# EEZ_DIB_DCP405_r4B2.net
KiCad netlist of a schematic drawn in EAGLE
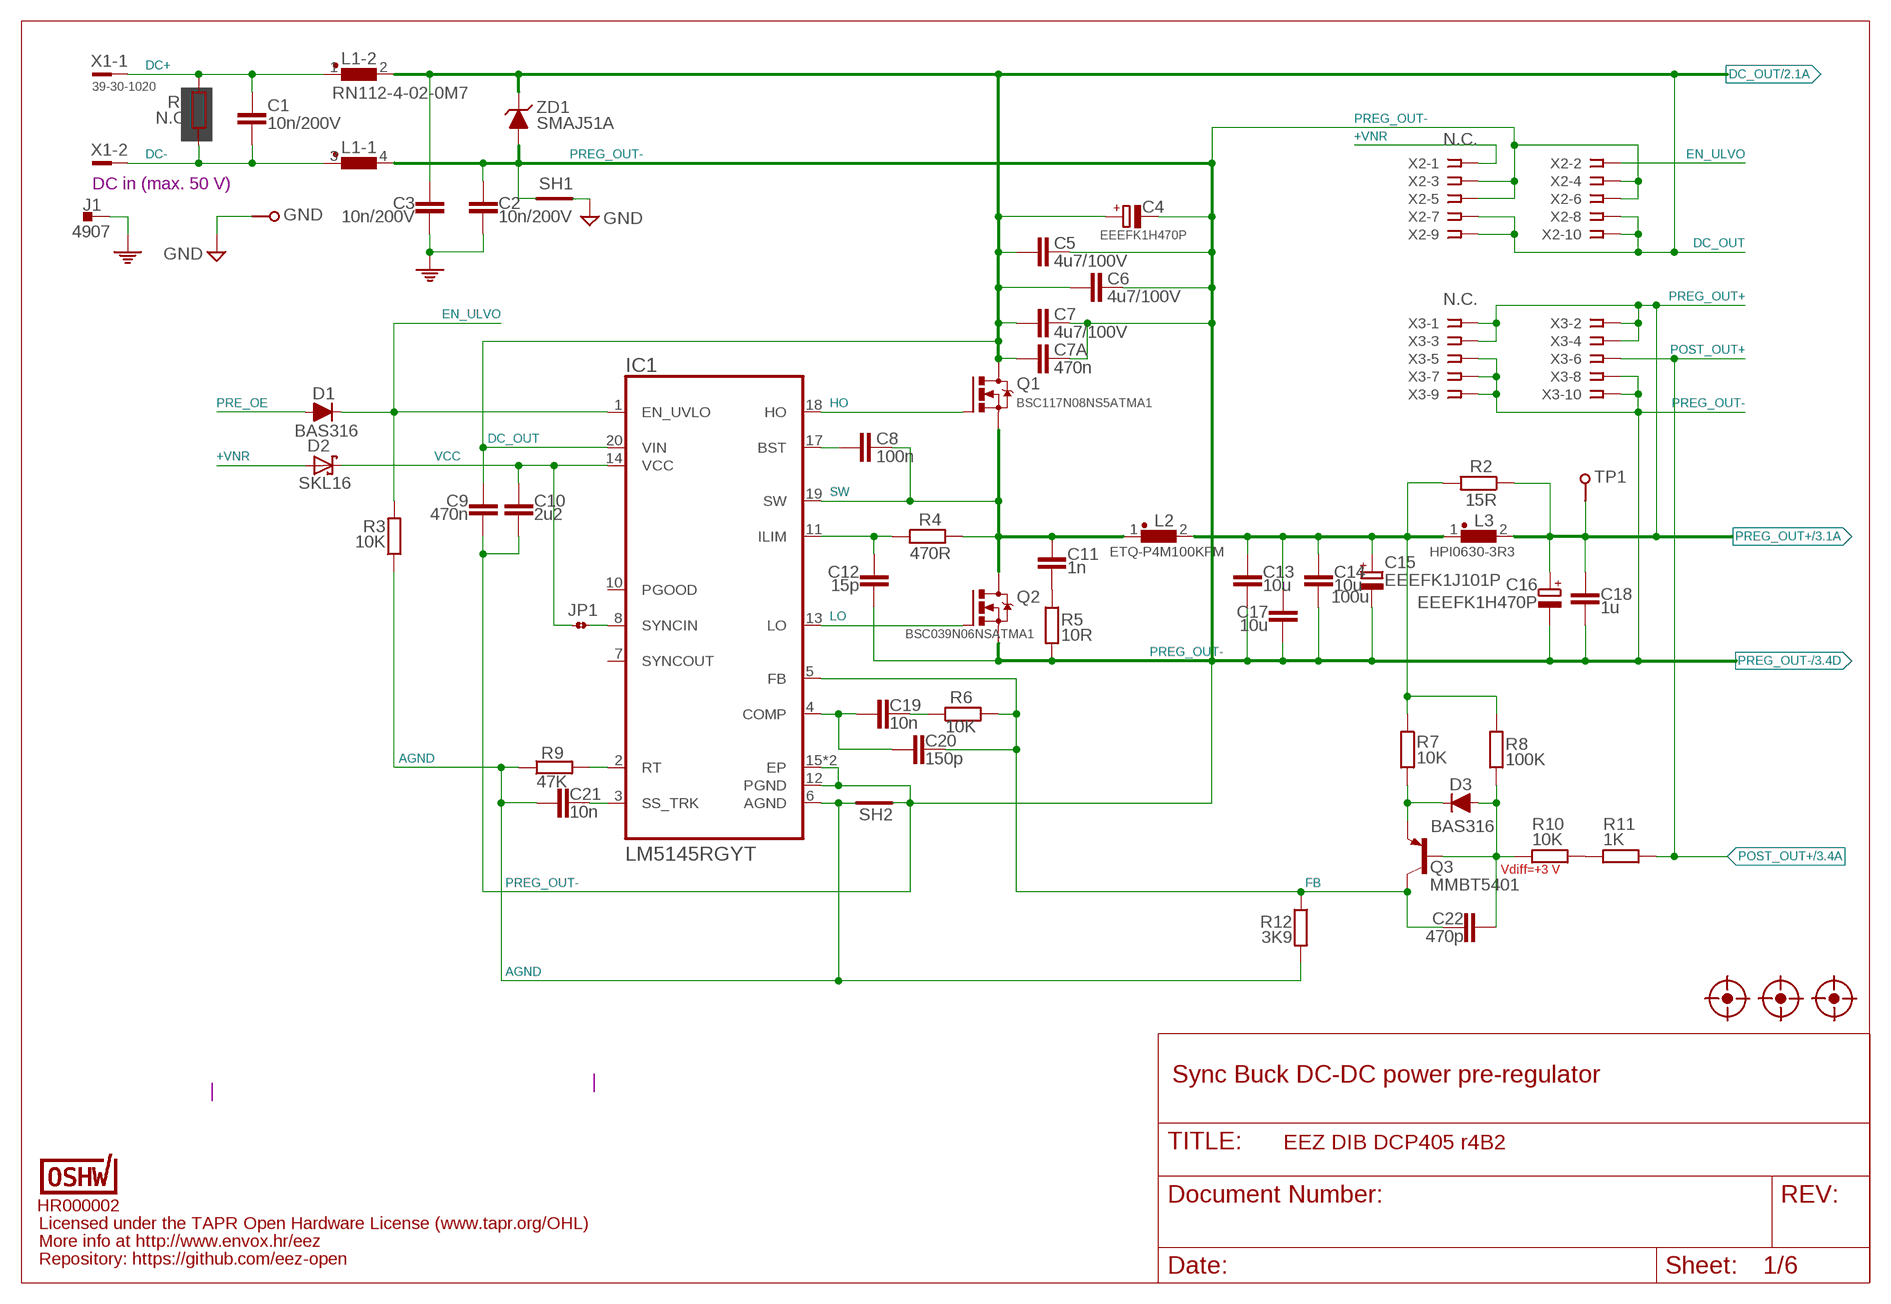
[diagram p0: schematic, sheet 1]
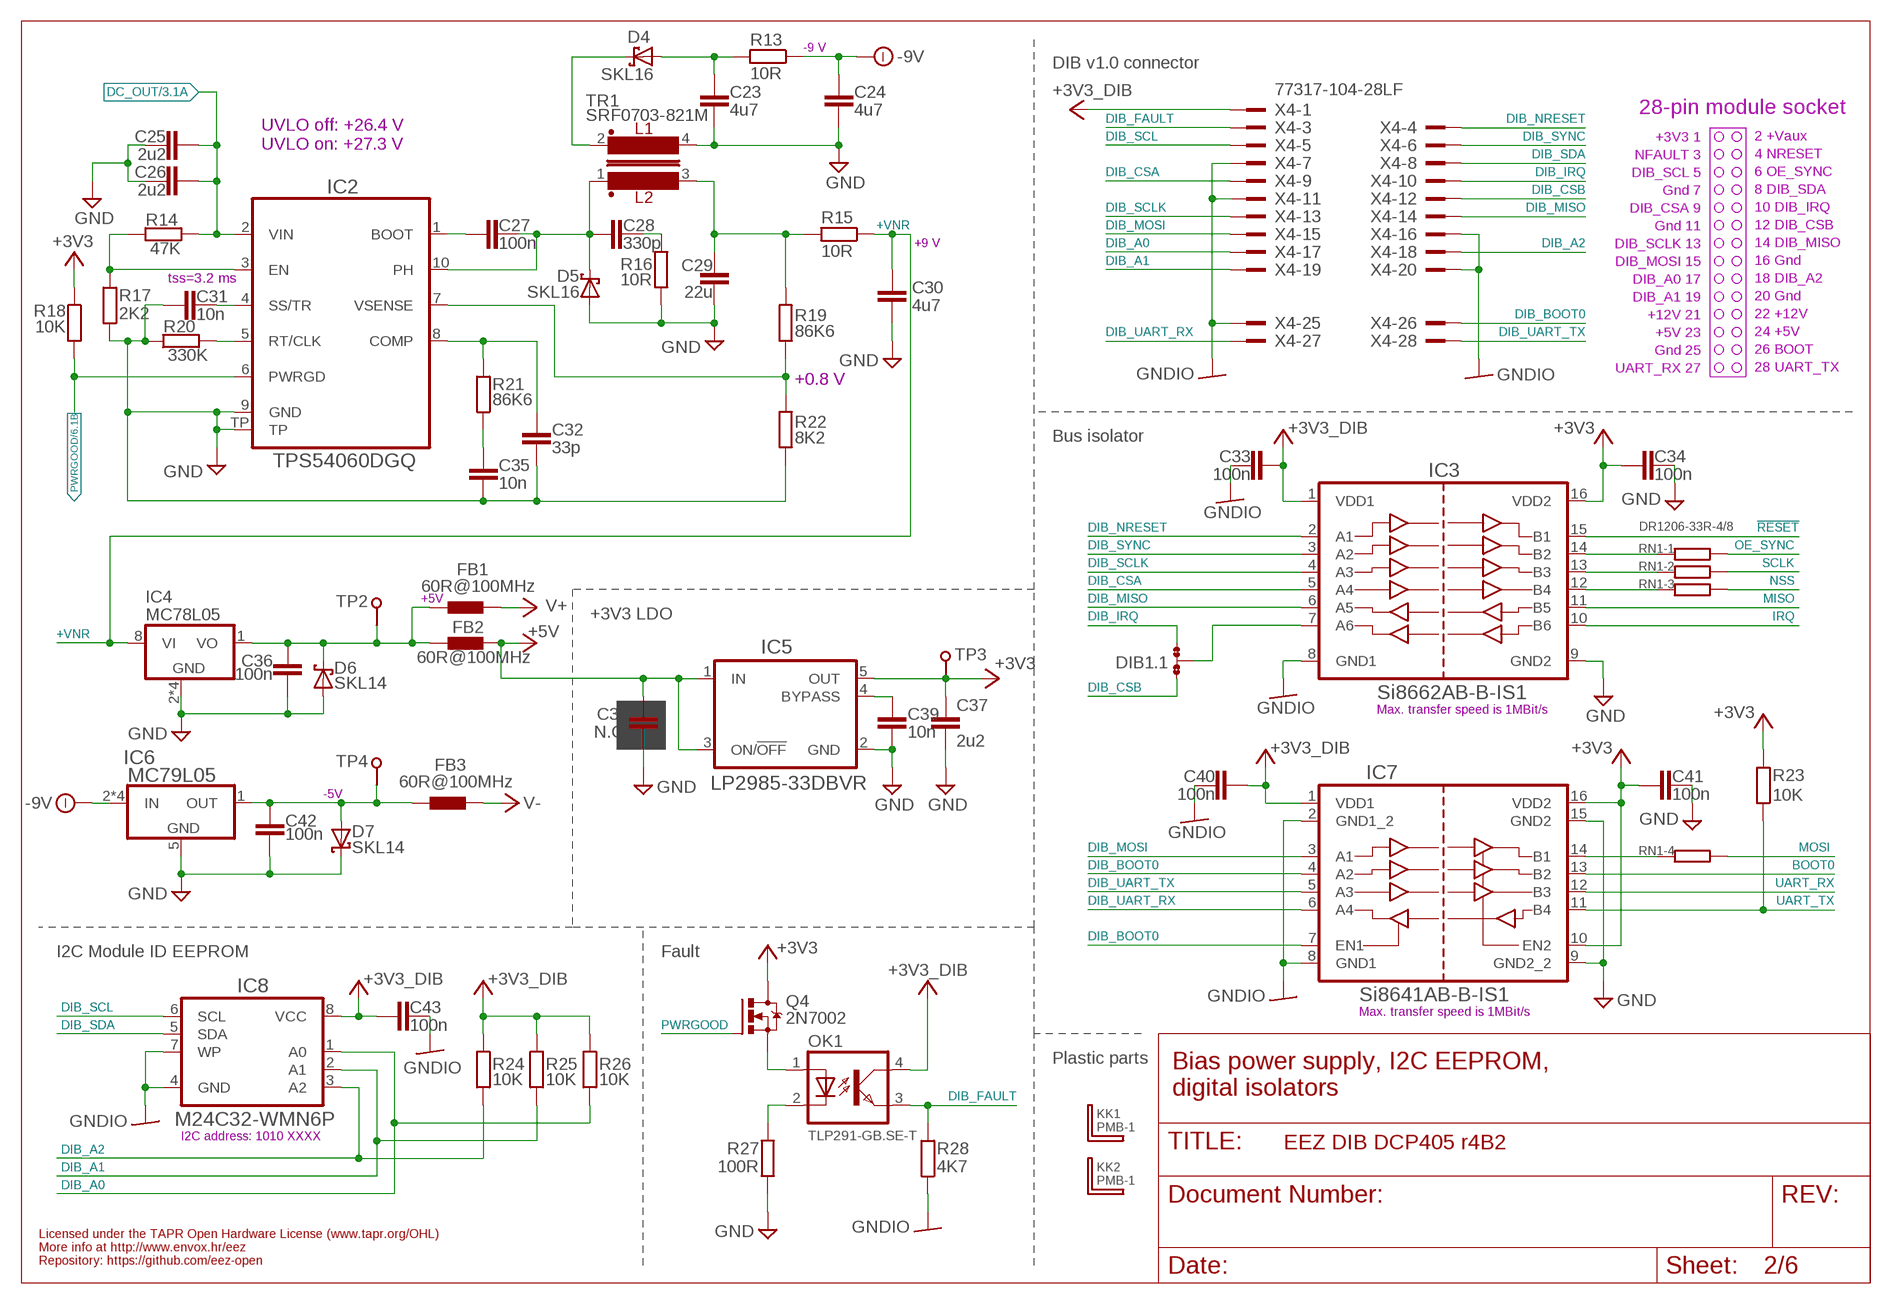
[diagram p1: schematic, sheet 2]
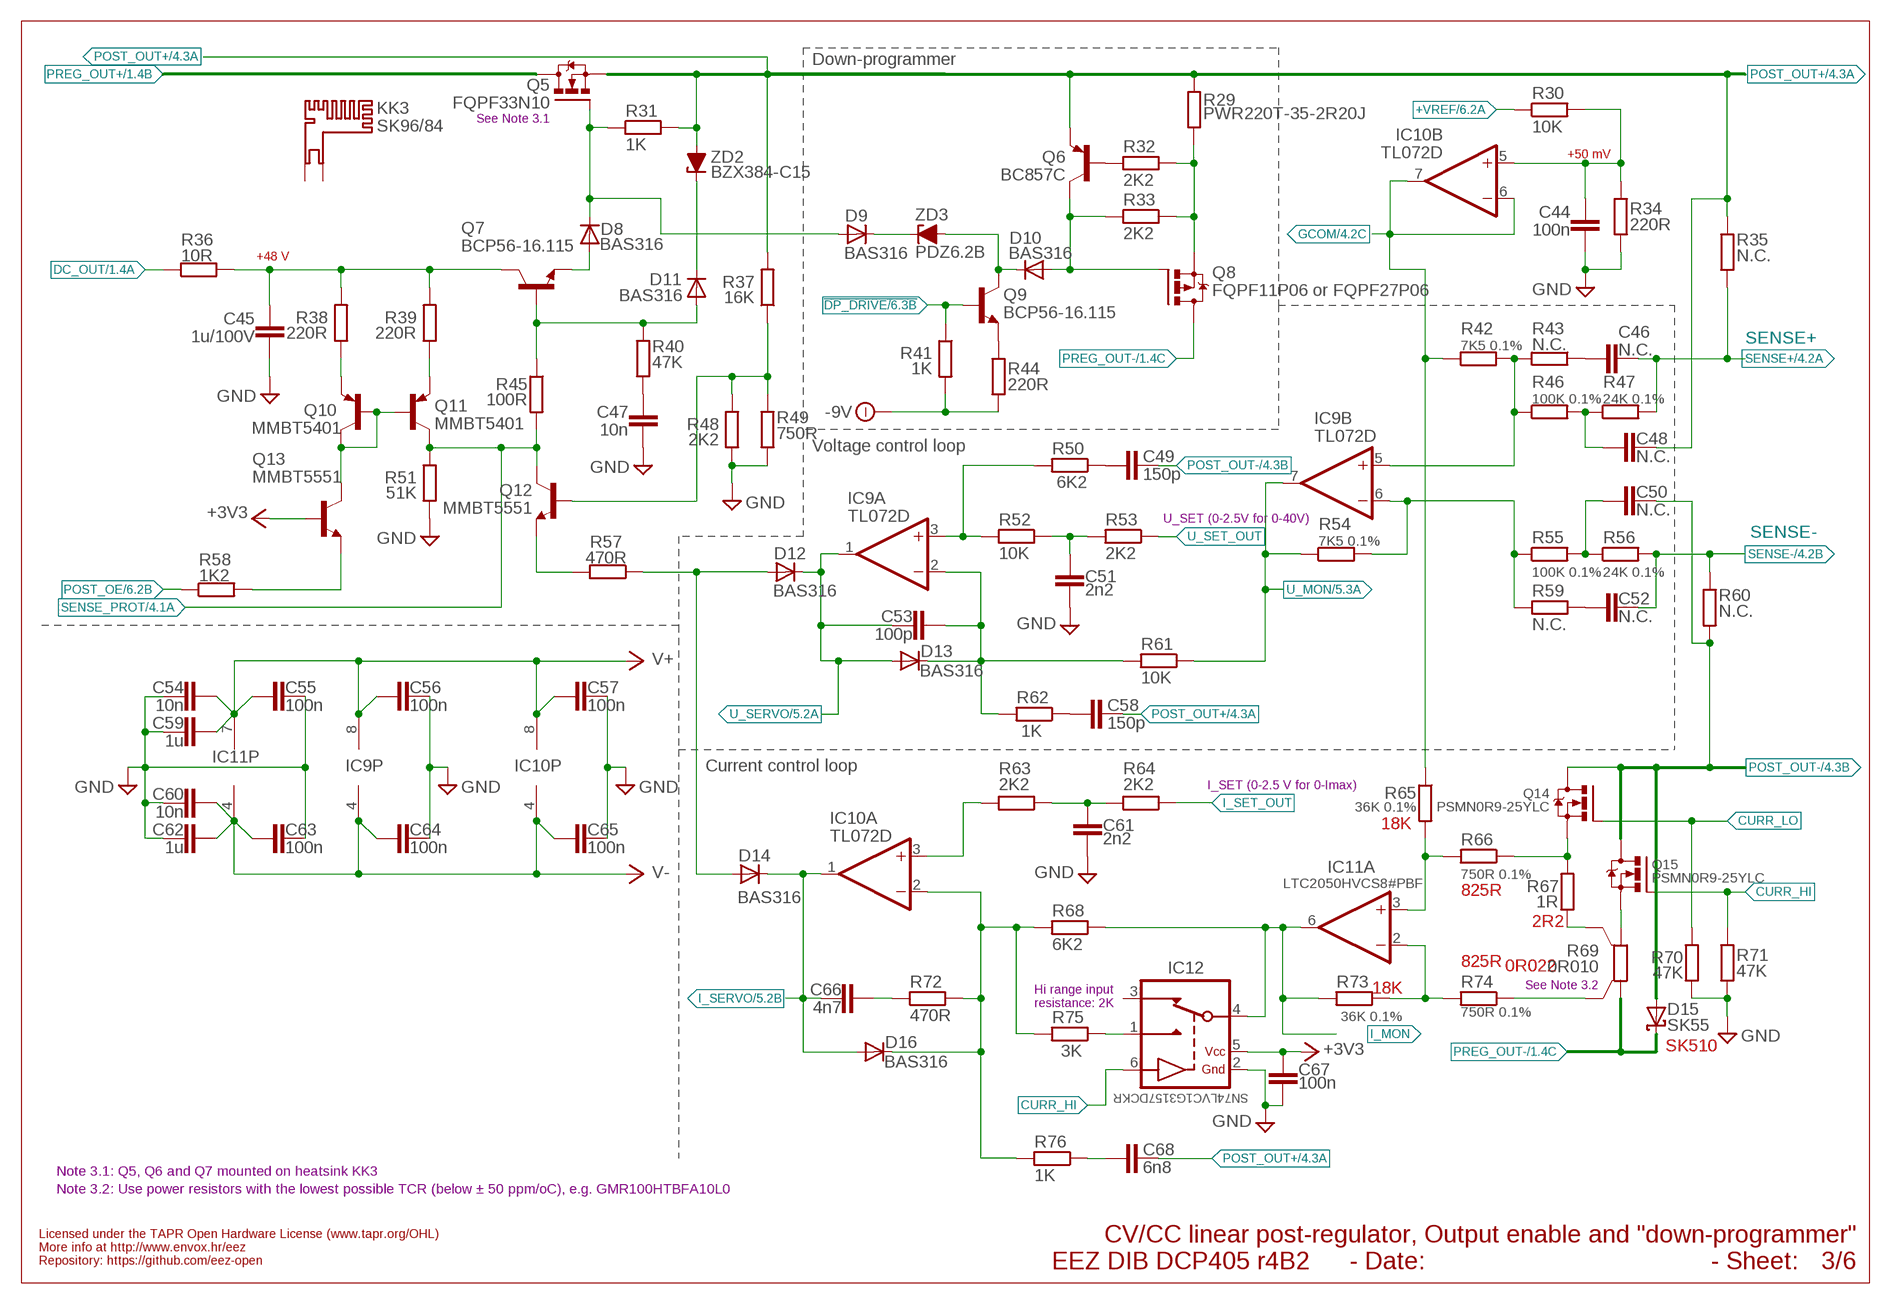
[diagram p2: schematic, sheet 3]
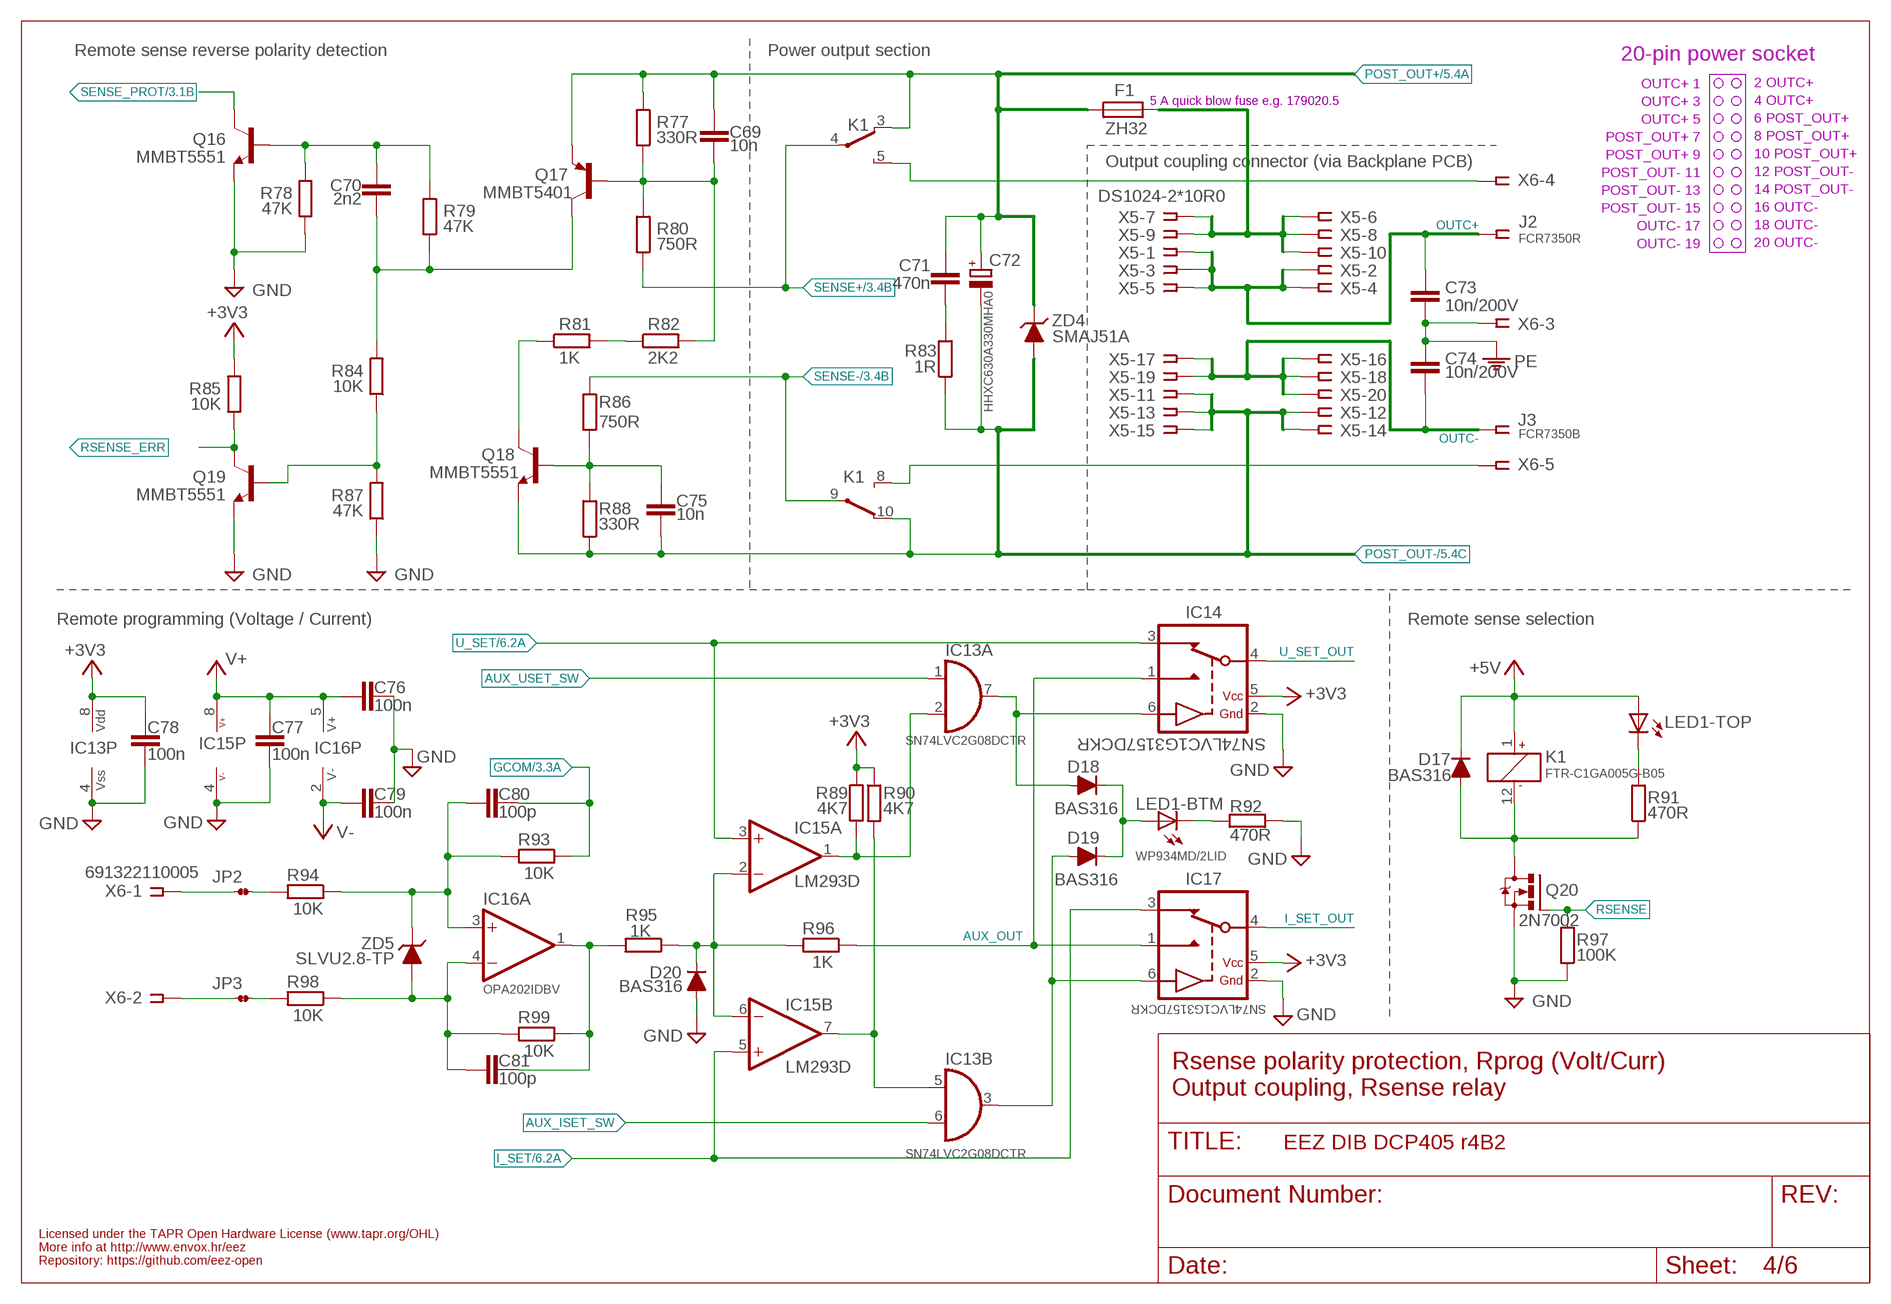
[diagram p3: schematic, sheet 4]
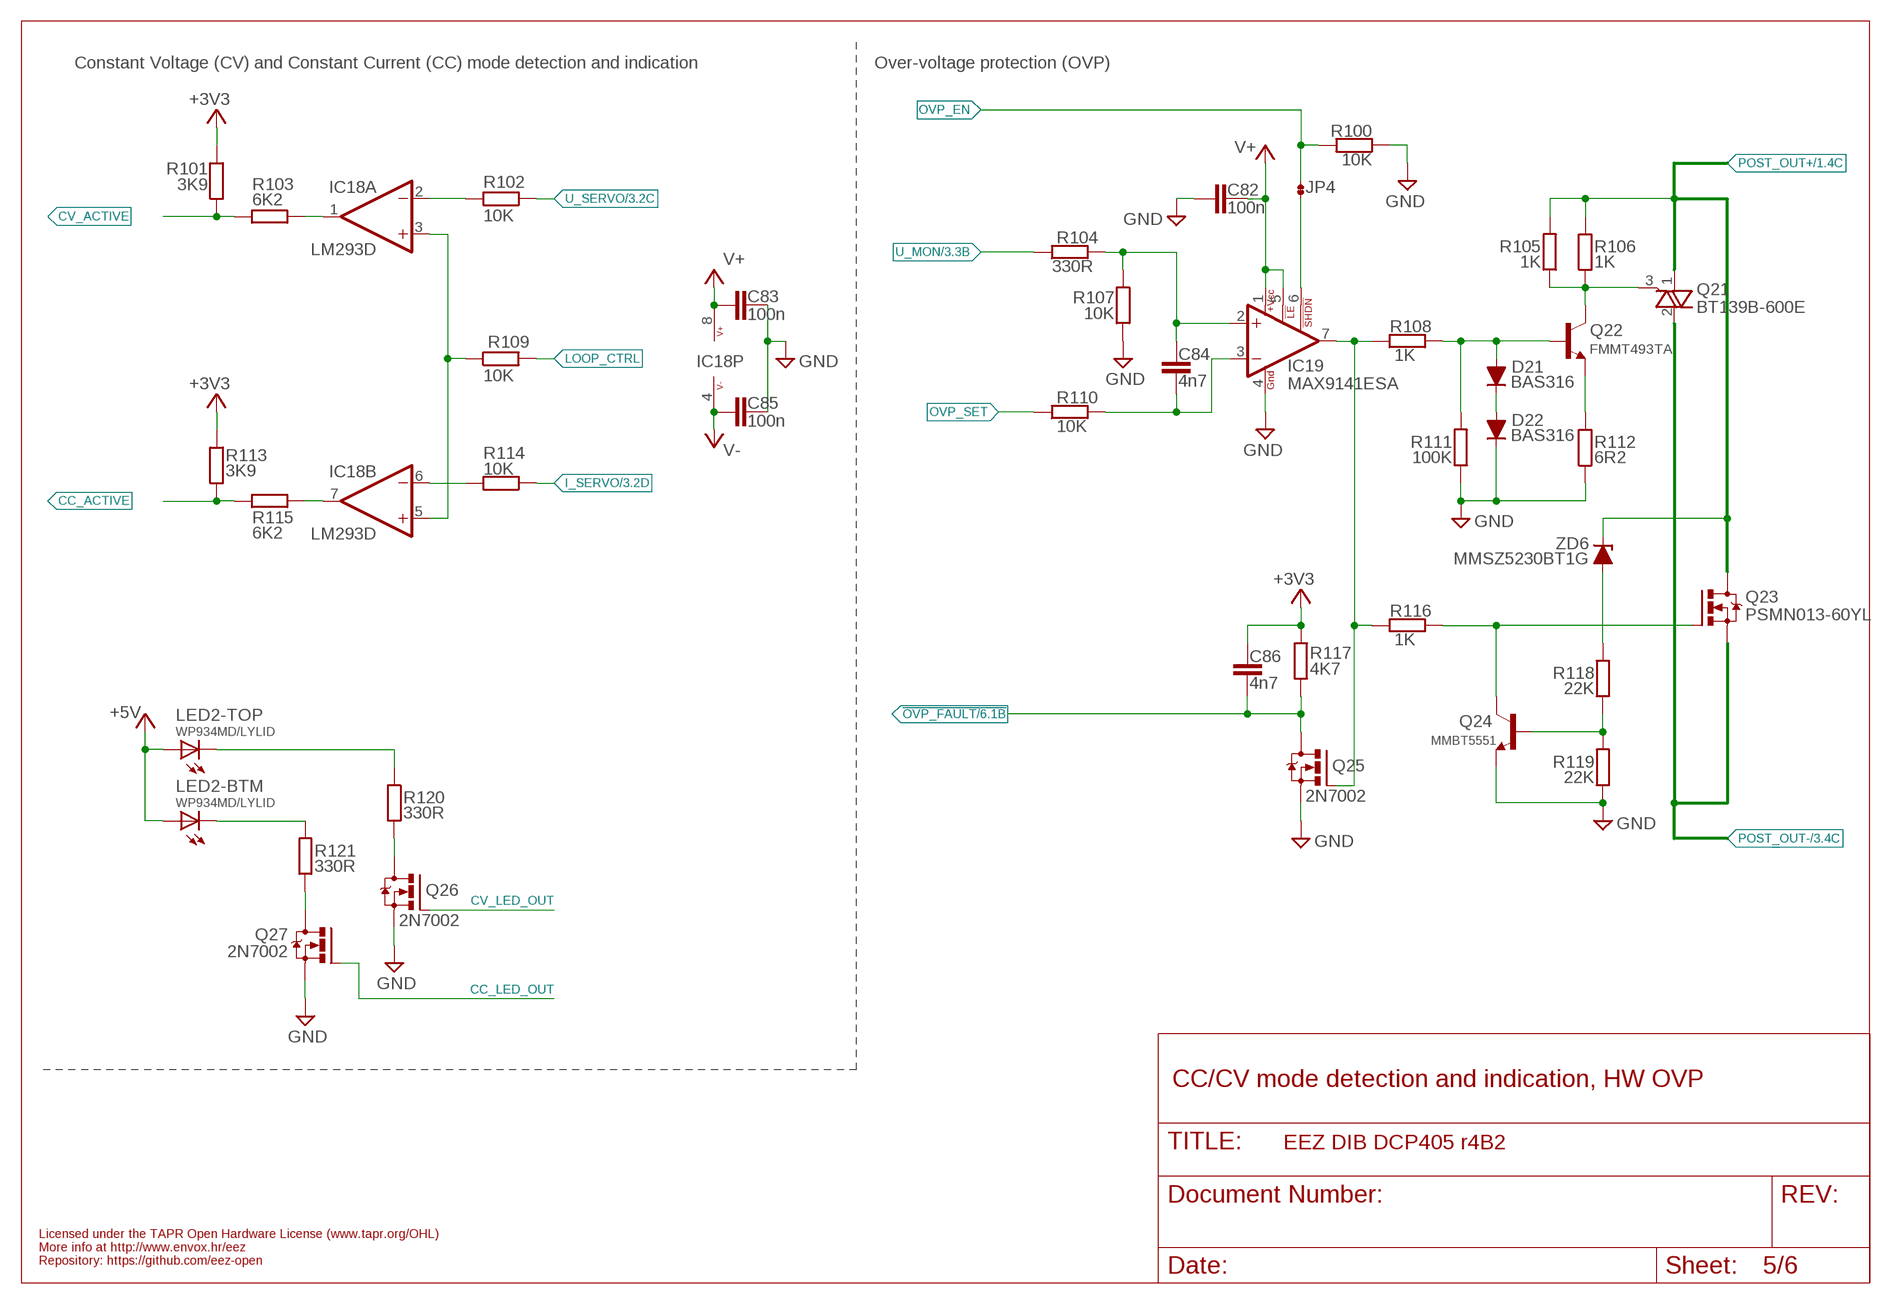
[diagram p4: schematic, sheet 5]
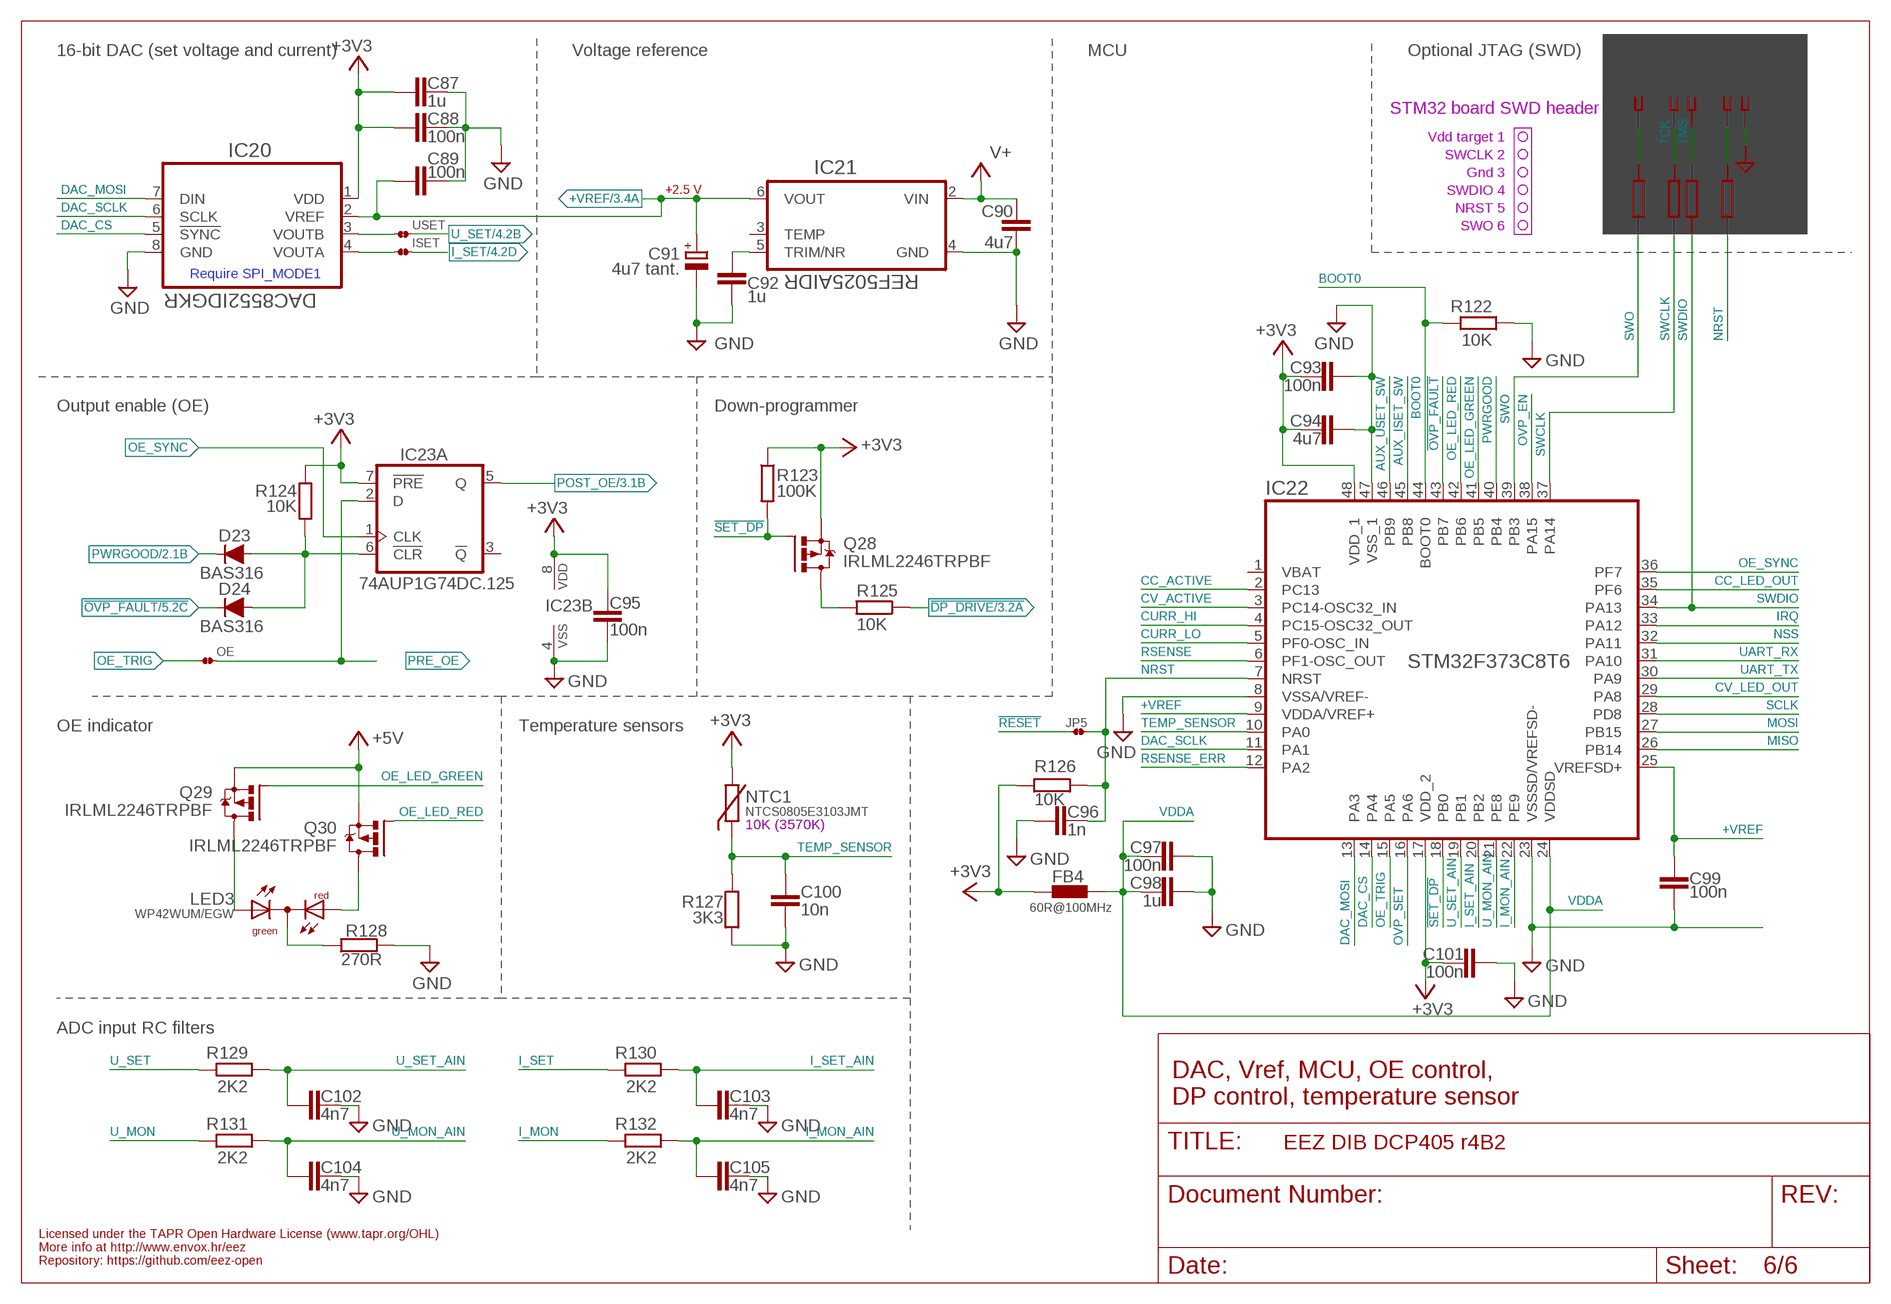
[diagram p5: schematic, sheet 6]

(export (version "E")
  (design (tool "Eeschema 10.0.6"))
  (components
    (comp (ref "C1")
      (value "10n/200V")
      (footprint "eagle-import:C1206")
      (libsource (lib "eagle-import") (part "C-EUC1206"))
    )
    (comp (ref "C2")
      (value "10n/200V")
      (footprint "eagle-import:C1206")
      (libsource (lib "eagle-import") (part "C-EUC1206"))
    )
    (comp (ref "C3")
      (value "10n/200V")
      (footprint "eagle-import:C1206")
      (libsource (lib "eagle-import") (part "C-EUC1206"))
    )
    (comp (ref "C4")
      (value "EEEFK1H470P")
      (footprint "eagle-import:CAPAE830X1050N")
      (libsource (lib "eagle-import") (part "ECAPSMD8.3MM/HA0"))
    )
    (comp (ref "C5")
      (value "4u7/100V")
      (footprint "eagle-import:C1210")
      (libsource (lib "eagle-import") (part "C-EUC1210"))
    )
    (comp (ref "C6")
      (value "4u7/100V")
      (footprint "eagle-import:C1210")
      (libsource (lib "eagle-import") (part "C-EUC1210"))
    )
    (comp (ref "C7")
      (value "4u7/100V")
      (footprint "eagle-import:C1210")
      (libsource (lib "eagle-import") (part "C-EUC1210"))
    )
    (comp (ref "C7A")
      (value "470n")
      (footprint "eagle-import:C0805")
      (libsource (lib "eagle-import") (part "C-EUC0805"))
    )
    (comp (ref "C8")
      (value "100n")
      (footprint "eagle-import:C0603")
      (libsource (lib "eagle-import") (part "C-EUC0603"))
    )
    (comp (ref "C9")
      (value "470n")
      (footprint "eagle-import:C0805")
      (libsource (lib "eagle-import") (part "C-EUC0805"))
    )
    (comp (ref "C10")
      (value "2u2")
      (footprint "eagle-import:C1206")
      (libsource (lib "eagle-import") (part "C-EUC1206"))
    )
    (comp (ref "C11")
      (value "1n")
      (footprint "eagle-import:C0805")
      (libsource (lib "eagle-import") (part "C-EUC0805"))
    )
    (comp (ref "C12")
      (value "15p")
      (footprint "eagle-import:C0805")
      (libsource (lib "eagle-import") (part "C-EUC0805"))
    )
    (comp (ref "C13")
      (value "10u")
      (footprint "eagle-import:C1210")
      (libsource (lib "eagle-import") (part "C-EUC1210"))
    )
    (comp (ref "C14")
      (value "10u")
      (footprint "eagle-import:C1210")
      (libsource (lib "eagle-import") (part "C-EUC1210"))
    )
    (comp (ref "C15")
      (value "EEEFK1J101P")
      (footprint "eagle-import:CAPAE1030X1050N")
      (libsource (lib "eagle-import") (part "ECAP10X10"))
    )
    (comp (ref "C16")
      (value "EEEFK1H470P")
      (footprint "eagle-import:CAPAE830X1050N")
      (libsource (lib "eagle-import") (part "ECAPSMD8.3MM/HA0"))
    )
    (comp (ref "C17")
      (value "10u")
      (footprint "eagle-import:C1210")
      (libsource (lib "eagle-import") (part "C-EUC1210"))
    )
    (comp (ref "C18")
      (value "1u")
      (footprint "eagle-import:C0805")
      (libsource (lib "eagle-import") (part "C-EUC0805"))
    )
    (comp (ref "C19")
      (value "10n")
      (footprint "eagle-import:C0805")
      (libsource (lib "eagle-import") (part "C-EUC0805"))
    )
    (comp (ref "C20")
      (value "150p")
      (footprint "eagle-import:C0805")
      (libsource (lib "eagle-import") (part "C-EUC0805"))
    )
    (comp (ref "C21")
      (value "10n")
      (footprint "eagle-import:C0805")
      (libsource (lib "eagle-import") (part "C-EUC0805"))
    )
    (comp (ref "C22")
      (value "470p")
      (footprint "eagle-import:C0805")
      (libsource (lib "eagle-import") (part "C-EUC0805"))
    )
    (comp (ref "D1")
      (value "BAS316")
      (footprint "eagle-import:SOD323-R")
      (libsource (lib "eagle-import") (part "DIODESOD323R"))
    )
    (comp (ref "D2")
      (value "SKL16")
      (footprint "eagle-import:SOD123")
      (libsource (lib "eagle-import") (part "SCHOTTKYSOD123"))
    )
    (comp (ref "D3")
      (value "BAS316")
      (footprint "eagle-import:SOD323-R")
      (libsource (lib "eagle-import") (part "DIODESOD323R"))
    )
    (comp (ref "FM1")
      (value "FIDUCIAL_2")
      (footprint "eagle-import:FIDUCIAL_DUAL")
      (libsource (lib "eagle-import") (part "FIDUCIAL_2"))
    )
    (comp (ref "FM2")
      (value "FIDUCIAL_2")
      (footprint "eagle-import:FIDUCIAL_DUAL")
      (libsource (lib "eagle-import") (part "FIDUCIAL_2"))
    )
    (comp (ref "FM3")
      (value "FIDUCIAL_2")
      (footprint "eagle-import:FIDUCIAL_DUAL")
      (libsource (lib "eagle-import") (part "FIDUCIAL_2"))
    )
    (comp (ref "GND")
      (value "PCB_TEST_TABSHIELD")
      (footprint "eagle-import:PCB_SHIELD_TAB")
      (libsource (lib "eagle-import") (part "PCB_TEST_TABSHIELD"))
    )
    (comp (ref "IC1")
      (value "LM5145RGYT")
      (footprint "eagle-import:RGY0020B")
      (libsource (lib "eagle-import") (part "LM5145RGYR"))
    )
    (comp (ref "J1")
      (value "4907")
      (footprint "eagle-import:PCB_TAB-4907")
      (libsource (lib "eagle-import") (part "PCB_TAB-4907"))
    )
    (comp (ref "JP1")
      (value "JP2-CUT-0805")
      (footprint "eagle-import:R_0805")
      (libsource (lib "eagle-import") (part "JP2-CUT-0805"))
    )
    (comp (ref "L1")
      (value "RN112-4-02-0M7")
      (footprint "eagle-import:RN112")
      (libsource (lib "eagle-import") (part "RN112"))
    )
    (comp (ref "L2")
      (value "ETQ-P4M100KFM")
      (footprint "eagle-import:PANASONIC_ETQ-P4_KFM")
      (libsource (lib "eagle-import") (part "PANASONIC_ETQ-P4_KFM"))
    )
    (comp (ref "L3")
      (value "HPI0630-3R3")
      (footprint "eagle-import:COILCRAFT_HPI0630")
      (libsource (lib "eagle-import") (part "COILCRAFT_HPI0630"))
    )
    (comp (ref "OSHWA")
      (value "HR000002")
      (footprint "eagle-import:CERT-SMALL-SILK")
      (libsource (lib "eagle-import") (part "OSHWA-CERT-SMALL"))
    )
    (comp (ref "Q1")
      (value "BSC117N08NS5ATMA1")
      (footprint "eagle-import:TDSON-8")
      (libsource (lib "eagle-import") (part "N-MOSFETTDSON-8"))
    )
    (comp (ref "Q2")
      (value "BSC039N06NSATMA1")
      (footprint "eagle-import:TDSON-8")
      (libsource (lib "eagle-import") (part "N-MOSFETTDSON-8"))
    )
    (comp (ref "Q3")
      (value "MMBT5401")
      (footprint "eagle-import:SOT23-BEC")
      (libsource (lib "eagle-import") (part "-PNP-SOT23-BECBC857B"))
    )
    (comp (ref "R1")
      (value "N.C.")
      (footprint "eagle-import:R2512")
      (libsource (lib "eagle-import") (part "R-EU_R2512"))
    )
    (comp (ref "R2")
      (value "15R")
      (footprint "eagle-import:R2010")
      (libsource (lib "eagle-import") (part "R-EU_R2010"))
    )
    (comp (ref "R3")
      (value "10K")
      (footprint "eagle-import:R0805")
      (libsource (lib "eagle-import") (part "R-EU_R0805"))
    )
    (comp (ref "R4")
      (value "470R")
      (footprint "eagle-import:R0805")
      (libsource (lib "eagle-import") (part "R-EU_R0805"))
    )
    (comp (ref "R5")
      (value "10R")
      (footprint "eagle-import:R1206")
      (libsource (lib "eagle-import") (part "R-EU_R1206"))
    )
    (comp (ref "R6")
      (value "10K")
      (footprint "eagle-import:R0805")
      (libsource (lib "eagle-import") (part "R-EU_R0805"))
    )
    (comp (ref "R7")
      (value "10K")
      (footprint "eagle-import:R0805")
      (libsource (lib "eagle-import") (part "R-EU_R0805"))
    )
    (comp (ref "R8")
      (value "100K")
      (footprint "eagle-import:R0805")
      (libsource (lib "eagle-import") (part "R-EU_R0805"))
    )
    (comp (ref "R9")
      (value "47K")
      (footprint "eagle-import:R0805")
      (libsource (lib "eagle-import") (part "R-EU_R0805"))
    )
    (comp (ref "R10")
      (value "10K")
      (footprint "eagle-import:R0805")
      (libsource (lib "eagle-import") (part "R-EU_R0805"))
    )
    (comp (ref "R11")
      (value "1K")
      (footprint "eagle-import:R0805")
      (libsource (lib "eagle-import") (part "R-EU_R0805"))
    )
    (comp (ref "R12")
      (value "3K9")
      (footprint "eagle-import:R0805")
      (libsource (lib "eagle-import") (part "R-EU_R0805"))
    )
    (comp (ref "SH1")
      (value "SHORTNOHOLE")
      (footprint "eagle-import:SHORT_NOHOLE")
      (libsource (lib "eagle-import") (part "SHORTNOHOLE"))
    )
    (comp (ref "SH2")
      (value "SHORTNOHOLE")
      (footprint "eagle-import:SHORT_NOHOLE")
      (libsource (lib "eagle-import") (part "SHORTNOHOLE"))
    )
    (comp (ref "TP1")
      (value "TEST-PIN_0.9MM")
      (footprint "eagle-import:TEST-PIN_0.9MM")
      (libsource (lib "eagle-import") (part "TEST-PIN_0.9MM"))
    )
    (comp (ref "X1")
      (value "39-30-1020")
      (footprint "eagle-import:MINIFIT_39301020")
      (libsource (lib "eagle-import") (part "MINIFIT_39301020"))
    )
    (comp (ref "X2")
      (value "N.C.")
      (footprint "eagle-import:SSW-105-02-S-D")
      (fields (field (name "MPN") "SSW-105-02-S-D"))
      (libsource (lib "eagle-import") (part "SSW-105-02-S-D"))
    )
    (comp (ref "X3")
      (value "N.C.")
      (footprint "eagle-import:SSW-105-02-S-D")
      (fields (field (name "MPN") "SSW-105-02-S-D"))
      (libsource (lib "eagle-import") (part "SSW-105-02-S-D"))
    )
    (comp (ref "ZD1")
      (value "SMAJ51A")
      (footprint "eagle-import:DO214AA")
      (libsource (lib "eagle-import") (part "P6SMB68A"))
    )
    (comp (ref "C82")
      (value "100n")
      (footprint "eagle-import:C0603")
      (libsource (lib "eagle-import") (part "C-EUC0603"))
    )
    (comp (ref "C83")
      (value "100n")
      (footprint "eagle-import:C0603")
      (libsource (lib "eagle-import") (part "C-EUC0603"))
    )
    (comp (ref "C84")
      (value "4n7")
      (footprint "eagle-import:C0805")
      (libsource (lib "eagle-import") (part "C-EUC0805"))
    )
    (comp (ref "C85")
      (value "100n")
      (footprint "eagle-import:C0603")
      (libsource (lib "eagle-import") (part "C-EUC0603"))
    )
    (comp (ref "C86")
      (value "4n7")
      (footprint "eagle-import:C0805")
      (libsource (lib "eagle-import") (part "C-EUC0805"))
    )
    (comp (ref "D21")
      (value "BAS316")
      (footprint "eagle-import:SOD323-R")
      (libsource (lib "eagle-import") (part "DIODESOD323R"))
    )
    (comp (ref "D22")
      (value "BAS316")
      (footprint "eagle-import:SOD323-R")
      (libsource (lib "eagle-import") (part "DIODESOD323R"))
    )
    (comp (ref "IC18")
      (value "LM293D")
      (footprint "eagle-import:SOIC127P600X173-8N")
      (libsource (lib "eagle-import") (part "LM293D"))
    )
    (comp (ref "IC19")
      (value "MAX9141ESA")
      (footprint "eagle-import:SOIC127P600X173-8N")
      (libsource (lib "eagle-import") (part "MAX9141ESA"))
    )
    (comp (ref "JP4")
      (value "JP2-NOCUT-0805")
      (footprint "eagle-import:JP2-0805-NOCUT")
      (libsource (lib "eagle-import") (part "JP2-NOCUT-0805"))
    )
    (comp (ref "LED2")
      (value "WP934MD/LYLID")
      (footprint "eagle-import:WP934MD")
      (libsource (lib "eagle-import") (part "WP934MD/LYLID"))
    )
    (comp (ref "Q21")
      (value "BT139B-600E")
      (footprint "eagle-import:D2PAK")
      (libsource (lib "eagle-import") (part "BT139"))
    )
    (comp (ref "Q22")
      (value "FMMT493TA")
      (footprint "eagle-import:SOT23-BEC")
      (libsource (lib "eagle-import") (part "-NPN-SOT23-BECMMBT5551LT1"))
    )
    (comp (ref "Q23")
      (value "PSMN013-60YL")
      (footprint "eagle-import:SOT669")
      (libsource (lib "eagle-import") (part "N-MOSFETLFPAK"))
    )
    (comp (ref "Q24")
      (value "MMBT5551")
      (footprint "eagle-import:SOT23-BEC")
      (libsource (lib "eagle-import") (part "-NPN-SOT23-BECMMBT5551LT1"))
    )
    (comp (ref "Q25")
      (value "2N7002")
      (footprint "eagle-import:SOT103P240X110-3N")
      (fields (field (name "MPN") "2N7002-7-F"))
      (libsource (lib "eagle-import") (part "2N7002"))
    )
    (comp (ref "Q26")
      (value "2N7002")
      (footprint "eagle-import:SOT103P240X110-3N")
      (fields (field (name "MPN") "2N7002-7-F"))
      (libsource (lib "eagle-import") (part "2N7002"))
    )
    (comp (ref "Q27")
      (value "2N7002")
      (footprint "eagle-import:SOT103P240X110-3N")
      (fields (field (name "MPN") "2N7002-7-F"))
      (libsource (lib "eagle-import") (part "2N7002"))
    )
    (comp (ref "R100")
      (value "10K")
      (footprint "eagle-import:R0805")
      (libsource (lib "eagle-import") (part "R-EU_R0805"))
    )
    (comp (ref "R101")
      (value "3K9")
      (footprint "eagle-import:R0805")
      (libsource (lib "eagle-import") (part "R-EU_R0805"))
    )
    (comp (ref "R102")
      (value "10K")
      (footprint "eagle-import:R0805")
      (libsource (lib "eagle-import") (part "R-EU_R0805"))
    )
    (comp (ref "R103")
      (value "6K2")
      (footprint "eagle-import:R0805")
      (libsource (lib "eagle-import") (part "R-EU_R0805"))
    )
    (comp (ref "R104")
      (value "330R")
      (footprint "eagle-import:R0805")
      (libsource (lib "eagle-import") (part "R-EU_R0805"))
    )
    (comp (ref "R105")
      (value "1K")
      (footprint "eagle-import:R0805")
      (libsource (lib "eagle-import") (part "R-EU_R0805"))
    )
    (comp (ref "R106")
      (value "1K")
      (footprint "eagle-import:R0805")
      (libsource (lib "eagle-import") (part "R-EU_R0805"))
    )
    (comp (ref "R107")
      (value "10K")
      (footprint "eagle-import:R0805")
      (libsource (lib "eagle-import") (part "R-EU_R0805"))
    )
    (comp (ref "R108")
      (value "1K")
      (footprint "eagle-import:R0805")
      (libsource (lib "eagle-import") (part "R-EU_R0805"))
    )
    (comp (ref "R109")
      (value "10K")
      (footprint "eagle-import:R0805")
      (libsource (lib "eagle-import") (part "R-EU_R0805"))
    )
    (comp (ref "R110")
      (value "10K")
      (footprint "eagle-import:R0805")
      (libsource (lib "eagle-import") (part "R-EU_R0805"))
    )
    (comp (ref "R111")
      (value "100K")
      (footprint "eagle-import:R0805")
      (libsource (lib "eagle-import") (part "R-EU_R0805"))
    )
    (comp (ref "R112")
      (value "6R2")
      (footprint "eagle-import:R0805")
      (libsource (lib "eagle-import") (part "R-EU_R0805"))
    )
    (comp (ref "R113")
      (value "3K9")
      (footprint "eagle-import:R0805")
      (libsource (lib "eagle-import") (part "R-EU_R0805"))
    )
    (comp (ref "R114")
      (value "10K")
      (footprint "eagle-import:R0805")
      (libsource (lib "eagle-import") (part "R-EU_R0805"))
    )
    (comp (ref "R115")
      (value "6K2")
      (footprint "eagle-import:R0805")
      (libsource (lib "eagle-import") (part "R-EU_R0805"))
    )
    (comp (ref "R116")
      (value "1K")
      (footprint "eagle-import:R0805")
      (libsource (lib "eagle-import") (part "R-EU_R0805"))
    )
    (comp (ref "R117")
      (value "4K7")
      (footprint "eagle-import:R0805")
      (libsource (lib "eagle-import") (part "R-EU_R0805"))
    )
    (comp (ref "R118")
      (value "22K")
      (footprint "eagle-import:R0805")
      (libsource (lib "eagle-import") (part "R-EU_R0805"))
    )
    (comp (ref "R119")
      (value "22K")
      (footprint "eagle-import:R0805")
      (libsource (lib "eagle-import") (part "R-EU_R0805"))
    )
    (comp (ref "R120")
      (value "330R")
      (footprint "eagle-import:R0805")
      (libsource (lib "eagle-import") (part "R-EU_R0805"))
    )
    (comp (ref "R121")
      (value "330R")
      (footprint "eagle-import:R0805")
      (libsource (lib "eagle-import") (part "R-EU_R0805"))
    )
    (comp (ref "ZD6")
      (value "MMSZ5230BT1G")
      (footprint "eagle-import:SOD123")
      (libsource (lib "eagle-import") (part "ZENER-DIODESOD123"))
    )
    (comp (ref "C44")
      (value "100n")
      (footprint "eagle-import:C0603")
      (libsource (lib "eagle-import") (part "C-EUC0603"))
    )
    (comp (ref "C45")
      (value "1u/100V")
      (footprint "eagle-import:C1206")
      (libsource (lib "eagle-import") (part "C-EUC1206"))
    )
    (comp (ref "C46")
      (value "N.C.")
      (footprint "eagle-import:C0805")
      (libsource (lib "eagle-import") (part "C-EUC0805"))
    )
    (comp (ref "C47")
      (value "10n")
      (footprint "eagle-import:C0805")
      (libsource (lib "eagle-import") (part "C-EUC0805"))
    )
    (comp (ref "C48")
      (value "N.C.")
      (footprint "eagle-import:C0805")
      (libsource (lib "eagle-import") (part "C-EUC0805"))
    )
    (comp (ref "C49")
      (value "150p")
      (footprint "eagle-import:C0805")
      (libsource (lib "eagle-import") (part "C-EUC0805"))
    )
    (comp (ref "C50")
      (value "N.C.")
      (footprint "eagle-import:C0805")
      (libsource (lib "eagle-import") (part "C-EUC0805"))
    )
    (comp (ref "C51")
      (value "2n2")
      (footprint "eagle-import:C0805")
      (libsource (lib "eagle-import") (part "C-EUC0805"))
    )
    (comp (ref "C52")
      (value "N.C.")
      (footprint "eagle-import:C0805")
      (libsource (lib "eagle-import") (part "C-EUC0805"))
    )
    (comp (ref "C53")
      (value "100p")
      (footprint "eagle-import:C0805")
      (libsource (lib "eagle-import") (part "C-EUC0805"))
    )
    (comp (ref "C54")
      (value "10n")
      (footprint "eagle-import:C0805")
      (libsource (lib "eagle-import") (part "C-EUC0805"))
    )
    (comp (ref "C55")
      (value "100n")
      (footprint "eagle-import:C0603")
      (libsource (lib "eagle-import") (part "C-EUC0603"))
    )
    (comp (ref "C56")
      (value "100n")
      (footprint "eagle-import:C0603")
      (libsource (lib "eagle-import") (part "C-EUC0603"))
    )
    (comp (ref "C57")
      (value "100n")
      (footprint "eagle-import:C0603")
      (libsource (lib "eagle-import") (part "C-EUC0603"))
    )
    (comp (ref "C58")
      (value "150p")
      (footprint "eagle-import:C0805")
      (libsource (lib "eagle-import") (part "C-EUC0805"))
    )
    (comp (ref "C59")
      (value "1u")
      (footprint "eagle-import:C0805")
      (libsource (lib "eagle-import") (part "C-EUC0805"))
    )
    (comp (ref "C60")
      (value "10n")
      (footprint "eagle-import:C0805")
      (libsource (lib "eagle-import") (part "C-EUC0805"))
    )
    (comp (ref "C61")
      (value "2n2")
      (footprint "eagle-import:C0805")
      (libsource (lib "eagle-import") (part "C-EUC0805"))
    )
    (comp (ref "C62")
      (value "1u")
      (footprint "eagle-import:C0805")
      (libsource (lib "eagle-import") (part "C-EUC0805"))
    )
    (comp (ref "C63")
      (value "100n")
      (footprint "eagle-import:C0603")
      (libsource (lib "eagle-import") (part "C-EUC0603"))
    )
    (comp (ref "C64")
      (value "100n")
      (footprint "eagle-import:C0603")
      (libsource (lib "eagle-import") (part "C-EUC0603"))
    )
    (comp (ref "C65")
      (value "100n")
      (footprint "eagle-import:C0603")
      (libsource (lib "eagle-import") (part "C-EUC0603"))
    )
    (comp (ref "C66")
      (value "4n7")
      (footprint "eagle-import:C0805")
      (libsource (lib "eagle-import") (part "C-EUC0805"))
    )
    (comp (ref "C67")
      (value "100n")
      (footprint "eagle-import:C0603")
      (libsource (lib "eagle-import") (part "C-EUC0603"))
    )
    (comp (ref "C68")
      (value "6n8")
      (footprint "eagle-import:C0805")
      (libsource (lib "eagle-import") (part "C-EUC0805"))
    )
    (comp (ref "D8")
      (value "BAS316")
      (footprint "eagle-import:SOD323-W")
      (libsource (lib "eagle-import") (part "DIODE-SOD323-W"))
    )
    (comp (ref "D9")
      (value "BAS316")
      (footprint "eagle-import:SOD323-W")
      (libsource (lib "eagle-import") (part "DIODE-SOD323-W"))
    )
    (comp (ref "D10")
      (value "BAS316")
      (footprint "eagle-import:SOD323-W")
      (libsource (lib "eagle-import") (part "DIODE-SOD323-W"))
    )
    (comp (ref "D11")
      (value "BAS316")
      (footprint "eagle-import:SOD323-W")
      (libsource (lib "eagle-import") (part "DIODE-SOD323-W"))
    )
    (comp (ref "D12")
      (value "BAS316")
      (footprint "eagle-import:SOD323-W")
      (libsource (lib "eagle-import") (part "DIODE-SOD323-W"))
    )
    (comp (ref "D13")
      (value "BAS316")
      (footprint "eagle-import:SOD323-W")
      (libsource (lib "eagle-import") (part "DIODE-SOD323-W"))
    )
    (comp (ref "D14")
      (value "BAS316")
      (footprint "eagle-import:SOD323-W")
      (libsource (lib "eagle-import") (part "DIODE-SOD323-W"))
    )
    (comp (ref "D15")
      (value "SK55")
      (footprint "eagle-import:SMB")
      (libsource (lib "eagle-import") (part "SCHOTTKYSMB"))
    )
    (comp (ref "D16")
      (value "BAS316")
      (footprint "eagle-import:SOD323-W")
      (libsource (lib "eagle-import") (part "DIODE-SOD323-W"))
    )
    (comp (ref "IC9")
      (value "TL072D")
      (footprint "eagle-import:SOIC127P600X173-8N")
      (libsource (lib "eagle-import") (part "TL072SOIC8"))
    )
    (comp (ref "IC10")
      (value "TL072D")
      (footprint "eagle-import:SOIC127P600X173-8N")
      (libsource (lib "eagle-import") (part "TL072SOIC8"))
    )
    (comp (ref "IC11")
      (value "LTC2050HVCS8#PBF")
      (footprint "eagle-import:SOIC127P600X173-8N")
      (libsource (lib "eagle-import") (part "OP27GSZSO8"))
    )
    (comp (ref "IC12")
      (value "SN74LVC1G3157DCKR")
      (footprint "eagle-import:SOT65P210X110-6N")
      (libsource (lib "eagle-import") (part "SN74LVC1G3157-DCK"))
    )
    (comp (ref "KK3")
      (value "SK96/84")
      (footprint "eagle-import:SK96_84")
      (libsource (lib "eagle-import") (part "SK96/84"))
    )
    (comp (ref "Q5")
      (value "FQPF33N10")
      (footprint "eagle-import:TO220FP-V")
      (libsource (lib "eagle-import") (part "N-MOSFET-FPV"))
    )
    (comp (ref "Q6")
      (value "BC857C")
      (footprint "eagle-import:SOT23-BEC")
      (libsource (lib "eagle-import") (part "-PNP-SOT23-BECBC857C"))
    )
    (comp (ref "Q7")
      (value "BCP56-16.115")
      (footprint "eagle-import:SOT230P700X180-4N")
      (libsource (lib "eagle-import") (part "BCP56"))
    )
    (comp (ref "Q8")
      (value "FQPF11P06 or FQPF27P06")
      (footprint "eagle-import:TO220FP-V")
      (libsource (lib "eagle-import") (part "P-MOSFET-FPV"))
    )
    (comp (ref "Q9")
      (value "BCP56-16.115")
      (footprint "eagle-import:SOT230P700X180-4N")
      (libsource (lib "eagle-import") (part "BCP56"))
    )
    (comp (ref "Q10")
      (value "MMBT5401")
      (footprint "eagle-import:SOT23-BEC")
      (libsource (lib "eagle-import") (part "-PNP-SOT23-BECBC857B"))
    )
    (comp (ref "Q11")
      (value "MMBT5401")
      (footprint "eagle-import:SOT23-BEC")
      (libsource (lib "eagle-import") (part "-PNP-SOT23-BECBC857B"))
    )
    (comp (ref "Q12")
      (value "MMBT5551")
      (footprint "eagle-import:SOT23-BEC")
      (libsource (lib "eagle-import") (part "-NPN-SOT23-BECMMBT5551LT1"))
    )
    (comp (ref "Q13")
      (value "MMBT5551")
      (footprint "eagle-import:SOT23-BEC")
      (libsource (lib "eagle-import") (part "-NPN-SOT23-BECMMBT5551LT1"))
    )
    (comp (ref "Q14")
      (value "PSMN0R9-25YLC")
      (footprint "eagle-import:SOT669")
      (libsource (lib "eagle-import") (part "N-MOSFETLFPAK"))
    )
    (comp (ref "Q15")
      (value "PSMN0R9-25YLC")
      (footprint "eagle-import:SOT669")
      (libsource (lib "eagle-import") (part "N-MOSFETLFPAK"))
    )
    (comp (ref "R29")
      (value "PWR220T-35-2R20J")
      (footprint "eagle-import:TO220-2R")
      (libsource (lib "eagle-import") (part "R_EU_PWR220T-35"))
    )
    (comp (ref "R30")
      (value "10K")
      (footprint "eagle-import:R0805")
      (libsource (lib "eagle-import") (part "R-EU_R0805"))
    )
    (comp (ref "R31")
      (value "1K")
      (footprint "eagle-import:R0805")
      (libsource (lib "eagle-import") (part "R-EU_R0805"))
    )
    (comp (ref "R32")
      (value "2K2")
      (footprint "eagle-import:R0805")
      (libsource (lib "eagle-import") (part "R-EU_R0805"))
    )
    (comp (ref "R33")
      (value "2K2")
      (footprint "eagle-import:R0805")
      (libsource (lib "eagle-import") (part "R-EU_R0805"))
    )
    (comp (ref "R34")
      (value "220R")
      (footprint "eagle-import:R0805")
      (libsource (lib "eagle-import") (part "R-EU_R0805"))
    )
    (comp (ref "R35")
      (value "N.C.")
      (footprint "eagle-import:R0805")
      (libsource (lib "eagle-import") (part "R-EU_R0805"))
    )
    (comp (ref "R36")
      (value "10R")
      (footprint "eagle-import:R1206")
      (libsource (lib "eagle-import") (part "R-EU_R1206"))
    )
    (comp (ref "R37")
      (value "16K")
      (footprint "eagle-import:R0805")
      (libsource (lib "eagle-import") (part "R-EU_R0805"))
    )
    (comp (ref "R38")
      (value "220R")
      (footprint "eagle-import:R0805")
      (libsource (lib "eagle-import") (part "R-EU_R0805"))
    )
    (comp (ref "R39")
      (value "220R")
      (footprint "eagle-import:R0805")
      (libsource (lib "eagle-import") (part "R-EU_R0805"))
    )
    (comp (ref "R40")
      (value "47K")
      (footprint "eagle-import:R0805")
      (libsource (lib "eagle-import") (part "R-EU_R0805"))
    )
    (comp (ref "R41")
      (value "1K")
      (footprint "eagle-import:R0805")
      (libsource (lib "eagle-import") (part "R-EU_R0805"))
    )
    (comp (ref "R42")
      (value "7K5 0.1%")
      (footprint "eagle-import:R0805")
      (libsource (lib "eagle-import") (part "R-EU_R0805"))
    )
    (comp (ref "R43")
      (value "N.C.")
      (footprint "eagle-import:R0805")
      (libsource (lib "eagle-import") (part "R-EU_R0805"))
    )
    (comp (ref "R44")
      (value "220R")
      (footprint "eagle-import:R0805")
      (libsource (lib "eagle-import") (part "R-EU_R0805"))
    )
    (comp (ref "R45")
      (value "100R")
      (footprint "eagle-import:R0805")
      (libsource (lib "eagle-import") (part "R-EU_R0805"))
    )
    (comp (ref "R46")
      (value "100K 0.1%")
      (footprint "eagle-import:R0805")
      (libsource (lib "eagle-import") (part "R-EU_R0805"))
    )
    (comp (ref "R47")
      (value "24K 0.1%")
      (footprint "eagle-import:R0805")
      (libsource (lib "eagle-import") (part "R-EU_R0805"))
    )
    (comp (ref "R48")
      (value "2K2")
      (footprint "eagle-import:R0805")
      (libsource (lib "eagle-import") (part "R-EU_R0805"))
    )
    (comp (ref "R49")
      (value "750R")
      (footprint "eagle-import:R0805")
      (libsource (lib "eagle-import") (part "R-EU_R0805"))
    )
    (comp (ref "R50")
      (value "6K2")
      (footprint "eagle-import:R0805")
      (libsource (lib "eagle-import") (part "R-EU_R0805"))
    )
    (comp (ref "R51")
      (value "51K")
      (footprint "eagle-import:R0805")
      (libsource (lib "eagle-import") (part "R-EU_R0805"))
    )
    (comp (ref "R52")
      (value "10K")
      (footprint "eagle-import:R0805")
      (libsource (lib "eagle-import") (part "R-EU_R0805"))
    )
    (comp (ref "R53")
      (value "2K2")
      (footprint "eagle-import:R0805")
      (libsource (lib "eagle-import") (part "R-EU_R0805"))
    )
    (comp (ref "R54")
      (value "7K5 0.1%")
      (footprint "eagle-import:R0805")
      (libsource (lib "eagle-import") (part "R-EU_R0805"))
    )
    (comp (ref "R55")
      (value "100K 0.1%")
      (footprint "eagle-import:R0805")
      (libsource (lib "eagle-import") (part "R-EU_R0805"))
    )
    (comp (ref "R56")
      (value "24K 0.1%")
      (footprint "eagle-import:R0805")
      (libsource (lib "eagle-import") (part "R-EU_R0805"))
    )
    (comp (ref "R57")
      (value "470R")
      (footprint "eagle-import:R0805")
      (libsource (lib "eagle-import") (part "R-EU_R0805"))
    )
    (comp (ref "R58")
      (value "1K2")
      (footprint "eagle-import:R0805")
      (libsource (lib "eagle-import") (part "R-EU_R0805"))
    )
    (comp (ref "R59")
      (value "N.C.")
      (footprint "eagle-import:R0805")
      (libsource (lib "eagle-import") (part "R-EU_R0805"))
    )
    (comp (ref "R60")
      (value "N.C.")
      (footprint "eagle-import:R0805")
      (libsource (lib "eagle-import") (part "R-EU_R0805"))
    )
    (comp (ref "R61")
      (value "10K")
      (footprint "eagle-import:R0805")
      (libsource (lib "eagle-import") (part "R-EU_R0805"))
    )
    (comp (ref "R62")
      (value "1K")
      (footprint "eagle-import:R0805")
      (libsource (lib "eagle-import") (part "R-EU_R0805"))
    )
    (comp (ref "R63")
      (value "2K2")
      (footprint "eagle-import:R0805")
      (libsource (lib "eagle-import") (part "R-EU_R0805"))
    )
    (comp (ref "R64")
      (value "2K2")
      (footprint "eagle-import:R0805")
      (libsource (lib "eagle-import") (part "R-EU_R0805"))
    )
    (comp (ref "R65")
      (value "36K 0.1%")
      (footprint "eagle-import:R0805")
      (libsource (lib "eagle-import") (part "R-EU_R0805"))
    )
    (comp (ref "R66")
      (value "750R 0.1%")
      (footprint "eagle-import:R0805")
      (libsource (lib "eagle-import") (part "R-EU_R0805"))
    )
    (comp (ref "R67")
      (value "1R")
      (footprint "eagle-import:R1206")
      (libsource (lib "eagle-import") (part "R-EU_R1206"))
    )
    (comp (ref "R68")
      (value "6K2")
      (footprint "eagle-import:R0805")
      (libsource (lib "eagle-import") (part "R-EU_R0805"))
    )
    (comp (ref "R69")
      (value "0R010")
      (footprint "eagle-import:R_2512-4WIRE")
      (libsource (lib "eagle-import") (part "R-EU_4WIRE2512"))
    )
    (comp (ref "R70")
      (value "47K")
      (footprint "eagle-import:R0805")
      (libsource (lib "eagle-import") (part "R-EU_R0805"))
    )
    (comp (ref "R71")
      (value "47K")
      (footprint "eagle-import:R0805")
      (libsource (lib "eagle-import") (part "R-EU_R0805"))
    )
    (comp (ref "R72")
      (value "470R")
      (footprint "eagle-import:R0805")
      (libsource (lib "eagle-import") (part "R-EU_R0805"))
    )
    (comp (ref "R73")
      (value "36K 0.1%")
      (footprint "eagle-import:R0805")
      (libsource (lib "eagle-import") (part "R-EU_R0805"))
    )
    (comp (ref "R74")
      (value "750R 0.1%")
      (footprint "eagle-import:R0805")
      (libsource (lib "eagle-import") (part "R-EU_R0805"))
    )
    (comp (ref "R75")
      (value "3K")
      (footprint "eagle-import:R0805")
      (libsource (lib "eagle-import") (part "R-EU_R0805"))
    )
    (comp (ref "R76")
      (value "1K")
      (footprint "eagle-import:R0805")
      (libsource (lib "eagle-import") (part "R-EU_R0805"))
    )
    (comp (ref "ZD2")
      (value "BZX384-C15")
      (footprint "eagle-import:SOD323-W")
      (libsource (lib "eagle-import") (part "ZENER-DIODESOD323"))
    )
    (comp (ref "ZD3")
      (value "PDZ6.2B")
      (footprint "eagle-import:SOD323-W")
      (libsource (lib "eagle-import") (part "ZENER-DIODESOD323"))
    )
    (comp (ref "C87")
      (value "1u")
      (footprint "eagle-import:C0805")
      (libsource (lib "eagle-import") (part "C-EUC0805"))
    )
    (comp (ref "C88")
      (value "100n")
      (footprint "eagle-import:C0603")
      (libsource (lib "eagle-import") (part "C-EUC0603"))
    )
    (comp (ref "C89")
      (value "100n")
      (footprint "eagle-import:C0603")
      (libsource (lib "eagle-import") (part "C-EUC0603"))
    )
    (comp (ref "C90")
      (value "4u7")
      (footprint "eagle-import:C1206")
      (libsource (lib "eagle-import") (part "C-EUC1206"))
    )
    (comp (ref "C91")
      (value "4u7 tant.")
      (footprint "eagle-import:EC1206")
      (libsource (lib "eagle-import") (part "ECAP1206"))
    )
    (comp (ref "C92")
      (value "1u")
      (footprint "eagle-import:C0805")
      (libsource (lib "eagle-import") (part "C-EUC0805"))
    )
    (comp (ref "C93")
      (value "100n")
      (footprint "eagle-import:C0603")
      (libsource (lib "eagle-import") (part "C-EUC0603"))
    )
    (comp (ref "C94")
      (value "4u7")
      (footprint "eagle-import:C1206")
      (libsource (lib "eagle-import") (part "C-EUC1206"))
    )
    (comp (ref "C95")
      (value "100n")
      (footprint "eagle-import:C0603")
      (libsource (lib "eagle-import") (part "C-EUC0603"))
    )
    (comp (ref "C96")
      (value "1n")
      (footprint "eagle-import:C0805")
      (libsource (lib "eagle-import") (part "C-EUC0805"))
    )
    (comp (ref "C97")
      (value "100n")
      (footprint "eagle-import:C0603")
      (libsource (lib "eagle-import") (part "C-EUC0603"))
    )
    (comp (ref "C98")
      (value "1u")
      (footprint "eagle-import:C0805")
      (libsource (lib "eagle-import") (part "C-EUC0805"))
    )
    (comp (ref "C99")
      (value "100n")
      (footprint "eagle-import:C0603")
      (libsource (lib "eagle-import") (part "C-EUC0603"))
    )
    (comp (ref "C100")
      (value "10n")
      (footprint "eagle-import:C0805")
      (libsource (lib "eagle-import") (part "C-EUC0805"))
    )
    (comp (ref "C101")
      (value "100n")
      (footprint "eagle-import:C0603")
      (libsource (lib "eagle-import") (part "C-EUC0603"))
    )
    (comp (ref "C102")
      (value "4n7")
      (footprint "eagle-import:C0805")
      (libsource (lib "eagle-import") (part "C-EUC0805"))
    )
    (comp (ref "C103")
      (value "4n7")
      (footprint "eagle-import:C0805")
      (libsource (lib "eagle-import") (part "C-EUC0805"))
    )
    (comp (ref "C104")
      (value "4n7")
      (footprint "eagle-import:C0805")
      (libsource (lib "eagle-import") (part "C-EUC0805"))
    )
    (comp (ref "C105")
      (value "4n7")
      (footprint "eagle-import:C0805")
      (libsource (lib "eagle-import") (part "C-EUC0805"))
    )
    (comp (ref "D23")
      (value "BAS316")
      (footprint "eagle-import:SOD323-R")
      (libsource (lib "eagle-import") (part "DIODESOD323R"))
    )
    (comp (ref "D24")
      (value "BAS316")
      (footprint "eagle-import:SOD323-R")
      (libsource (lib "eagle-import") (part "DIODESOD323R"))
    )
    (comp (ref "FB4")
      (value "60R@100MHz")
      (footprint "eagle-import:BEAD0603")
      (libsource (lib "eagle-import") (part "FERRITE_BEAD0603"))
    )
    (comp (ref "IC20")
      (value "DAC8552IDGKR")
      (footprint "eagle-import:DGK8-M")
      (libsource (lib "eagle-import") (part "DAC8552_DGK_8M"))
    )
    (comp (ref "IC21")
      (value "REF5025AIDR")
      (footprint "eagle-import:SOIC127P600X175-8N")
      (libsource (lib "eagle-import") (part "REF50XX"))
    )
    (comp (ref "IC22")
      (value "STM32F373C8T6")
      (footprint "eagle-import:LQFP-48")
      (libsource (lib "eagle-import") (part "STM32F373C8T6"))
    )
    (comp (ref "IC23")
      (value "74AUP1G74DC.125")
      (footprint "eagle-import:DCU8")
      (libsource (lib "eagle-import") (part "SN74LVC1G74DCTR-VSSOP"))
    )
    (comp (ref "ISET")
      (value "JP2-NOCUT-0805")
      (footprint "eagle-import:JP2-0805-NOCUT")
      (libsource (lib "eagle-import") (part "JP2-NOCUT-0805"))
    )
    (comp (ref "JP5")
      (value "JP2-NOCUT-0805")
      (footprint "eagle-import:JP2-0805-NOCUT")
      (libsource (lib "eagle-import") (part "JP2-NOCUT-0805"))
    )
    (comp (ref "LED3")
      (value "WP42WUM/EGW")
      (footprint "eagle-import:L-42WUM-1EGWT")
      (libsource (lib "eagle-import") (part "LED_L-42WUM/1EGWT"))
    )
    (comp (ref "NTC1")
      (value "NTCS0805E3103JMT")
      (footprint "eagle-import:R_0805")
      (libsource (lib "eagle-import") (part "NTCR_0805"))
    )
    (comp (ref "OE")
      (value "JP2-NOCUT-0805")
      (footprint "eagle-import:JP2-0805-NOCUT")
      (libsource (lib "eagle-import") (part "JP2-NOCUT-0805"))
    )
    (comp (ref "Q28")
      (value "IRLML2246TRPBF")
      (footprint "eagle-import:SOT95P237X112-3N")
      (libsource (lib "eagle-import") (part "IRLML2246TRPBF"))
    )
    (comp (ref "Q29")
      (value "IRLML2246TRPBF")
      (footprint "eagle-import:SOT95P237X112-3N")
      (libsource (lib "eagle-import") (part "IRLML2246TRPBF"))
    )
    (comp (ref "Q30")
      (value "IRLML2246TRPBF")
      (footprint "eagle-import:SOT95P237X112-3N")
      (libsource (lib "eagle-import") (part "IRLML2246TRPBF"))
    )
    (comp (ref "R122")
      (value "10K")
      (footprint "eagle-import:R0805")
      (libsource (lib "eagle-import") (part "R-EU_R0805"))
    )
    (comp (ref "R123")
      (value "100K")
      (footprint "eagle-import:R0805")
      (libsource (lib "eagle-import") (part "R-EU_R0805"))
    )
    (comp (ref "R124")
      (value "10K")
      (footprint "eagle-import:R0805")
      (libsource (lib "eagle-import") (part "R-EU_R0805"))
    )
    (comp (ref "R125")
      (value "10K")
      (footprint "eagle-import:R0805")
      (libsource (lib "eagle-import") (part "R-EU_R0805"))
    )
    (comp (ref "R126")
      (value "10K")
      (footprint "eagle-import:R0805")
      (libsource (lib "eagle-import") (part "R-EU_R0805"))
    )
    (comp (ref "R127")
      (value "3K3")
      (footprint "eagle-import:R0805")
      (libsource (lib "eagle-import") (part "R-EU_R0805"))
    )
    (comp (ref "R128")
      (value "270R")
      (footprint "eagle-import:R0805")
      (libsource (lib "eagle-import") (part "R-EU_R0805"))
    )
    (comp (ref "R129")
      (value "2K2")
      (footprint "eagle-import:R0805")
      (libsource (lib "eagle-import") (part "R-EU_R0805"))
    )
    (comp (ref "R130")
      (value "2K2")
      (footprint "eagle-import:R0805")
      (libsource (lib "eagle-import") (part "R-EU_R0805"))
    )
    (comp (ref "R131")
      (value "2K2")
      (footprint "eagle-import:R0805")
      (libsource (lib "eagle-import") (part "R-EU_R0805"))
    )
    (comp (ref "R132")
      (value "2K2")
      (footprint "eagle-import:R0805")
      (libsource (lib "eagle-import") (part "R-EU_R0805"))
    )
    (comp (ref "RN2")
      (value "N.C.")
      (footprint "eagle-import:CAY16")
      (libsource (lib "eagle-import") (part "R_ARRAY4"))
    )
    (comp (ref "USET")
      (value "JP2-NOCUT-0805")
      (footprint "eagle-import:JP2-0805-NOCUT")
      (libsource (lib "eagle-import") (part "JP2-NOCUT-0805"))
    )
    (comp (ref "X7")
      (value "N.C.")
      (footprint "eagle-import:SSW-106-02-S-S")
      (fields (field (name "MPN") "SSW-106-02-S-S"))
      (libsource (lib "eagle-import") (part "SSW-106-02-S-S"))
    )
    (comp (ref "C23")
      (value "4u7")
      (footprint "eagle-import:C1206")
      (libsource (lib "eagle-import") (part "C-EUC1206"))
    )
    (comp (ref "C24")
      (value "4u7")
      (footprint "eagle-import:C1206")
      (libsource (lib "eagle-import") (part "C-EUC1206"))
    )
    (comp (ref "C25")
      (value "2u2")
      (footprint "eagle-import:C1206")
      (libsource (lib "eagle-import") (part "C-EUC1206"))
    )
    (comp (ref "C26")
      (value "2u2")
      (footprint "eagle-import:C1206")
      (libsource (lib "eagle-import") (part "C-EUC1206"))
    )
    (comp (ref "C27")
      (value "100n")
      (footprint "eagle-import:C0603")
      (libsource (lib "eagle-import") (part "C-EUC0603"))
    )
    (comp (ref "C28")
      (value "330p")
      (footprint "eagle-import:C0805")
      (libsource (lib "eagle-import") (part "C-EUC0805"))
    )
    (comp (ref "C29")
      (value "22u")
      (footprint "eagle-import:C1210")
      (libsource (lib "eagle-import") (part "C-EUC1210"))
    )
    (comp (ref "C30")
      (value "4u7")
      (footprint "eagle-import:C1206")
      (libsource (lib "eagle-import") (part "C-EUC1206"))
    )
    (comp (ref "C31")
      (value "10n")
      (footprint "eagle-import:C0805")
      (libsource (lib "eagle-import") (part "C-EUC0805"))
    )
    (comp (ref "C32")
      (value "33p")
      (footprint "eagle-import:C0805")
      (libsource (lib "eagle-import") (part "C-EUC0805"))
    )
    (comp (ref "C33")
      (value "100n")
      (footprint "eagle-import:C0603")
      (libsource (lib "eagle-import") (part "C-EUC0603"))
    )
    (comp (ref "C34")
      (value "100n")
      (footprint "eagle-import:C0603")
      (libsource (lib "eagle-import") (part "C-EUC0603"))
    )
    (comp (ref "C35")
      (value "10n")
      (footprint "eagle-import:C0805")
      (libsource (lib "eagle-import") (part "C-EUC0805"))
    )
    (comp (ref "C36")
      (value "100n")
      (footprint "eagle-import:C0603")
      (libsource (lib "eagle-import") (part "C-EUC0603"))
    )
    (comp (ref "C37")
      (value "2u2")
      (footprint "eagle-import:C1206")
      (libsource (lib "eagle-import") (part "C-EUC1206"))
    )
    (comp (ref "C38")
      (value "N.C.")
      (footprint "eagle-import:C0805")
      (libsource (lib "eagle-import") (part "C-EUC0805"))
    )
    (comp (ref "C39")
      (value "10n")
      (footprint "eagle-import:C0805")
      (libsource (lib "eagle-import") (part "C-EUC0805"))
    )
    (comp (ref "C40")
      (value "100n")
      (footprint "eagle-import:C0603")
      (libsource (lib "eagle-import") (part "C-EUC0603"))
    )
    (comp (ref "C41")
      (value "100n")
      (footprint "eagle-import:C0603")
      (libsource (lib "eagle-import") (part "C-EUC0603"))
    )
    (comp (ref "C42")
      (value "100n")
      (footprint "eagle-import:C0603")
      (libsource (lib "eagle-import") (part "C-EUC0603"))
    )
    (comp (ref "C43")
      (value "100n")
      (footprint "eagle-import:C0603")
      (libsource (lib "eagle-import") (part "C-EUC0603"))
    )
    (comp (ref "D4")
      (value "SKL16")
      (footprint "eagle-import:SOD123")
      (libsource (lib "eagle-import") (part "SCHOTTKYSOD123"))
    )
    (comp (ref "D5")
      (value "SKL16")
      (footprint "eagle-import:SOD123")
      (libsource (lib "eagle-import") (part "SCHOTTKYSOD123"))
    )
    (comp (ref "D6")
      (value "SKL14")
      (footprint "eagle-import:SOD123")
      (libsource (lib "eagle-import") (part "SCHOTTKYSOD123"))
    )
    (comp (ref "D7")
      (value "SKL14")
      (footprint "eagle-import:SOD123")
      (libsource (lib "eagle-import") (part "SCHOTTKYSOD123"))
    )
    (comp (ref "DIB1.1")
      (value "JP3-CUT-0805-ROTATED")
      (footprint "eagle-import:JP3-0805-CUT2")
      (libsource (lib "eagle-import") (part "JP3-CUT-0805-ROTATED"))
    )
    (comp (ref "FB1")
      (value "60R@100MHz")
      (footprint "eagle-import:BEAD0603")
      (libsource (lib "eagle-import") (part "FERRITE_BEAD0603"))
    )
    (comp (ref "FB2")
      (value "60R@100MHz")
      (footprint "eagle-import:BEAD0603")
      (libsource (lib "eagle-import") (part "FERRITE_BEAD0603"))
    )
    (comp (ref "FB3")
      (value "60R@100MHz")
      (footprint "eagle-import:BEAD0603")
      (libsource (lib "eagle-import") (part "FERRITE_BEAD0603"))
    )
    (comp (ref "IC2")
      (value "TPS54060DGQ")
      (footprint "eagle-import:SOP50P490X110-11N")
      (fields (field (name "MPN") "TPS54060ADGQ"))
      (libsource (lib "eagle-import") (part "TPS54060DGQ"))
    )
    (comp (ref "IC3")
      (value "Si8662AB-B-IS1")
      (footprint "eagle-import:SOIC-16")
      (libsource (lib "eagle-import") (part "SI8662NSOIC-16"))
    )
    (comp (ref "IC4")
      (value "MC78L05")
      (footprint "eagle-import:SOIC127P600X173-8N")
      (libsource (lib "eagle-import") (part "MC78LXXSOIC8"))
    )
    (comp (ref "IC5")
      (value "LP2985-33DBVR")
      (footprint "eagle-import:SOT95P270X145-5N")
      (libsource (lib "eagle-import") (part "LP2985"))
    )
    (comp (ref "IC6")
      (value "MC79L05")
      (footprint "eagle-import:SOIC127P600X173-8N")
      (libsource (lib "eagle-import") (part "MC79LXXSOIC"))
    )
    (comp (ref "IC7")
      (value "Si8641AB-B-IS1")
      (footprint "eagle-import:SOIC-16")
      (libsource (lib "eagle-import") (part "SI8641NSOIC-16"))
    )
    (comp (ref "IC8")
      (value "M24C32-WMN6P")
      (footprint "eagle-import:SOIC127P600X173-8N")
      (libsource (lib "eagle-import") (part "AT24CXXSOIC8"))
    )
    (comp (ref "KK1")
      (value "PMB-1")
      (footprint "eagle-import:PCB-MB")
      (libsource (lib "eagle-import") (part "PCB-MB"))
    )
    (comp (ref "KK2")
      (value "PMB-1")
      (footprint "eagle-import:PCB-MB")
      (libsource (lib "eagle-import") (part "PCB-MB"))
    )
    (comp (ref "OK1")
      (value "TLP291-GB.SE-T")
      (footprint "eagle-import:SO4")
      (libsource (lib "eagle-import") (part "TLP291"))
    )
    (comp (ref "Q4")
      (value "2N7002")
      (footprint "eagle-import:SOT103P240X110-3N")
      (fields (field (name "MPN") "2N7002-7-F"))
      (libsource (lib "eagle-import") (part "2N7002"))
    )
    (comp (ref "R13")
      (value "10R")
      (footprint "eagle-import:R1206")
      (libsource (lib "eagle-import") (part "R-EU_R1206"))
    )
    (comp (ref "R14")
      (value "47K")
      (footprint "eagle-import:R0805")
      (libsource (lib "eagle-import") (part "R-EU_R0805"))
    )
    (comp (ref "R15")
      (value "10R")
      (footprint "eagle-import:R1206")
      (libsource (lib "eagle-import") (part "R-EU_R1206"))
    )
    (comp (ref "R16")
      (value "10R")
      (footprint "eagle-import:R1206")
      (libsource (lib "eagle-import") (part "R-EU_R1206"))
    )
    (comp (ref "R17")
      (value "2K2")
      (footprint "eagle-import:R0805")
      (libsource (lib "eagle-import") (part "R-EU_R0805"))
    )
    (comp (ref "R18")
      (value "10K")
      (footprint "eagle-import:R0805")
      (libsource (lib "eagle-import") (part "R-EU_R0805"))
    )
    (comp (ref "R19")
      (value "86K6")
      (footprint "eagle-import:R0805")
      (libsource (lib "eagle-import") (part "R-EU_R0805"))
    )
    (comp (ref "R20")
      (value "330K")
      (footprint "eagle-import:R0805")
      (libsource (lib "eagle-import") (part "R-EU_R0805"))
    )
    (comp (ref "R21")
      (value "86K6")
      (footprint "eagle-import:R0805")
      (libsource (lib "eagle-import") (part "R-EU_R0805"))
    )
    (comp (ref "R22")
      (value "8K2")
      (footprint "eagle-import:R0805")
      (libsource (lib "eagle-import") (part "R-EU_R0805"))
    )
    (comp (ref "R23")
      (value "10K")
      (footprint "eagle-import:R0805")
      (libsource (lib "eagle-import") (part "R-EU_R0805"))
    )
    (comp (ref "R24")
      (value "10K")
      (footprint "eagle-import:R0805")
      (libsource (lib "eagle-import") (part "R-EU_R0805"))
    )
    (comp (ref "R25")
      (value "10K")
      (footprint "eagle-import:R0805")
      (libsource (lib "eagle-import") (part "R-EU_R0805"))
    )
    (comp (ref "R26")
      (value "10K")
      (footprint "eagle-import:R0805")
      (libsource (lib "eagle-import") (part "R-EU_R0805"))
    )
    (comp (ref "R27")
      (value "100R")
      (footprint "eagle-import:R0805")
      (libsource (lib "eagle-import") (part "R-EU_R0805"))
    )
    (comp (ref "R28")
      (value "4K7")
      (footprint "eagle-import:R0805")
      (libsource (lib "eagle-import") (part "R-EU_R0805"))
    )
    (comp (ref "RN1")
      (value "DR1206-33R-4/8")
      (footprint "eagle-import:CAY16")
      (libsource (lib "eagle-import") (part "R_ARRAY4"))
    )
    (comp (ref "TP2")
      (value "TEST-PIN_0.9MM")
      (footprint "eagle-import:TEST-PIN_0.9MM")
      (libsource (lib "eagle-import") (part "TEST-PIN_0.9MM"))
    )
    (comp (ref "TP3")
      (value "TEST-PIN_0.9MM")
      (footprint "eagle-import:TEST-PIN_0.9MM")
      (libsource (lib "eagle-import") (part "TEST-PIN_0.9MM"))
    )
    (comp (ref "TP4")
      (value "TEST-PIN_0.9MM")
      (footprint "eagle-import:TEST-PIN_0.9MM")
      (libsource (lib "eagle-import") (part "TEST-PIN_0.9MM"))
    )
    (comp (ref "TR1")
      (value "SRF0703-821M")
      (footprint "eagle-import:SRF0703")
      (libsource (lib "eagle-import") (part "BOURNS_SRF0703INV"))
    )
    (comp (ref "X4")
      (value "77317-104-28LF")
      (footprint "eagle-import:77317-104-28LF")
      (libsource (lib "eagle-import") (part "77317-104-28LF"))
    )
    (comp (ref "C69")
      (value "10n")
      (footprint "eagle-import:C0805")
      (libsource (lib "eagle-import") (part "C-EUC0805"))
    )
    (comp (ref "C70")
      (value "2n2")
      (footprint "eagle-import:C0805")
      (libsource (lib "eagle-import") (part "C-EUC0805"))
    )
    (comp (ref "C71")
      (value "470n")
      (footprint "eagle-import:C0805")
      (libsource (lib "eagle-import") (part "C-EUC0805"))
    )
    (comp (ref "C72")
      (value "HHXC630A330MHA0")
      (footprint "eagle-import:CAPAE830X1050N")
      (libsource (lib "eagle-import") (part "ECAPSMD8.3MM/HA0"))
    )
    (comp (ref "C73")
      (value "10n/200V")
      (footprint "eagle-import:C1206")
      (libsource (lib "eagle-import") (part "C-EUC1206"))
    )
    (comp (ref "C74")
      (value "10n/200V")
      (footprint "eagle-import:C1206")
      (libsource (lib "eagle-import") (part "C-EUC1206"))
    )
    (comp (ref "C75")
      (value "10n")
      (footprint "eagle-import:C0805")
      (libsource (lib "eagle-import") (part "C-EUC0805"))
    )
    (comp (ref "C76")
      (value "100n")
      (footprint "eagle-import:C0603")
      (libsource (lib "eagle-import") (part "C-EUC0603"))
    )
    (comp (ref "C77")
      (value "100n")
      (footprint "eagle-import:C0603")
      (libsource (lib "eagle-import") (part "C-EUC0603"))
    )
    (comp (ref "C78")
      (value "100n")
      (footprint "eagle-import:C0603")
      (libsource (lib "eagle-import") (part "C-EUC0603"))
    )
    (comp (ref "C79")
      (value "100n")
      (footprint "eagle-import:C0603")
      (libsource (lib "eagle-import") (part "C-EUC0603"))
    )
    (comp (ref "C80")
      (value "100p")
      (footprint "eagle-import:C0805")
      (libsource (lib "eagle-import") (part "C-EUC0805"))
    )
    (comp (ref "C81")
      (value "100p")
      (footprint "eagle-import:C0805")
      (libsource (lib "eagle-import") (part "C-EUC0805"))
    )
    (comp (ref "D17")
      (value "BAS316")
      (footprint "eagle-import:SOD323-R")
      (libsource (lib "eagle-import") (part "DIODESOD323R"))
    )
    (comp (ref "D18")
      (value "BAS316")
      (footprint "eagle-import:SOD323-R")
      (libsource (lib "eagle-import") (part "DIODESOD323R"))
    )
    (comp (ref "D19")
      (value "BAS316")
      (footprint "eagle-import:SOD323-R")
      (libsource (lib "eagle-import") (part "DIODESOD323R"))
    )
    (comp (ref "D20")
      (value "BAS316")
      (footprint "eagle-import:SOD323-R")
      (libsource (lib "eagle-import") (part "DIODESOD323R"))
    )
    (comp (ref "F1")
      (value "ZH32")
      (footprint "eagle-import:ZH32")
      (libsource (lib "eagle-import") (part "ZH32"))
    )
    (comp (ref "IC13")
      (value "SN74LVC2G08DCTR")
      (footprint "eagle-import:DCT8")
      (libsource (lib "eagle-import") (part "SN74LVC2G08DCTR"))
    )
    (comp (ref "IC14")
      (value "SN74LVC1G3157DCKR")
      (footprint "eagle-import:SOT65P210X110-6N")
      (libsource (lib "eagle-import") (part "SN74LVC1G3157-DCK"))
    )
    (comp (ref "IC15")
      (value "LM293D")
      (footprint "eagle-import:SOIC127P600X173-8N")
      (libsource (lib "eagle-import") (part "LM293D"))
    )
    (comp (ref "IC16")
      (value "OPA202IDBV")
      (footprint "eagle-import:DBV5")
      (libsource (lib "eagle-import") (part "OPA376AIDBVR"))
    )
    (comp (ref "IC17")
      (value "SN74LVC1G3157DCKR")
      (footprint "eagle-import:SOT65P210X110-6N")
      (libsource (lib "eagle-import") (part "SN74LVC1G3157-DCK"))
    )
    (comp (ref "J2")
      (value "FCR7350R")
      (footprint "eagle-import:S16N-PC")
      (libsource (lib "eagle-import") (part "BINDING_POSTCLIFF"))
    )
    (comp (ref "J3")
      (value "FCR7350B")
      (footprint "eagle-import:S16N-PC")
      (libsource (lib "eagle-import") (part "BINDING_POSTCLIFF"))
    )
    (comp (ref "JP2")
      (value "JP2-NOCUT-0805")
      (footprint "eagle-import:JP2-0805-NOCUT")
      (libsource (lib "eagle-import") (part "JP2-NOCUT-0805"))
    )
    (comp (ref "JP3")
      (value "JP2-NOCUT-0805")
      (footprint "eagle-import:JP2-0805-NOCUT")
      (libsource (lib "eagle-import") (part "JP2-NOCUT-0805"))
    )
    (comp (ref "K1")
      (value "FTR-C1GA005G-B05")
      (footprint "eagle-import:FTR-C1")
      (libsource (lib "eagle-import") (part "FTR-C1"))
    )
    (comp (ref "LED1")
      (value "WP934MD/2LID")
      (footprint "eagle-import:WP934MD")
      (libsource (lib "eagle-import") (part "WP934MD/2LID"))
    )
    (comp (ref "Q16")
      (value "MMBT5551")
      (footprint "eagle-import:SOT23-BEC")
      (libsource (lib "eagle-import") (part "-NPN-SOT23-BECMMBT5551LT1"))
    )
    (comp (ref "Q17")
      (value "MMBT5401")
      (footprint "eagle-import:SOT23-BEC")
      (libsource (lib "eagle-import") (part "-PNP-SOT23-BECBC857B"))
    )
    (comp (ref "Q18")
      (value "MMBT5551")
      (footprint "eagle-import:SOT23-BEC")
      (libsource (lib "eagle-import") (part "-NPN-SOT23-BECMMBT5551LT1"))
    )
    (comp (ref "Q19")
      (value "MMBT5551")
      (footprint "eagle-import:SOT23-BEC")
      (libsource (lib "eagle-import") (part "-NPN-SOT23-BECMMBT5551LT1"))
    )
    (comp (ref "Q20")
      (value "2N7002")
      (footprint "eagle-import:SOT103P240X110-3N")
      (fields (field (name "MPN") "2N7002-7-F"))
      (libsource (lib "eagle-import") (part "2N7002"))
    )
    (comp (ref "R77")
      (value "330R")
      (footprint "eagle-import:R0805")
      (libsource (lib "eagle-import") (part "R-EU_R0805"))
    )
    (comp (ref "R78")
      (value "47K")
      (footprint "eagle-import:R0805")
      (libsource (lib "eagle-import") (part "R-EU_R0805"))
    )
    (comp (ref "R79")
      (value "47K")
      (footprint "eagle-import:R0805")
      (libsource (lib "eagle-import") (part "R-EU_R0805"))
    )
    (comp (ref "R80")
      (value "750R")
      (footprint "eagle-import:R0805")
      (libsource (lib "eagle-import") (part "R-EU_R0805"))
    )
    (comp (ref "R81")
      (value "1K")
      (footprint "eagle-import:R0805")
      (libsource (lib "eagle-import") (part "R-EU_R0805"))
    )
    (comp (ref "R82")
      (value "2K2")
      (footprint "eagle-import:R0805")
      (libsource (lib "eagle-import") (part "R-EU_R0805"))
    )
    (comp (ref "R83")
      (value "1R")
      (footprint "eagle-import:R1206")
      (libsource (lib "eagle-import") (part "R-EU_R1206"))
    )
    (comp (ref "R84")
      (value "10K")
      (footprint "eagle-import:R0805")
      (libsource (lib "eagle-import") (part "R-EU_R0805"))
    )
    (comp (ref "R85")
      (value "10K")
      (footprint "eagle-import:R0805")
      (libsource (lib "eagle-import") (part "R-EU_R0805"))
    )
    (comp (ref "R86")
      (value "750R")
      (footprint "eagle-import:R0805")
      (libsource (lib "eagle-import") (part "R-EU_R0805"))
    )
    (comp (ref "R87")
      (value "47K")
      (footprint "eagle-import:R0805")
      (libsource (lib "eagle-import") (part "R-EU_R0805"))
    )
    (comp (ref "R88")
      (value "330R")
      (footprint "eagle-import:R0805")
      (libsource (lib "eagle-import") (part "R-EU_R0805"))
    )
    (comp (ref "R89")
      (value "4K7")
      (footprint "eagle-import:R0805")
      (libsource (lib "eagle-import") (part "R-EU_R0805"))
    )
    (comp (ref "R90")
      (value "4K7")
      (footprint "eagle-import:R0805")
      (libsource (lib "eagle-import") (part "R-EU_R0805"))
    )
    (comp (ref "R91")
      (value "470R")
      (footprint "eagle-import:R0805")
      (libsource (lib "eagle-import") (part "R-EU_R0805"))
    )
    (comp (ref "R92")
      (value "470R")
      (footprint "eagle-import:R0805")
      (libsource (lib "eagle-import") (part "R-EU_R0805"))
    )
    (comp (ref "R93")
      (value "10K")
      (footprint "eagle-import:R0805")
      (libsource (lib "eagle-import") (part "R-EU_R0805"))
    )
    (comp (ref "R94")
      (value "10K")
      (footprint "eagle-import:R0805")
      (libsource (lib "eagle-import") (part "R-EU_R0805"))
    )
    (comp (ref "R95")
      (value "1K")
      (footprint "eagle-import:R0805")
      (libsource (lib "eagle-import") (part "R-EU_R0805"))
    )
    (comp (ref "R96")
      (value "1K")
      (footprint "eagle-import:R0805")
      (libsource (lib "eagle-import") (part "R-EU_R0805"))
    )
    (comp (ref "R97")
      (value "100K")
      (footprint "eagle-import:R0805")
      (libsource (lib "eagle-import") (part "R-EU_R0805"))
    )
    (comp (ref "R98")
      (value "10K")
      (footprint "eagle-import:R0805")
      (libsource (lib "eagle-import") (part "R-EU_R0805"))
    )
    (comp (ref "R99")
      (value "10K")
      (footprint "eagle-import:R0805")
      (libsource (lib "eagle-import") (part "R-EU_R0805"))
    )
    (comp (ref "X5")
      (value "DS1024-2*10R0")
      (footprint "eagle-import:SSW-110-02-T-D-RA")
      (libsource (lib "eagle-import") (part "SSW-110-02-T-D-RA"))
    )
    (comp (ref "X6")
      (value "691322110005")
      (footprint "eagle-import:MC1,5_5-G-3,5")
      (libsource (lib "eagle-import") (part "MC1,5/5-G-3,5"))
    )
    (comp (ref "ZD4")
      (value "SMAJ51A")
      (footprint "eagle-import:DO214AA")
      (libsource (lib "eagle-import") (part "P6SMB68A"))
    )
    (comp (ref "ZD5")
      (value "SLVU2.8-TP")
      (footprint "eagle-import:SOT23")
      (libsource (lib "eagle-import") (part "SLVU2.8"))
    )
  )
  (nets
    (net (code "1") (name "+3V3") (class "Default")
      (node (ref "C101") (pin "2") (pinfunction "2_2") (pintype "passive"))
      (node (ref "C34") (pin "2") (pinfunction "2_2") (pintype "passive"))
      (node (ref "C37") (pin "1") (pinfunction "1_1") (pintype "passive"))
      (node (ref "C41") (pin "2") (pinfunction "2_2") (pintype "passive"))
      (node (ref "C67") (pin "1") (pinfunction "1_1") (pintype "passive"))
      (node (ref "C78") (pin "2") (pinfunction "2_2") (pintype "passive"))
      (node (ref "C86") (pin "1") (pinfunction "1_1") (pintype "passive"))
      (node (ref "C87") (pin "1") (pinfunction "1_1") (pintype "passive"))
      (node (ref "C88") (pin "2") (pinfunction "2_2") (pintype "passive"))
      (node (ref "C93") (pin "2") (pinfunction "2_2") (pintype "passive"))
      (node (ref "C94") (pin "1") (pinfunction "1_1") (pintype "passive"))
      (node (ref "C95") (pin "2") (pinfunction "2_2") (pintype "passive"))
      (node (ref "FB4") (pin "P$1") (pinfunction "1_P$1") (pintype "passive"))
      (node (ref "IC12") (pin "5") (pinfunction "VDD_5") (pintype "power_in"))
      (node (ref "IC13") (pin "8") (pinfunction "VDD_8") (pintype "power_in"))
      (node (ref "IC14") (pin "5") (pinfunction "VDD_5") (pintype "power_in"))
      (node (ref "IC17") (pin "5") (pinfunction "VDD_5") (pintype "power_in"))
      (node (ref "IC20") (pin "1") (pinfunction "VDD_1") (pintype "power_in"))
      (node (ref "IC22") (pin "17") (pinfunction "VDD_2_17") (pintype "passive"))
      (node (ref "IC22") (pin "48") (pinfunction "VDD_1_48") (pintype "bidirectional"))
      (node (ref "IC23") (pin "7") (pinfunction "~{PRE}_7") (pintype "input"))
      (node (ref "IC23") (pin "8") (pinfunction "VDD_8") (pintype "power_in"))
      (node (ref "IC3") (pin "16") (pinfunction "VDD2_16") (pintype "passive"))
      (node (ref "IC5") (pin "5") (pinfunction "OUT_5") (pintype "passive"))
      (node (ref "IC7") (pin "10") (pinfunction "EN2_10") (pintype "input"))
      (node (ref "IC7") (pin "16") (pinfunction "VDD2_16") (pintype "passive"))
      (node (ref "NTC1") (pin "1") (pinfunction "P$1_1") (pintype "bidirectional"))
      (node (ref "Q13") (pin "B") (pinfunction "B_B") (pintype "passive"))
      (node (ref "Q28") (pin "2") (pinfunction "S_2") (pintype "passive"))
      (node (ref "Q4") (pin "3") (pinfunction "D_3") (pintype "passive"))
      (node (ref "R101") (pin "2") (pinfunction "2_2") (pintype "passive"))
      (node (ref "R113") (pin "2") (pinfunction "2_2") (pintype "passive"))
      (node (ref "R117") (pin "1") (pinfunction "1_1") (pintype "passive"))
      (node (ref "R123") (pin "1") (pinfunction "1_1") (pintype "passive"))
      (node (ref "R124") (pin "1") (pinfunction "1_1") (pintype "passive"))
      (node (ref "R126") (pin "1") (pinfunction "1_1") (pintype "passive"))
      (node (ref "R18") (pin "1") (pinfunction "1_1") (pintype "passive"))
      (node (ref "R23") (pin "2") (pinfunction "2_2") (pintype "passive"))
      (node (ref "R85") (pin "2") (pinfunction "2_2") (pintype "passive"))
      (node (ref "R89") (pin "1") (pinfunction "1_1") (pintype "passive"))
      (node (ref "R90") (pin "1") (pinfunction "1_1") (pintype "passive"))
      (node (ref "TP3") (pin "1") (pinfunction "P$1_1") (pintype "bidirectional"))
    )
    (net (code "2") (name "+3V3_DIB") (class "Default")
      (node (ref "C33") (pin "1") (pinfunction "1_1") (pintype "passive"))
      (node (ref "C40") (pin "1") (pinfunction "1_1") (pintype "passive"))
      (node (ref "C43") (pin "2") (pinfunction "2_2") (pintype "passive"))
      (node (ref "IC3") (pin "1") (pinfunction "VDD1_1") (pintype "passive"))
      (node (ref "IC7") (pin "1") (pinfunction "VDD1_1") (pintype "passive"))
      (node (ref "IC8") (pin "8") (pinfunction "VCC_8") (pintype "power_in"))
      (node (ref "OK1") (pin "4") (pinfunction "COL_4") (pintype "passive"))
      (node (ref "R24") (pin "1") (pinfunction "1_1") (pintype "passive"))
      (node (ref "R25") (pin "1") (pinfunction "1_1") (pintype "passive"))
      (node (ref "R26") (pin "1") (pinfunction "1_1") (pintype "passive"))
      (node (ref "X4") (pin "1") (pinfunction "1_1") (pintype "passive"))
    )
    (net (code "3") (name "+5V") (class "Default")
      (node (ref "C38") (pin "2") (pinfunction "2_2") (pintype "passive"))
      (node (ref "D17") (pin "C") (pinfunction "C_C") (pintype "passive"))
      (node (ref "FB2") (pin "P$2") (pinfunction "2_P$2") (pintype "passive"))
      (node (ref "IC5") (pin "1") (pinfunction "IN_1") (pintype "input"))
      (node (ref "IC5") (pin "3") (pinfunction "ON/~{OFF}_3") (pintype "input"))
      (node (ref "K1") (pin "1") (pinfunction "C1_1") (pintype "passive"))
      (node (ref "LED1") (pin "TA") (pinfunction "A_TA") (pintype "passive"))
      (node (ref "LED2") (pin "BA") (pinfunction "A_BA") (pintype "passive"))
      (node (ref "LED2") (pin "TA") (pinfunction "A_TA") (pintype "passive"))
      (node (ref "Q29") (pin "2") (pinfunction "S_2") (pintype "passive"))
      (node (ref "Q30") (pin "2") (pinfunction "S_2") (pintype "passive"))
    )
    (net (code "4") (name "+VNR") (class "Default")
      (node (ref "C30") (pin "1") (pinfunction "1_1") (pintype "passive"))
      (node (ref "D2") (pin "A") (pinfunction "A_A") (pintype "passive"))
      (node (ref "IC4") (pin "8") (pinfunction "VI_8") (pintype "input"))
      (node (ref "R15") (pin "1") (pinfunction "1_1") (pintype "passive"))
      (node (ref "X2") (pin "1") (pinfunction "1_1") (pintype "passive"))
    )
    (net (code "5") (name "+VREF") (class "Default")
      (node (ref "C89") (pin "2") (pinfunction "2_2") (pintype "passive"))
      (node (ref "C91") (pin "+") (pinfunction "+_+") (pintype "passive"))
      (node (ref "C99") (pin "2") (pinfunction "2_2") (pintype "passive"))
      (node (ref "IC20") (pin "2") (pinfunction "VREF_2") (pintype "input"))
      (node (ref "IC21") (pin "6") (pinfunction "VOUT_6") (pintype "output"))
      (node (ref "IC22") (pin "25") (pinfunction "VREFSD+_25") (pintype "passive"))
      (node (ref "IC22") (pin "9") (pinfunction "VDDA/VREF+_9") (pintype "passive"))
      (node (ref "R30") (pin "1") (pinfunction "1_1") (pintype "passive"))
    )
    (net (code "6") (name "-9V") (class "Default")
      (node (ref "C24") (pin "1") (pinfunction "1_1") (pintype "passive"))
      (node (ref "IC6") (pin "2") (pinfunction "IN_2") (pintype "input"))
      (node (ref "IC6") (pin "3") (pinfunction "IN_3") (pintype "input"))
      (node (ref "IC6") (pin "6") (pinfunction "IN_6") (pintype "input"))
      (node (ref "IC6") (pin "7") (pinfunction "IN_7") (pintype "input"))
      (node (ref "R13") (pin "1") (pinfunction "1_1") (pintype "passive"))
      (node (ref "R41") (pin "2") (pinfunction "2_2") (pintype "passive"))
      (node (ref "R44") (pin "2") (pinfunction "2_2") (pintype "passive"))
    )
    (net (code "7") (name "AGND") (class "Default")
      (node (ref "C21") (pin "2") (pinfunction "2_2") (pintype "passive"))
      (node (ref "IC1") (pin "6") (pinfunction "AGND_6") (pintype "power_in"))
      (node (ref "R12") (pin "2") (pinfunction "2_2") (pintype "passive"))
      (node (ref "R3") (pin "1") (pinfunction "1_1") (pintype "passive"))
      (node (ref "R9") (pin "1") (pinfunction "1_1") (pintype "passive"))
      (node (ref "SH2") (pin "1") (pinfunction "GND_A_1") (pintype "bidirectional"))
    )
    (net (code "8") (name "AUX_ISET_SW") (class "Default")
      (node (ref "IC13") (pin "6") (pinfunction "I1_6") (pintype "input"))
      (node (ref "IC22") (pin "45") (pinfunction "PB8_45") (pintype "bidirectional"))
    )
    (net (code "9") (name "AUX_OUT") (class "Default")
      (node (ref "IC14") (pin "1") (pinfunction "NO_1") (pintype "bidirectional"))
      (node (ref "IC17") (pin "1") (pinfunction "NO_1") (pintype "bidirectional"))
      (node (ref "R96") (pin "1") (pinfunction "1_1") (pintype "passive"))
    )
    (net (code "10") (name "AUX_USET_SW") (class "Default")
      (node (ref "IC13") (pin "1") (pinfunction "I0_1") (pintype "input"))
      (node (ref "IC22") (pin "46") (pinfunction "PB9_46") (pintype "bidirectional"))
    )
    (net (code "11") (name "BOOT0") (class "Default")
      (node (ref "IC22") (pin "44") (pinfunction "BOOT0_44") (pintype "input"))
      (node (ref "IC7") (pin "13") (pinfunction "B2_13") (pintype "output"))
      (node (ref "R122") (pin "2") (pinfunction "2_2") (pintype "passive"))
    )
    (net (code "12") (name "CC_ACTIVE") (class "Default")
      (node (ref "IC22") (pin "2") (pinfunction "PC13_2") (pintype "bidirectional"))
      (node (ref "R113") (pin "1") (pinfunction "1_1") (pintype "passive"))
      (node (ref "R115") (pin "2") (pinfunction "2_2") (pintype "passive"))
    )
    (net (code "13") (name "CC_LED_OUT") (class "Default")
      (node (ref "IC22") (pin "35") (pinfunction "PF6_35") (pintype "bidirectional"))
      (node (ref "Q27") (pin "1") (pinfunction "G_1") (pintype "passive"))
    )
    (net (code "14") (name "CURR_HI") (class "Default")
      (node (ref "IC12") (pin "6") (pinfunction "CTRL_6") (pintype "input"))
      (node (ref "IC22") (pin "4") (pinfunction "PC15-OSC32_OUT_4") (pintype "bidirectional"))
      (node (ref "Q15") (pin "4") (pinfunction "G_4") (pintype "passive"))
      (node (ref "R71") (pin "2") (pinfunction "2_2") (pintype "passive"))
    )
    (net (code "15") (name "CURR_LO") (class "Default")
      (node (ref "IC22") (pin "5") (pinfunction "PF0-OSC_IN_5") (pintype "bidirectional"))
      (node (ref "Q14") (pin "4") (pinfunction "G_4") (pintype "passive"))
      (node (ref "R70") (pin "2") (pinfunction "2_2") (pintype "passive"))
    )
    (net (code "16") (name "CV_ACTIVE") (class "Default")
      (node (ref "IC22") (pin "3") (pinfunction "PC14-OSC32_IN_3") (pintype "bidirectional"))
      (node (ref "R101") (pin "1") (pinfunction "1_1") (pintype "passive"))
      (node (ref "R103") (pin "2") (pinfunction "2_2") (pintype "passive"))
    )
    (net (code "17") (name "CV_LED_OUT") (class "Default")
      (node (ref "IC22") (pin "29") (pinfunction "PA8_29") (pintype "bidirectional"))
      (node (ref "Q26") (pin "1") (pinfunction "G_1") (pintype "passive"))
    )
    (net (code "18") (name "DAC_CS") (class "Default")
      (node (ref "IC20") (pin "5") (pinfunction "~{SYNC}_5") (pintype "input"))
      (node (ref "IC22") (pin "14") (pinfunction "PA4_14") (pintype "bidirectional"))
    )
    (net (code "19") (name "DAC_MOSI") (class "Default")
      (node (ref "IC20") (pin "7") (pinfunction "DIN_7") (pintype "input"))
      (node (ref "IC22") (pin "13") (pinfunction "PA3_13") (pintype "bidirectional"))
    )
    (net (code "20") (name "DAC_SCLK") (class "Default")
      (node (ref "IC20") (pin "6") (pinfunction "SCLK_6") (pintype "input"))
      (node (ref "IC22") (pin "11") (pinfunction "PA1_11") (pintype "bidirectional"))
    )
    (net (code "21") (name "DC+") (class "Default")
      (node (ref "C1") (pin "2") (pinfunction "2_2") (pintype "passive"))
      (node (ref "L1") (pin "1") (pinfunction "1_1") (pintype "passive"))
      (node (ref "R1") (pin "2") (pinfunction "2_2") (pintype "passive"))
      (node (ref "X1") (pin "1") (pinfunction "1_1") (pintype "passive"))
    )
    (net (code "22") (name "DC-") (class "Default")
      (node (ref "C1") (pin "1") (pinfunction "1_1") (pintype "passive"))
      (node (ref "L1") (pin "3") (pinfunction "1_3") (pintype "passive"))
      (node (ref "R1") (pin "1") (pinfunction "1_1") (pintype "passive"))
      (node (ref "X1") (pin "2") (pinfunction "1_2") (pintype "passive"))
    )
    (net (code "23") (name "DC_OUT") (class "Default")
      (node (ref "C25") (pin "1") (pinfunction "1_1") (pintype "passive"))
      (node (ref "C26") (pin "1") (pinfunction "1_1") (pintype "passive"))
      (node (ref "C3") (pin "2") (pinfunction "2_2") (pintype "passive"))
      (node (ref "C4") (pin "+") (pinfunction "+_+") (pintype "passive"))
      (node (ref "C5") (pin "1") (pinfunction "1_1") (pintype "passive"))
      (node (ref "C6") (pin "1") (pinfunction "1_1") (pintype "passive"))
      (node (ref "C7") (pin "1") (pinfunction "1_1") (pintype "passive"))
      (node (ref "C7A") (pin "2") (pinfunction "2_2") (pintype "passive"))
      (node (ref "C9") (pin "2") (pinfunction "2_2") (pintype "passive"))
      (node (ref "IC1") (pin "20") (pinfunction "VIN_20") (pintype "power_in"))
      (node (ref "IC2") (pin "2") (pinfunction "VIN_2") (pintype "power_in"))
      (node (ref "L1") (pin "2") (pinfunction "2_2") (pintype "passive"))
      (node (ref "Q1") (pin "5") (pinfunction "D_5") (pintype "passive"))
      (node (ref "Q1") (pin "6") (pinfunction "D_6") (pintype "passive"))
      (node (ref "Q1") (pin "7") (pinfunction "D_7") (pintype "passive"))
      (node (ref "Q1") (pin "8") (pinfunction "D_8") (pintype "passive"))
      (node (ref "R14") (pin "2") (pinfunction "2_2") (pintype "passive"))
      (node (ref "R36") (pin "1") (pinfunction "1_1") (pintype "passive"))
      (node (ref "X2") (pin "10") (pinfunction "1_10") (pintype "passive"))
      (node (ref "X2") (pin "7") (pinfunction "1_7") (pintype "passive"))
      (node (ref "X2") (pin "8") (pinfunction "1_8") (pintype "passive"))
      (node (ref "X2") (pin "9") (pinfunction "1_9") (pintype "passive"))
      (node (ref "ZD1") (pin "C") (pinfunction "C_C") (pintype "passive"))
    )
    (net (code "24") (name "DIB_A0") (class "Default")
      (node (ref "IC8") (pin "1") (pinfunction "A0_1") (pintype "input"))
      (node (ref "R26") (pin "2") (pinfunction "2_2") (pintype "passive"))
      (node (ref "X4") (pin "17") (pinfunction "1_17") (pintype "passive"))
    )
    (net (code "25") (name "DIB_A1") (class "Default")
      (node (ref "IC8") (pin "2") (pinfunction "A1_2") (pintype "input"))
      (node (ref "R25") (pin "2") (pinfunction "2_2") (pintype "passive"))
      (node (ref "X4") (pin "19") (pinfunction "1_19") (pintype "passive"))
    )
    (net (code "26") (name "DIB_A2") (class "Default")
      (node (ref "IC8") (pin "3") (pinfunction "A2_3") (pintype "input"))
      (node (ref "R24") (pin "2") (pinfunction "2_2") (pintype "passive"))
      (node (ref "X4") (pin "18") (pinfunction "1_18") (pintype "passive"))
    )
    (net (code "27") (name "DIB_BOOT0") (class "Default")
      (node (ref "IC7") (pin "4") (pinfunction "A2_4") (pintype "input"))
      (node (ref "IC7") (pin "7") (pinfunction "EN1_7") (pintype "input"))
      (node (ref "X4") (pin "26") (pinfunction "1_26") (pintype "passive"))
    )
    (net (code "28") (name "DIB_CSA") (class "Default")
      (node (ref "IC3") (pin "5") (pinfunction "A4_5") (pintype "input"))
      (node (ref "X4") (pin "9") (pinfunction "1_9") (pintype "passive"))
    )
    (net (code "29") (name "DIB_CSB") (class "Default")
      (node (ref "DIB1.1") (pin "NO") (pinfunction "NO_NO") (pintype "passive"))
      (node (ref "X4") (pin "12") (pinfunction "1_12") (pintype "passive"))
    )
    (net (code "30") (name "DIB_FAULT") (class "Default")
      (node (ref "OK1") (pin "3") (pinfunction "EMIT_3") (pintype "passive"))
      (node (ref "R28") (pin "2") (pinfunction "2_2") (pintype "passive"))
      (node (ref "X4") (pin "3") (pinfunction "1_3") (pintype "passive"))
    )
    (net (code "31") (name "DIB_IRQ") (class "Default")
      (node (ref "DIB1.1") (pin "NC") (pinfunction "NC_NC") (pintype "passive"))
      (node (ref "X4") (pin "10") (pinfunction "1_10") (pintype "passive"))
    )
    (net (code "32") (name "DIB_MISO") (class "Default")
      (node (ref "IC3") (pin "6") (pinfunction "A5_6") (pintype "output"))
      (node (ref "X4") (pin "14") (pinfunction "1_14") (pintype "passive"))
    )
    (net (code "33") (name "DIB_MOSI") (class "Default")
      (node (ref "IC7") (pin "3") (pinfunction "A1_3") (pintype "input"))
      (node (ref "X4") (pin "15") (pinfunction "1_15") (pintype "passive"))
    )
    (net (code "34") (name "DIB_NRESET") (class "Default")
      (node (ref "IC3") (pin "2") (pinfunction "A1_2") (pintype "input"))
      (node (ref "X4") (pin "4") (pinfunction "1_4") (pintype "passive"))
    )
    (net (code "35") (name "DIB_SCL") (class "Default")
      (node (ref "IC8") (pin "6") (pinfunction "SCL_6") (pintype "bidirectional"))
      (node (ref "X4") (pin "5") (pinfunction "1_5") (pintype "passive"))
    )
    (net (code "36") (name "DIB_SCLK") (class "Default")
      (node (ref "IC3") (pin "4") (pinfunction "A3_4") (pintype "input"))
      (node (ref "X4") (pin "13") (pinfunction "1_13") (pintype "passive"))
    )
    (net (code "37") (name "DIB_SDA") (class "Default")
      (node (ref "IC8") (pin "5") (pinfunction "SDA_5") (pintype "bidirectional"))
      (node (ref "X4") (pin "8") (pinfunction "1_8") (pintype "passive"))
    )
    (net (code "38") (name "DIB_SYNC") (class "Default")
      (node (ref "IC3") (pin "3") (pinfunction "A2_3") (pintype "input"))
      (node (ref "X4") (pin "6") (pinfunction "1_6") (pintype "passive"))
    )
    (net (code "39") (name "DIB_UART_RX") (class "Default")
      (node (ref "IC7") (pin "6") (pinfunction "A4_6") (pintype "output"))
      (node (ref "X4") (pin "27") (pinfunction "1_27") (pintype "passive"))
    )
    (net (code "40") (name "DIB_UART_TX") (class "Default")
      (node (ref "IC7") (pin "5") (pinfunction "A3_5") (pintype "input"))
      (node (ref "X4") (pin "28") (pinfunction "1_28") (pintype "passive"))
    )
    (net (code "41") (name "EN_ULVO") (class "Default")
      (node (ref "D1") (pin "C") (pinfunction "C_C") (pintype "passive"))
      (node (ref "IC1") (pin "1") (pinfunction "EN_UVLO_1") (pintype "input"))
      (node (ref "R3") (pin "2") (pinfunction "2_2") (pintype "passive"))
      (node (ref "X2") (pin "2") (pinfunction "1_2") (pintype "passive"))
    )
    (net (code "42") (name "FB") (class "Default")
      (node (ref "C20") (pin "1") (pinfunction "1_1") (pintype "passive"))
      (node (ref "C22") (pin "1") (pinfunction "1_1") (pintype "passive"))
      (node (ref "IC1") (pin "5") (pinfunction "FB_5") (pintype "input"))
      (node (ref "Q3") (pin "C") (pinfunction "C_C") (pintype "passive"))
      (node (ref "R12") (pin "1") (pinfunction "1_1") (pintype "passive"))
      (node (ref "R6") (pin "2") (pinfunction "2_2") (pintype "passive"))
    )
    (net (code "43") (name "GCOM") (class "Default")
      (node (ref "C80") (pin "1") (pinfunction "1_1") (pintype "passive"))
      (node (ref "IC10") (pin "6") (pinfunction "-IN_6") (pintype "input"))
      (node (ref "IC10") (pin "7") (pinfunction "OUT_7") (pintype "output"))
      (node (ref "R42") (pin "1") (pinfunction "1_1") (pintype "passive"))
      (node (ref "R65") (pin "1") (pinfunction "1_1") (pintype "passive"))
      (node (ref "R93") (pin "1") (pinfunction "1_1") (pintype "passive"))
    )
    (net (code "44") (name "GND") (class "Default")
      (node (ref "C100") (pin "1") (pinfunction "1_1") (pintype "passive"))
      (node (ref "C101") (pin "1") (pinfunction "1_1") (pintype "passive"))
      (node (ref "C102") (pin "1") (pinfunction "1_1") (pintype "passive"))
      (node (ref "C103") (pin "1") (pinfunction "1_1") (pintype "passive"))
      (node (ref "C104") (pin "1") (pinfunction "1_1") (pintype "passive"))
      (node (ref "C105") (pin "1") (pinfunction "1_1") (pintype "passive"))
      (node (ref "C23") (pin "2") (pinfunction "2_2") (pintype "passive"))
      (node (ref "C24") (pin "2") (pinfunction "2_2") (pintype "passive"))
      (node (ref "C25") (pin "2") (pinfunction "2_2") (pintype "passive"))
      (node (ref "C26") (pin "2") (pinfunction "2_2") (pintype "passive"))
      (node (ref "C29") (pin "2") (pinfunction "2_2") (pintype "passive"))
      (node (ref "C30") (pin "2") (pinfunction "2_2") (pintype "passive"))
      (node (ref "C31") (pin "2") (pinfunction "2_2") (pintype "passive"))
      (node (ref "C32") (pin "1") (pinfunction "1_1") (pintype "passive"))
      (node (ref "C34") (pin "1") (pinfunction "1_1") (pintype "passive"))
      (node (ref "C35") (pin "1") (pinfunction "1_1") (pintype "passive"))
      (node (ref "C36") (pin "2") (pinfunction "2_2") (pintype "passive"))
      (node (ref "C37") (pin "2") (pinfunction "2_2") (pintype "passive"))
      (node (ref "C38") (pin "1") (pinfunction "1_1") (pintype "passive"))
      (node (ref "C39") (pin "1") (pinfunction "1_1") (pintype "passive"))
      (node (ref "C41") (pin "1") (pinfunction "1_1") (pintype "passive"))
      (node (ref "C42") (pin "1") (pinfunction "1_1") (pintype "passive"))
      (node (ref "C44") (pin "2") (pinfunction "2_2") (pintype "passive"))
      (node (ref "C45") (pin "2") (pinfunction "2_2") (pintype "passive"))
      (node (ref "C47") (pin "2") (pinfunction "2_2") (pintype "passive"))
      (node (ref "C51") (pin "2") (pinfunction "2_2") (pintype "passive"))
      (node (ref "C54") (pin "1") (pinfunction "1_1") (pintype "passive"))
      (node (ref "C55") (pin "2") (pinfunction "2_2") (pintype "passive"))
      (node (ref "C56") (pin "1") (pinfunction "1_1") (pintype "passive"))
      (node (ref "C57") (pin "1") (pinfunction "1_1") (pintype "passive"))
      (node (ref "C59") (pin "1") (pinfunction "1_1") (pintype "passive"))
      (node (ref "C60") (pin "1") (pinfunction "1_1") (pintype "passive"))
      (node (ref "C61") (pin "2") (pinfunction "2_2") (pintype "passive"))
      (node (ref "C62") (pin "1") (pinfunction "1_1") (pintype "passive"))
      (node (ref "C63") (pin "2") (pinfunction "2_2") (pintype "passive"))
      (node (ref "C64") (pin "1") (pinfunction "1_1") (pintype "passive"))
      (node (ref "C65") (pin "1") (pinfunction "1_1") (pintype "passive"))
      (node (ref "C67") (pin "2") (pinfunction "2_2") (pintype "passive"))
      (node (ref "C76") (pin "2") (pinfunction "2_2") (pintype "passive"))
      (node (ref "C77") (pin "2") (pinfunction "2_2") (pintype "passive"))
      (node (ref "C78") (pin "1") (pinfunction "1_1") (pintype "passive"))
      (node (ref "C79") (pin "2") (pinfunction "2_2") (pintype "passive"))
      (node (ref "C82") (pin "1") (pinfunction "1_1") (pintype "passive"))
      (node (ref "C83") (pin "1") (pinfunction "1_1") (pintype "passive"))
      (node (ref "C85") (pin "1") (pinfunction "1_1") (pintype "passive"))
      (node (ref "C87") (pin "2") (pinfunction "2_2") (pintype "passive"))
      (node (ref "C88") (pin "1") (pinfunction "1_1") (pintype "passive"))
      (node (ref "C89") (pin "1") (pinfunction "1_1") (pintype "passive"))
      (node (ref "C90") (pin "2") (pinfunction "2_2") (pintype "passive"))
      (node (ref "C91") (pin "-") (pinfunction "-_-") (pintype "passive"))
      (node (ref "C92") (pin "2") (pinfunction "2_2") (pintype "passive"))
      (node (ref "C93") (pin "1") (pinfunction "1_1") (pintype "passive"))
      (node (ref "C94") (pin "2") (pinfunction "2_2") (pintype "passive"))
      (node (ref "C95") (pin "1") (pinfunction "1_1") (pintype "passive"))
      (node (ref "C96") (pin "2") (pinfunction "2_2") (pintype "passive"))
      (node (ref "C97") (pin "1") (pinfunction "1_1") (pintype "passive"))
      (node (ref "C98") (pin "1") (pinfunction "1_1") (pintype "passive"))
      (node (ref "C99") (pin "1") (pinfunction "1_1") (pintype "passive"))
      (node (ref "D20") (pin "A") (pinfunction "A_A") (pintype "passive"))
      (node (ref "D22") (pin "C") (pinfunction "C_C") (pintype "passive"))
      (node (ref "D5") (pin "A") (pinfunction "A_A") (pintype "passive"))
      (node (ref "D6") (pin "A") (pinfunction "A_A") (pintype "passive"))
      (node (ref "D7") (pin "C") (pinfunction "C_C") (pintype "passive"))
      (node (ref "GND") (pin "1") (pinfunction "P$1_1") (pintype "bidirectional"))
      (node (ref "IC12") (pin "2") (pinfunction "GND_2") (pintype "passive"))
      (node (ref "IC13") (pin "4") (pinfunction "VSS_4") (pintype "power_in"))
      (node (ref "IC14") (pin "2") (pinfunction "GND_2") (pintype "passive"))
      (node (ref "IC15") (pin "4") (pinfunction "V-_4") (pintype "power_in"))
      (node (ref "IC17") (pin "2") (pinfunction "GND_2") (pintype "passive"))
      (node (ref "IC19") (pin "4") (pinfunction "GND_4") (pintype "passive"))
      (node (ref "IC2") (pin "9") (pinfunction "GND_9") (pintype "passive"))
      (node (ref "IC2") (pin "TP") (pinfunction "TP_TP") (pintype "passive"))
      (node (ref "IC20") (pin "8") (pinfunction "GND_8") (pintype "power_in"))
      (node (ref "IC21") (pin "4") (pinfunction "GND_4") (pintype "passive"))
      (node (ref "IC22") (pin "23") (pinfunction "VSSSD/VREFSD-_23") (pintype "passive"))
      (node (ref "IC22") (pin "47") (pinfunction "VSS_1_47") (pintype "bidirectional"))
      (node (ref "IC22") (pin "8") (pinfunction "VSSA/VREF-_8") (pintype "passive"))
      (node (ref "IC23") (pin "4") (pinfunction "VSS_4") (pintype "power_in"))
      (node (ref "IC3") (pin "9") (pinfunction "GND2_9") (pintype "passive"))
      (node (ref "IC4") (pin "2") (pinfunction "GND_2") (pintype "passive"))
      (node (ref "IC4") (pin "3") (pinfunction "GND_3") (pintype "passive"))
      (node (ref "IC4") (pin "6") (pinfunction "GND_6") (pintype "passive"))
      (node (ref "IC4") (pin "7") (pinfunction "GND_7") (pintype "passive"))
      (node (ref "IC5") (pin "2") (pinfunction "GND_2") (pintype "passive"))
      (node (ref "IC6") (pin "5") (pinfunction "GND_5") (pintype "passive"))
      (node (ref "IC7") (pin "15") (pinfunction "GND2_15") (pintype "passive"))
      (node (ref "IC7") (pin "9") (pinfunction "GND2_2_9") (pintype "passive"))
      (node (ref "Q16") (pin "E") (pinfunction "E_E") (pintype "passive"))
      (node (ref "Q19") (pin "E") (pinfunction "E_E") (pintype "passive"))
      (node (ref "Q20") (pin "2") (pinfunction "S_2") (pintype "passive"))
      (node (ref "Q24") (pin "E") (pinfunction "E_E") (pintype "passive"))
      (node (ref "Q25") (pin "2") (pinfunction "S_2") (pintype "passive"))
      (node (ref "Q26") (pin "2") (pinfunction "S_2") (pintype "passive"))
      (node (ref "Q27") (pin "2") (pinfunction "S_2") (pintype "passive"))
      (node (ref "R100") (pin "1") (pinfunction "1_1") (pintype "passive"))
      (node (ref "R107") (pin "2") (pinfunction "2_2") (pintype "passive"))
      (node (ref "R111") (pin "1") (pinfunction "1_1") (pintype "passive"))
      (node (ref "R112") (pin "1") (pinfunction "1_1") (pintype "passive"))
      (node (ref "R119") (pin "1") (pinfunction "1_1") (pintype "passive"))
      (node (ref "R122") (pin "1") (pinfunction "1_1") (pintype "passive"))
      (node (ref "R127") (pin "2") (pinfunction "2_2") (pintype "passive"))
      (node (ref "R128") (pin "2") (pinfunction "2_2") (pintype "passive"))
      (node (ref "R16") (pin "1") (pinfunction "1_1") (pintype "passive"))
      (node (ref "R17") (pin "1") (pinfunction "1_1") (pintype "passive"))
      (node (ref "R20") (pin "1") (pinfunction "1_1") (pintype "passive"))
      (node (ref "R22") (pin "1") (pinfunction "1_1") (pintype "passive"))
      (node (ref "R27") (pin "1") (pinfunction "1_1") (pintype "passive"))
      (node (ref "R34") (pin "2") (pinfunction "2_2") (pintype "passive"))
      (node (ref "R48") (pin "1") (pinfunction "1_1") (pintype "passive"))
      (node (ref "R49") (pin "1") (pinfunction "1_1") (pintype "passive"))
      (node (ref "R51") (pin "1") (pinfunction "1_1") (pintype "passive"))
      (node (ref "R70") (pin "1") (pinfunction "1_1") (pintype "passive"))
      (node (ref "R71") (pin "1") (pinfunction "1_1") (pintype "passive"))
      (node (ref "R78") (pin "1") (pinfunction "1_1") (pintype "passive"))
      (node (ref "R87") (pin "1") (pinfunction "1_1") (pintype "passive"))
      (node (ref "R92") (pin "1") (pinfunction "1_1") (pintype "passive"))
      (node (ref "R97") (pin "1") (pinfunction "1_1") (pintype "passive"))
      (node (ref "SH1") (pin "2") (pinfunction "GND_B_2") (pintype "bidirectional"))
      (node (ref "TR1") (pin "4") (pinfunction "4_4") (pintype "passive"))
      (node (ref "X7") (pin "3") (pinfunction "1_3") (pintype "passive"))
    )
    (net (code "45") (name "GNDIO") (class "Default")
      (node (ref "C33") (pin "2") (pinfunction "2_2") (pintype "passive"))
      (node (ref "C40") (pin "2") (pinfunction "2_2") (pintype "passive"))
      (node (ref "C43") (pin "1") (pinfunction "1_1") (pintype "passive"))
      (node (ref "IC3") (pin "8") (pinfunction "GND1_8") (pintype "passive"))
      (node (ref "IC7") (pin "2") (pinfunction "GND1_2_2") (pintype "passive"))
      (node (ref "IC7") (pin "8") (pinfunction "GND1_8") (pintype "passive"))
      (node (ref "IC8") (pin "4") (pinfunction "GND_4") (pintype "passive"))
      (node (ref "IC8") (pin "7") (pinfunction "WP_7") (pintype "input"))
      (node (ref "R28") (pin "1") (pinfunction "1_1") (pintype "passive"))
      (node (ref "X4") (pin "11") (pinfunction "1_11") (pintype "passive"))
      (node (ref "X4") (pin "16") (pinfunction "1_16") (pintype "passive"))
      (node (ref "X4") (pin "20") (pinfunction "1_20") (pintype "passive"))
      (node (ref "X4") (pin "25") (pinfunction "1_25") (pintype "passive"))
      (node (ref "X4") (pin "7") (pinfunction "1_7") (pintype "passive"))
    )
    (net (code "46") (name "HO") (class "Default")
      (node (ref "IC1") (pin "18") (pinfunction "HO_18") (pintype "output"))
      (node (ref "Q1") (pin "4") (pinfunction "G_4") (pintype "passive"))
    )
    (net (code "47") (name "IRQ") (class "Default")
      (node (ref "IC22") (pin "33") (pinfunction "PA12_33") (pintype "bidirectional"))
      (node (ref "IC3") (pin "10") (pinfunction "B6_10") (pintype "input"))
    )
    (net (code "48") (name "I_MON") (class "Default")
      (node (ref "IC11") (pin "6") (pinfunction "OUT_6") (pintype "output"))
      (node (ref "IC12") (pin "4") (pinfunction "COM_4") (pintype "bidirectional"))
      (node (ref "R132") (pin "2") (pinfunction "2_2") (pintype "passive"))
      (node (ref "R68") (pin "1") (pinfunction "1_1") (pintype "passive"))
      (node (ref "R73") (pin "2") (pinfunction "2_2") (pintype "passive"))
    )
    (net (code "49") (name "I_MON_AIN") (class "Default")
      (node (ref "C105") (pin "2") (pinfunction "2_2") (pintype "passive"))
      (node (ref "IC22") (pin "22") (pinfunction "PE9_22") (pintype "bidirectional"))
      (node (ref "R132") (pin "1") (pinfunction "1_1") (pintype "passive"))
    )
    (net (code "50") (name "I_SERVO") (class "Default")
      (node (ref "C66") (pin "2") (pinfunction "2_2") (pintype "passive"))
      (node (ref "D14") (pin "C") (pinfunction "C_C") (pintype "passive"))
      (node (ref "D16") (pin "A") (pinfunction "A_A") (pintype "passive"))
      (node (ref "IC10") (pin "1") (pinfunction "OUT_1") (pintype "output"))
      (node (ref "R114") (pin "1") (pinfunction "1_1") (pintype "passive"))
    )
    (net (code "51") (name "I_SET") (class "Default")
      (node (ref "IC15") (pin "5") (pinfunction "+IN_5") (pintype "input"))
      (node (ref "IC17") (pin "3") (pinfunction "NC_3") (pintype "bidirectional"))
      (node (ref "ISET") (pin "2") (pinfunction "2_2") (pintype "passive"))
      (node (ref "R130") (pin "2") (pinfunction "2_2") (pintype "passive"))
    )
    (net (code "52") (name "I_SET_AIN") (class "Default")
      (node (ref "C103") (pin "2") (pinfunction "2_2") (pintype "passive"))
      (node (ref "IC22") (pin "20") (pinfunction "PB2_20") (pintype "bidirectional"))
      (node (ref "R130") (pin "1") (pinfunction "1_1") (pintype "passive"))
    )
    (net (code "53") (name "I_SET_OUT") (class "Default")
      (node (ref "IC17") (pin "4") (pinfunction "COM_4") (pintype "bidirectional"))
      (node (ref "R64") (pin "1") (pinfunction "1_1") (pintype "passive"))
    )
    (net (code "54") (name "LO") (class "Default")
      (node (ref "IC1") (pin "13") (pinfunction "LO_13") (pintype "output"))
      (node (ref "Q2") (pin "4") (pinfunction "G_4") (pintype "passive"))
    )
    (net (code "55") (name "LOOP_CTRL") (class "Default")
      (node (ref "D12") (pin "A") (pinfunction "A_A") (pintype "passive"))
      (node (ref "D14") (pin "A") (pinfunction "A_A") (pintype "passive"))
      (node (ref "R109") (pin "2") (pinfunction "2_2") (pintype "passive"))
      (node (ref "R57") (pin "1") (pinfunction "1_1") (pintype "passive"))
    )
    (net (code "56") (name "MISO") (class "Default")
      (node (ref "IC22") (pin "26") (pinfunction "PB14_26") (pintype "bidirectional"))
      (node (ref "IC3") (pin "11") (pinfunction "B5_11") (pintype "input"))
    )
    (net (code "57") (name "MOSI") (class "Default")
      (node (ref "IC22") (pin "27") (pinfunction "PB15_27") (pintype "bidirectional"))
      (node (ref "RN1") (pin "5") (pinfunction "2_5") (pintype "passive"))
    )
    (net (code "58") (name "NRST") (class "Default")
      (node (ref "C96") (pin "1") (pinfunction "1_1") (pintype "passive"))
      (node (ref "IC22") (pin "7") (pinfunction "NRST_7") (pintype "input"))
      (node (ref "JP5") (pin "2") (pinfunction "2_2") (pintype "passive"))
      (node (ref "R126") (pin "2") (pinfunction "2_2") (pintype "passive"))
      (node (ref "RN2") (pin "3") (pinfunction "1_3") (pintype "passive"))
    )
    (net (code "59") (name "NSS") (class "Default")
      (node (ref "IC22") (pin "32") (pinfunction "PA11_32") (pintype "bidirectional"))
      (node (ref "RN1") (pin "6") (pinfunction "2_6") (pintype "passive"))
    )
    (net (code "60") (name "Net-(C11-Pad2)") (class "Default")
      (node (ref "C11") (pin "2") (pinfunction "2_2") (pintype "passive"))
      (node (ref "R5") (pin "2") (pinfunction "2_2") (pintype "passive"))
    )
    (net (code "61") (name "Net-(C13-Pad1)") (class "Default")
      (node (ref "C13") (pin "1") (pinfunction "1_1") (pintype "passive"))
      (node (ref "C14") (pin "1") (pinfunction "1_1") (pintype "passive"))
      (node (ref "C15") (pin "+") (pinfunction "+_+") (pintype "passive"))
      (node (ref "C17") (pin "1") (pinfunction "1_1") (pintype "passive"))
      (node (ref "L2") (pin "2") (pinfunction "2_2") (pintype "passive"))
      (node (ref "L3") (pin "1") (pinfunction "1_1") (pintype "passive"))
      (node (ref "R2") (pin "2") (pinfunction "2_2") (pintype "passive"))
      (node (ref "R7") (pin "1") (pinfunction "1_1") (pintype "passive"))
      (node (ref "R8") (pin "1") (pinfunction "1_1") (pintype "passive"))
    )
    (net (code "62") (name "Net-(C19-Pad1)") (class "Default")
      (node (ref "C19") (pin "1") (pinfunction "1_1") (pintype "passive"))
      (node (ref "R6") (pin "1") (pinfunction "1_1") (pintype "passive"))
    )
    (net (code "63") (name "Net-(C22-Pad2)") (class "Default")
      (node (ref "C22") (pin "2") (pinfunction "2_2") (pintype "passive"))
      (node (ref "D3") (pin "A") (pinfunction "A_A") (pintype "passive"))
      (node (ref "Q3") (pin "B") (pinfunction "B_B") (pintype "passive"))
      (node (ref "R10") (pin "1") (pinfunction "1_1") (pintype "passive"))
      (node (ref "R8") (pin "2") (pinfunction "2_2") (pintype "passive"))
    )
    (net (code "64") (name "Net-(C23-Pad1)") (class "Default")
      (node (ref "C23") (pin "1") (pinfunction "1_1") (pintype "passive"))
      (node (ref "D4") (pin "A") (pinfunction "A_A") (pintype "passive"))
      (node (ref "R13") (pin "2") (pinfunction "2_2") (pintype "passive"))
    )
    (net (code "65") (name "Net-(C28-Pad2)") (class "Default")
      (node (ref "C28") (pin "2") (pinfunction "2_2") (pintype "passive"))
      (node (ref "R16") (pin "2") (pinfunction "2_2") (pintype "passive"))
    )
    (net (code "66") (name "Net-(C29-Pad1)") (class "Default")
      (node (ref "C29") (pin "1") (pinfunction "1_1") (pintype "passive"))
      (node (ref "R15") (pin "2") (pinfunction "2_2") (pintype "passive"))
      (node (ref "R19") (pin "2") (pinfunction "2_2") (pintype "passive"))
      (node (ref "TR1") (pin "3") (pinfunction "3_3") (pintype "passive"))
    )
    (net (code "67") (name "Net-(C35-Pad2)") (class "Default")
      (node (ref "C35") (pin "2") (pinfunction "2_2") (pintype "passive"))
      (node (ref "R21") (pin "1") (pinfunction "1_1") (pintype "passive"))
    )
    (net (code "68") (name "Net-(C45-Pad1)") (class "Default")
      (node (ref "C45") (pin "1") (pinfunction "1_1") (pintype "passive"))
      (node (ref "Q7") (pin "2") (pinfunction "C_2") (pintype "passive"))
      (node (ref "Q7") (pin "4") (pinfunction "C_4") (pintype "passive"))
      (node (ref "R36") (pin "2") (pinfunction "2_2") (pintype "passive"))
      (node (ref "R38") (pin "2") (pinfunction "2_2") (pintype "passive"))
      (node (ref "R39") (pin "2") (pinfunction "2_2") (pintype "passive"))
    )
    (net (code "69") (name "Net-(C46-Pad2)") (class "Default")
      (node (ref "C46") (pin "2") (pinfunction "2_2") (pintype "passive"))
      (node (ref "R43") (pin "1") (pinfunction "1_1") (pintype "passive"))
    )
    (net (code "70") (name "Net-(C47-Pad1)") (class "Default")
      (node (ref "C47") (pin "1") (pinfunction "1_1") (pintype "passive"))
      (node (ref "R40") (pin "1") (pinfunction "1_1") (pintype "passive"))
    )
    (net (code "71") (name "Net-(C48-Pad1)") (class "Default")
      (node (ref "C48") (pin "1") (pinfunction "1_1") (pintype "passive"))
      (node (ref "R46") (pin "2") (pinfunction "2_2") (pintype "passive"))
      (node (ref "R47") (pin "1") (pinfunction "1_1") (pintype "passive"))
    )
    (net (code "72") (name "Net-(C49-Pad2)") (class "Default")
      (node (ref "C49") (pin "2") (pinfunction "2_2") (pintype "passive"))
      (node (ref "R50") (pin "1") (pinfunction "1_1") (pintype "passive"))
    )
    (net (code "73") (name "Net-(C50-Pad1)") (class "Default")
      (node (ref "C50") (pin "1") (pinfunction "1_1") (pintype "passive"))
      (node (ref "R55") (pin "2") (pinfunction "2_2") (pintype "passive"))
      (node (ref "R56") (pin "1") (pinfunction "1_1") (pintype "passive"))
    )
    (net (code "74") (name "Net-(C51-Pad1)") (class "Default")
      (node (ref "C51") (pin "1") (pinfunction "1_1") (pintype "passive"))
      (node (ref "R52") (pin "1") (pinfunction "1_1") (pintype "passive"))
      (node (ref "R53") (pin "2") (pinfunction "2_2") (pintype "passive"))
    )
    (net (code "75") (name "Net-(C52-Pad2)") (class "Default")
      (node (ref "C52") (pin "2") (pinfunction "2_2") (pintype "passive"))
      (node (ref "R59") (pin "1") (pinfunction "1_1") (pintype "passive"))
    )
    (net (code "76") (name "Net-(C58-Pad2)") (class "Default")
      (node (ref "C58") (pin "2") (pinfunction "2_2") (pintype "passive"))
      (node (ref "R62") (pin "1") (pinfunction "1_1") (pintype "passive"))
    )
    (net (code "77") (name "Net-(C61-Pad1)") (class "Default")
      (node (ref "C61") (pin "1") (pinfunction "1_1") (pintype "passive"))
      (node (ref "R63") (pin "1") (pinfunction "1_1") (pintype "passive"))
      (node (ref "R64") (pin "2") (pinfunction "2_2") (pintype "passive"))
    )
    (net (code "78") (name "Net-(C66-Pad1)") (class "Default")
      (node (ref "C66") (pin "1") (pinfunction "1_1") (pintype "passive"))
      (node (ref "R72") (pin "1") (pinfunction "1_1") (pintype "passive"))
    )
    (net (code "79") (name "Net-(C68-Pad2)") (class "Default")
      (node (ref "C68") (pin "2") (pinfunction "2_2") (pintype "passive"))
      (node (ref "R76") (pin "1") (pinfunction "1_1") (pintype "passive"))
    )
    (net (code "80") (name "Net-(C69-Pad2)") (class "Default")
      (node (ref "C69") (pin "2") (pinfunction "2_2") (pintype "passive"))
      (node (ref "Q17") (pin "B") (pinfunction "B_B") (pintype "passive"))
      (node (ref "R77") (pin "1") (pinfunction "1_1") (pintype "passive"))
      (node (ref "R80") (pin "2") (pinfunction "2_2") (pintype "passive"))
      (node (ref "R82") (pin "2") (pinfunction "2_2") (pintype "passive"))
    )
    (net (code "81") (name "Net-(C70-Pad1)") (class "Default")
      (node (ref "C70") (pin "1") (pinfunction "1_1") (pintype "passive"))
      (node (ref "Q16") (pin "B") (pinfunction "B_B") (pintype "passive"))
      (node (ref "R78") (pin "2") (pinfunction "2_2") (pintype "passive"))
      (node (ref "R79") (pin "2") (pinfunction "2_2") (pintype "passive"))
    )
    (net (code "82") (name "Net-(C70-Pad2)") (class "Default")
      (node (ref "C70") (pin "2") (pinfunction "2_2") (pintype "passive"))
      (node (ref "Q17") (pin "C") (pinfunction "C_C") (pintype "passive"))
      (node (ref "R79") (pin "1") (pinfunction "1_1") (pintype "passive"))
      (node (ref "R84") (pin "2") (pinfunction "2_2") (pintype "passive"))
    )
    (net (code "83") (name "Net-(C71-Pad2)") (class "Default")
      (node (ref "C71") (pin "2") (pinfunction "2_2") (pintype "passive"))
      (node (ref "R83") (pin "2") (pinfunction "2_2") (pintype "passive"))
    )
    (net (code "84") (name "Net-(C75-Pad1)") (class "Default")
      (node (ref "C75") (pin "1") (pinfunction "1_1") (pintype "passive"))
      (node (ref "Q18") (pin "B") (pinfunction "B_B") (pintype "passive"))
      (node (ref "R86") (pin "1") (pinfunction "1_1") (pintype "passive"))
      (node (ref "R88") (pin "2") (pinfunction "2_2") (pintype "passive"))
    )
    (net (code "85") (name "Net-(D3-PadC)") (class "Default")
      (node (ref "D3") (pin "C") (pinfunction "C_C") (pintype "passive"))
      (node (ref "Q3") (pin "E") (pinfunction "E_E") (pintype "passive"))
      (node (ref "R7") (pin "2") (pinfunction "2_2") (pintype "passive"))
    )
    (net (code "86") (name "Net-(D4-PadC)") (class "Default")
      (node (ref "D4") (pin "C") (pinfunction "C_C") (pintype "passive"))
      (node (ref "TR1") (pin "2") (pinfunction "2_2") (pintype "passive"))
    )
    (net (code "87") (name "Net-(D9-PadC)") (class "Default")
      (node (ref "D9") (pin "C") (pinfunction "C_C") (pintype "passive"))
      (node (ref "ZD3") (pin "C") (pinfunction "C_C") (pintype "passive"))
    )
    (net (code "88") (name "Net-(D10-PadC)") (class "Default")
      (node (ref "D10") (pin "C") (pinfunction "C_C") (pintype "passive"))
      (node (ref "Q9") (pin "2") (pinfunction "C_2") (pintype "passive"))
      (node (ref "Q9") (pin "4") (pinfunction "C_4") (pintype "passive"))
      (node (ref "ZD3") (pin "A") (pinfunction "A_A") (pintype "passive"))
    )
    (net (code "89") (name "Net-(D11-PadC)") (class "Default")
      (node (ref "D11") (pin "C") (pinfunction "C_C") (pintype "passive"))
      (node (ref "ZD2") (pin "C") (pinfunction "C_C") (pintype "passive"))
    )
    (net (code "90") (name "Net-(D21-PadA)") (class "Default")
      (node (ref "D21") (pin "A") (pinfunction "A_A") (pintype "passive"))
      (node (ref "Q22") (pin "B") (pinfunction "B_B") (pintype "passive"))
      (node (ref "R108") (pin "1") (pinfunction "1_1") (pintype "passive"))
      (node (ref "R111") (pin "2") (pinfunction "2_2") (pintype "passive"))
    )
    (net (code "91") (name "Net-(D21-PadC)") (class "Default")
      (node (ref "D21") (pin "C") (pinfunction "C_C") (pintype "passive"))
      (node (ref "D22") (pin "A") (pinfunction "A_A") (pintype "passive"))
    )
    (net (code "92") (name "Net-(FB1-1)") (class "Default")
      (node (ref "C36") (pin "1") (pinfunction "1_1") (pintype "passive"))
      (node (ref "D6") (pin "C") (pinfunction "C_C") (pintype "passive"))
      (node (ref "FB1") (pin "P$1") (pinfunction "1_P$1") (pintype "passive"))
      (node (ref "FB2") (pin "P$1") (pinfunction "1_P$1") (pintype "passive"))
      (node (ref "IC4") (pin "1") (pinfunction "VO_1") (pintype "passive"))
      (node (ref "TP2") (pin "1") (pinfunction "P$1_1") (pintype "bidirectional"))
    )
    (net (code "93") (name "Net-(FB3-1)") (class "Default")
      (node (ref "C42") (pin "2") (pinfunction "2_2") (pintype "passive"))
      (node (ref "D7") (pin "A") (pinfunction "A_A") (pintype "passive"))
      (node (ref "FB3") (pin "P$1") (pinfunction "1_P$1") (pintype "passive"))
      (node (ref "IC6") (pin "1") (pinfunction "OUT_1") (pintype "passive"))
      (node (ref "TP4") (pin "1") (pinfunction "P$1_1") (pintype "bidirectional"))
    )
    (net (code "94") (name "Net-(IC1-BST)") (class "Default")
      (node (ref "C8") (pin "1") (pinfunction "1_1") (pintype "passive"))
      (node (ref "IC1") (pin "17") (pinfunction "BST_17") (pintype "passive"))
    )
    (net (code "95") (name "Net-(IC1-COMP)") (class "Default")
      (node (ref "C19") (pin "2") (pinfunction "2_2") (pintype "passive"))
      (node (ref "C20") (pin "2") (pinfunction "2_2") (pintype "passive"))
      (node (ref "IC1") (pin "4") (pinfunction "COMP_4") (pintype "passive"))
    )
    (net (code "96") (name "Net-(IC1-ILIM)") (class "Default")
      (node (ref "C12") (pin "1") (pinfunction "1_1") (pintype "passive"))
      (node (ref "IC1") (pin "11") (pinfunction "ILIM_11") (pintype "input"))
      (node (ref "R4") (pin "1") (pinfunction "1_1") (pintype "passive"))
    )
    (net (code "97") (name "Net-(IC1-RT)") (class "Default")
      (node (ref "IC1") (pin "2") (pinfunction "RT_2") (pintype "input"))
      (node (ref "R9") (pin "2") (pinfunction "2_2") (pintype "passive"))
    )
    (net (code "98") (name "Net-(IC1-SS_TRK)") (class "Default")
      (node (ref "C21") (pin "1") (pinfunction "1_1") (pintype "passive"))
      (node (ref "IC1") (pin "3") (pinfunction "SS_TRK_3") (pintype "input"))
    )
    (net (code "99") (name "Net-(IC1-SYNCIN)") (class "Default")
      (node (ref "IC1") (pin "8") (pinfunction "SYNCIN_8") (pintype "input"))
      (node (ref "JP1") (pin "2") (pinfunction "2_2") (pintype "passive"))
    )
    (net (code "100") (name "Net-(IC2-BOOT)") (class "Default")
      (node (ref "C27") (pin "2") (pinfunction "2_2") (pintype "passive"))
      (node (ref "IC2") (pin "1") (pinfunction "BOOT_1") (pintype "output"))
    )
    (net (code "101") (name "Net-(IC2-COMP)") (class "Default")
      (node (ref "C32") (pin "2") (pinfunction "2_2") (pintype "passive"))
      (node (ref "IC2") (pin "8") (pinfunction "COMP_8") (pintype "output"))
      (node (ref "R21") (pin "2") (pinfunction "2_2") (pintype "passive"))
    )
    (net (code "102") (name "Net-(IC2-EN)") (class "Default")
      (node (ref "IC2") (pin "3") (pinfunction "EN_3") (pintype "input"))
      (node (ref "R14") (pin "1") (pinfunction "1_1") (pintype "passive"))
      (node (ref "R17") (pin "2") (pinfunction "2_2") (pintype "passive"))
    )
    (net (code "103") (name "Net-(IC2-PH)") (class "Default")
      (node (ref "C27") (pin "1") (pinfunction "1_1") (pintype "passive"))
      (node (ref "C28") (pin "1") (pinfunction "1_1") (pintype "passive"))
      (node (ref "D5") (pin "C") (pinfunction "C_C") (pintype "passive"))
      (node (ref "IC2") (pin "10") (pinfunction "PH_10") (pintype "input"))
      (node (ref "TR1") (pin "1") (pinfunction "1_1") (pintype "passive"))
    )
    (net (code "104") (name "Net-(IC2-RT{slash}CLK)") (class "Default")
      (node (ref "IC2") (pin "5") (pinfunction "RT/CLK_5") (pintype "input"))
      (node (ref "R20") (pin "2") (pinfunction "2_2") (pintype "passive"))
    )
    (net (code "105") (name "Net-(IC2-SS{slash}TR)") (class "Default")
      (node (ref "C31") (pin "1") (pinfunction "1_1") (pintype "passive"))
      (node (ref "IC2") (pin "4") (pinfunction "SS/TR_4") (pintype "input"))
    )
    (net (code "106") (name "Net-(IC2-VSENSE)") (class "Default")
      (node (ref "IC2") (pin "7") (pinfunction "VSENSE_7") (pintype "input"))
      (node (ref "R19") (pin "1") (pinfunction "1_1") (pintype "passive"))
      (node (ref "R22") (pin "2") (pinfunction "2_2") (pintype "passive"))
    )
    (net (code "107") (name "Net-(IC3-A6)") (class "Default")
      (node (ref "DIB1.1") (pin "COM") (pinfunction "COM_COM") (pintype "passive"))
      (node (ref "IC3") (pin "7") (pinfunction "A6_7") (pintype "output"))
    )
    (net (code "108") (name "Net-(IC3-B2)") (class "Default")
      (node (ref "IC3") (pin "14") (pinfunction "B2_14") (pintype "output"))
      (node (ref "RN1") (pin "1") (pinfunction "1_1") (pintype "passive"))
    )
    (net (code "109") (name "Net-(IC3-B3)") (class "Default")
      (node (ref "IC3") (pin "13") (pinfunction "B3_13") (pintype "output"))
      (node (ref "RN1") (pin "2") (pinfunction "1_2") (pintype "passive"))
    )
    (net (code "110") (name "Net-(IC3-B4)") (class "Default")
      (node (ref "IC3") (pin "12") (pinfunction "B4_12") (pintype "output"))
      (node (ref "RN1") (pin "3") (pinfunction "1_3") (pintype "passive"))
    )
    (net (code "111") (name "Net-(IC5-BYPASS)") (class "Default")
      (node (ref "C39") (pin "2") (pinfunction "2_2") (pintype "passive"))
      (node (ref "IC5") (pin "4") (pinfunction "BYPASS_4") (pintype "passive"))
    )
    (net (code "112") (name "Net-(IC7-B1)") (class "Default")
      (node (ref "IC7") (pin "14") (pinfunction "B1_14") (pintype "output"))
      (node (ref "RN1") (pin "4") (pinfunction "1_4") (pintype "passive"))
    )
    (net (code "113") (name "Net-(IC9A-+IN)") (class "Default")
      (node (ref "IC9") (pin "3") (pinfunction "+IN_3") (pintype "input"))
      (node (ref "R50") (pin "2") (pinfunction "2_2") (pintype "passive"))
      (node (ref "R52") (pin "2") (pinfunction "2_2") (pintype "passive"))
    )
    (net (code "114") (name "Net-(IC9A--IN)") (class "Default")
      (node (ref "C53") (pin "1") (pinfunction "1_1") (pintype "passive"))
      (node (ref "D13") (pin "C") (pinfunction "C_C") (pintype "passive"))
      (node (ref "IC9") (pin "2") (pinfunction "-IN_2") (pintype "input"))
      (node (ref "R61") (pin "2") (pinfunction "2_2") (pintype "passive"))
      (node (ref "R62") (pin "2") (pinfunction "2_2") (pintype "passive"))
    )
    (net (code "115") (name "Net-(IC9B-+IN)") (class "Default")
      (node (ref "IC9") (pin "5") (pinfunction "+IN_5") (pintype "input"))
      (node (ref "R42") (pin "2") (pinfunction "2_2") (pintype "passive"))
      (node (ref "R43") (pin "2") (pinfunction "2_2") (pintype "passive"))
      (node (ref "R46") (pin "1") (pinfunction "1_1") (pintype "passive"))
    )
    (net (code "116") (name "Net-(IC9B--IN)") (class "Default")
      (node (ref "IC9") (pin "6") (pinfunction "-IN_6") (pintype "input"))
      (node (ref "R54") (pin "2") (pinfunction "2_2") (pintype "passive"))
      (node (ref "R55") (pin "1") (pinfunction "1_1") (pintype "passive"))
      (node (ref "R59") (pin "2") (pinfunction "2_2") (pintype "passive"))
    )
    (net (code "117") (name "Net-(IC10A-+IN)") (class "Default")
      (node (ref "IC10") (pin "3") (pinfunction "+IN_3") (pintype "input"))
      (node (ref "R63") (pin "2") (pinfunction "2_2") (pintype "passive"))
    )
    (net (code "118") (name "Net-(IC10A--IN)") (class "Default")
      (node (ref "D16") (pin "C") (pinfunction "C_C") (pintype "passive"))
      (node (ref "IC10") (pin "2") (pinfunction "-IN_2") (pintype "input"))
      (node (ref "R68") (pin "2") (pinfunction "2_2") (pintype "passive"))
      (node (ref "R72") (pin "2") (pinfunction "2_2") (pintype "passive"))
      (node (ref "R75") (pin "2") (pinfunction "2_2") (pintype "passive"))
      (node (ref "R76") (pin "2") (pinfunction "2_2") (pintype "passive"))
    )
    (net (code "119") (name "Net-(IC10B-+IN)") (class "Default")
      (node (ref "C44") (pin "1") (pinfunction "1_1") (pintype "passive"))
      (node (ref "IC10") (pin "5") (pinfunction "+IN_5") (pintype "input"))
      (node (ref "R30") (pin "2") (pinfunction "2_2") (pintype "passive"))
      (node (ref "R34") (pin "1") (pinfunction "1_1") (pintype "passive"))
    )
    (net (code "120") (name "Net-(IC11A-+IN)") (class "Default")
      (node (ref "IC11") (pin "3") (pinfunction "+IN_3") (pintype "input"))
      (node (ref "R65") (pin "2") (pinfunction "2_2") (pintype "passive"))
      (node (ref "R66") (pin "2") (pinfunction "2_2") (pintype "passive"))
    )
    (net (code "121") (name "Net-(IC11A--IN)") (class "Default")
      (node (ref "IC11") (pin "2") (pinfunction "-IN_2") (pintype "input"))
      (node (ref "R73") (pin "1") (pinfunction "1_1") (pintype "passive"))
      (node (ref "R74") (pin "2") (pinfunction "2_2") (pintype "passive"))
    )
    (net (code "122") (name "Net-(IC12-NO)") (class "Default")
      (node (ref "IC12") (pin "1") (pinfunction "NO_1") (pintype "bidirectional"))
      (node (ref "R75") (pin "1") (pinfunction "1_1") (pintype "passive"))
    )
    (net (code "123") (name "Net-(IC13A-I1)") (class "Default")
      (node (ref "IC13") (pin "2") (pinfunction "I1_2") (pintype "input"))
      (node (ref "IC15") (pin "1") (pinfunction "OUT_1") (pintype "output"))
      (node (ref "R89") (pin "2") (pinfunction "2_2") (pintype "passive"))
    )
    (net (code "124") (name "Net-(IC13A-O)") (class "Default")
      (node (ref "D18") (pin "A") (pinfunction "A_A") (pintype "passive"))
      (node (ref "IC13") (pin "7") (pinfunction "O_7") (pintype "output"))
      (node (ref "IC14") (pin "6") (pinfunction "CTRL_6") (pintype "input"))
    )
    (net (code "125") (name "Net-(IC13B-I0)") (class "Default")
      (node (ref "IC13") (pin "5") (pinfunction "I0_5") (pintype "input"))
      (node (ref "IC15") (pin "7") (pinfunction "OUT_7") (pintype "output"))
      (node (ref "R90") (pin "2") (pinfunction "2_2") (pintype "passive"))
    )
    (net (code "126") (name "Net-(IC13B-O)") (class "Default")
      (node (ref "D19") (pin "A") (pinfunction "A_A") (pintype "passive"))
      (node (ref "IC13") (pin "3") (pinfunction "O_3") (pintype "output"))
      (node (ref "IC17") (pin "6") (pinfunction "CTRL_6") (pintype "input"))
    )
    (net (code "127") (name "Net-(IC15A--IN)") (class "Default")
      (node (ref "D20") (pin "C") (pinfunction "C_C") (pintype "passive"))
      (node (ref "IC15") (pin "2") (pinfunction "-IN_2") (pintype "input"))
      (node (ref "IC15") (pin "6") (pinfunction "-IN_6") (pintype "input"))
      (node (ref "R95") (pin "1") (pinfunction "1_1") (pintype "passive"))
      (node (ref "R96") (pin "2") (pinfunction "2_2") (pintype "passive"))
    )
    (net (code "128") (name "Net-(IC16A-+IN)") (class "Default")
      (node (ref "C80") (pin "2") (pinfunction "2_2") (pintype "passive"))
      (node (ref "IC16") (pin "3") (pinfunction "+IN_3") (pintype "input"))
      (node (ref "R93") (pin "2") (pinfunction "2_2") (pintype "passive"))
      (node (ref "R94") (pin "1") (pinfunction "1_1") (pintype "passive"))
      (node (ref "ZD5") (pin "3") (pinfunction "C_3") (pintype "passive"))
    )
    (net (code "129") (name "Net-(IC16A--IN)") (class "Default")
      (node (ref "C81") (pin "2") (pinfunction "2_2") (pintype "passive"))
      (node (ref "IC16") (pin "4") (pinfunction "-IN_4") (pintype "input"))
      (node (ref "R98") (pin "1") (pinfunction "1_1") (pintype "passive"))
      (node (ref "R99") (pin "2") (pinfunction "2_2") (pintype "passive"))
      (node (ref "ZD5") (pin "1") (pinfunction "A_1") (pintype "passive"))
      (node (ref "ZD5") (pin "2") (pinfunction "A_2") (pintype "passive"))
    )
    (net (code "130") (name "Net-(IC16A-OUT)") (class "Default")
      (node (ref "C81") (pin "1") (pinfunction "1_1") (pintype "passive"))
      (node (ref "IC16") (pin "1") (pinfunction "OUT_1") (pintype "output"))
      (node (ref "R95") (pin "2") (pinfunction "2_2") (pintype "passive"))
      (node (ref "R99") (pin "1") (pinfunction "1_1") (pintype "passive"))
    )
    (net (code "131") (name "Net-(IC18A-+IN)") (class "Default")
      (node (ref "IC18") (pin "3") (pinfunction "+IN_3") (pintype "input"))
      (node (ref "IC18") (pin "5") (pinfunction "+IN_5") (pintype "input"))
      (node (ref "R109") (pin "1") (pinfunction "1_1") (pintype "passive"))
    )
    (net (code "132") (name "Net-(IC18A--IN)") (class "Default")
      (node (ref "IC18") (pin "2") (pinfunction "-IN_2") (pintype "input"))
      (node (ref "R102") (pin "2") (pinfunction "2_2") (pintype "passive"))
    )
    (net (code "133") (name "Net-(IC18A-OUT)") (class "Default")
      (node (ref "IC18") (pin "1") (pinfunction "OUT_1") (pintype "output"))
      (node (ref "R103") (pin "1") (pinfunction "1_1") (pintype "passive"))
    )
    (net (code "134") (name "Net-(IC18B--IN)") (class "Default")
      (node (ref "IC18") (pin "6") (pinfunction "-IN_6") (pintype "input"))
      (node (ref "R114") (pin "2") (pinfunction "2_2") (pintype "passive"))
    )
    (net (code "135") (name "Net-(IC18B-OUT)") (class "Default")
      (node (ref "IC18") (pin "7") (pinfunction "OUT_7") (pintype "output"))
      (node (ref "R115") (pin "1") (pinfunction "1_1") (pintype "passive"))
    )
    (net (code "136") (name "Net-(IC19-+IN)") (class "Default")
      (node (ref "C84") (pin "1") (pinfunction "1_1") (pintype "passive"))
      (node (ref "IC19") (pin "2") (pinfunction "+IN_2") (pintype "input"))
      (node (ref "R104") (pin "2") (pinfunction "2_2") (pintype "passive"))
      (node (ref "R107") (pin "1") (pinfunction "1_1") (pintype "passive"))
    )
    (net (code "137") (name "Net-(IC19--IN)") (class "Default")
      (node (ref "C84") (pin "2") (pinfunction "2_2") (pintype "passive"))
      (node (ref "IC19") (pin "3") (pinfunction "-IN_3") (pintype "input"))
      (node (ref "R110") (pin "2") (pinfunction "2_2") (pintype "passive"))
    )
    (net (code "138") (name "Net-(IC19-OUT)") (class "Default")
      (node (ref "IC19") (pin "7") (pinfunction "OUT_7") (pintype "output"))
      (node (ref "Q25") (pin "1") (pinfunction "G_1") (pintype "passive"))
      (node (ref "R108") (pin "2") (pinfunction "2_2") (pintype "passive"))
      (node (ref "R116") (pin "2") (pinfunction "2_2") (pintype "passive"))
    )
    (net (code "139") (name "Net-(IC19-~{SHDN})") (class "Default")
      (node (ref "IC19") (pin "6") (pinfunction "~{SHDN}_6") (pintype "input"))
      (node (ref "JP4") (pin "2") (pinfunction "2_2") (pintype "passive"))
    )
    (net (code "140") (name "Net-(IC20-VOUTA)") (class "Default")
      (node (ref "IC20") (pin "4") (pinfunction "VOUTA_4") (pintype "output"))
      (node (ref "ISET") (pin "1") (pinfunction "1_1") (pintype "passive"))
    )
    (net (code "141") (name "Net-(IC20-VOUTB)") (class "Default")
      (node (ref "IC20") (pin "3") (pinfunction "VOUTB_3") (pintype "output"))
      (node (ref "USET") (pin "1") (pinfunction "1_1") (pintype "passive"))
    )
    (net (code "142") (name "Net-(IC21-TRIM{slash}NR)") (class "Default")
      (node (ref "C92") (pin "1") (pinfunction "1_1") (pintype "passive"))
      (node (ref "IC21") (pin "5") (pinfunction "TRIM/NR_5") (pintype "input"))
    )
    (net (code "143") (name "Net-(IC23A-~{CLR})") (class "Default")
      (node (ref "D23") (pin "A") (pinfunction "A_A") (pintype "passive"))
      (node (ref "D24") (pin "A") (pinfunction "A_A") (pintype "passive"))
      (node (ref "IC23") (pin "6") (pinfunction "~{CLR}_6") (pintype "input"))
      (node (ref "R124") (pin "2") (pinfunction "2_2") (pintype "passive"))
    )
    (net (code "144") (name "Net-(JP2-Pad1)") (class "Default")
      (node (ref "JP2") (pin "1") (pinfunction "1_1") (pintype "passive"))
      (node (ref "X6") (pin "1") (pinfunction "1_1") (pintype "passive"))
    )
    (net (code "145") (name "Net-(JP2-Pad2)") (class "Default")
      (node (ref "JP2") (pin "2") (pinfunction "2_2") (pintype "passive"))
      (node (ref "R94") (pin "2") (pinfunction "2_2") (pintype "passive"))
    )
    (net (code "146") (name "Net-(JP3-Pad2)") (class "Default")
      (node (ref "JP3") (pin "2") (pinfunction "2_2") (pintype "passive"))
      (node (ref "R98") (pin "2") (pinfunction "2_2") (pintype "passive"))
    )
    (net (code "147") (name "Net-(K1A-NO)") (class "Default")
      (node (ref "K1") (pin "5") (pinfunction "NO_5") (pintype "passive"))
      (node (ref "X6") (pin "4") (pinfunction "1_4") (pintype "passive"))
    )
    (net (code "148") (name "Net-(K1B-NO)") (class "Default")
      (node (ref "K1") (pin "8") (pinfunction "NO_8") (pintype "passive"))
      (node (ref "X6") (pin "5") (pinfunction "1_5") (pintype "passive"))
    )
    (net (code "149") (name "Net-(K1C-C2)") (class "Default")
      (node (ref "D17") (pin "A") (pinfunction "A_A") (pintype "passive"))
      (node (ref "K1") (pin "12") (pinfunction "C2_12") (pintype "passive"))
      (node (ref "Q20") (pin "3") (pinfunction "D_3") (pintype "passive"))
      (node (ref "R91") (pin "1") (pinfunction "1_1") (pintype "passive"))
    )
    (net (code "150") (name "Net-(LED1A-A)") (class "Default")
      (node (ref "D18") (pin "C") (pinfunction "C_C") (pintype "passive"))
      (node (ref "D19") (pin "C") (pinfunction "C_C") (pintype "passive"))
      (node (ref "LED1") (pin "BA") (pinfunction "A_BA") (pintype "passive"))
    )
    (net (code "151") (name "Net-(LED1A-C)") (class "Default")
      (node (ref "LED1") (pin "BC") (pinfunction "C_BC") (pintype "passive"))
      (node (ref "R92") (pin "2") (pinfunction "2_2") (pintype "passive"))
    )
    (net (code "152") (name "Net-(LED1B-C)") (class "Default")
      (node (ref "LED1") (pin "TC") (pinfunction "C_TC") (pintype "passive"))
      (node (ref "R91") (pin "2") (pinfunction "2_2") (pintype "passive"))
    )
    (net (code "153") (name "Net-(LED2A-C)") (class "Default")
      (node (ref "LED2") (pin "BC") (pinfunction "C_BC") (pintype "passive"))
      (node (ref "R121") (pin "2") (pinfunction "2_2") (pintype "passive"))
    )
    (net (code "154") (name "Net-(LED2B-C)") (class "Default")
      (node (ref "LED2") (pin "TC") (pinfunction "C_TC") (pintype "passive"))
      (node (ref "R120") (pin "1") (pinfunction "1_1") (pintype "passive"))
    )
    (net (code "155") (name "Net-(LED3-AG)") (class "Default")
      (node (ref "LED3") (pin "GREEN") (pinfunction "AG_GREEN") (pintype "passive"))
      (node (ref "Q29") (pin "3") (pinfunction "D_3") (pintype "passive"))
    )
    (net (code "156") (name "Net-(LED3-AR)") (class "Default")
      (node (ref "LED3") (pin "RED") (pinfunction "AR_RED") (pintype "passive"))
      (node (ref "Q30") (pin "3") (pinfunction "D_3") (pintype "passive"))
    )
    (net (code "157") (name "Net-(LED3-C)") (class "Default")
      (node (ref "LED3") (pin "CC") (pinfunction "C_CC") (pintype "passive"))
      (node (ref "R128") (pin "1") (pinfunction "1_1") (pintype "passive"))
    )
    (net (code "158") (name "Net-(OK1-A)") (class "Default")
      (node (ref "OK1") (pin "1") (pinfunction "A_1") (pintype "passive"))
      (node (ref "Q4") (pin "2") (pinfunction "S_2") (pintype "passive"))
    )
    (net (code "159") (name "Net-(OK1-C)") (class "Default")
      (node (ref "OK1") (pin "2") (pinfunction "C_2") (pintype "passive"))
      (node (ref "R27") (pin "2") (pinfunction "2_2") (pintype "passive"))
    )
    (net (code "160") (name "Net-(Q5-G)") (class "Default")
      (node (ref "D8") (pin "C") (pinfunction "C_C") (pintype "passive"))
      (node (ref "D9") (pin "A") (pinfunction "A_A") (pintype "passive"))
      (node (ref "Q5") (pin "1") (pinfunction "G_1") (pintype "passive"))
      (node (ref "R31") (pin "1") (pinfunction "1_1") (pintype "passive"))
    )
    (net (code "161") (name "Net-(Q6-PadB)") (class "Default")
      (node (ref "Q6") (pin "B") (pinfunction "B_B") (pintype "passive"))
      (node (ref "R32") (pin "2") (pinfunction "2_2") (pintype "passive"))
    )
    (net (code "162") (name "Net-(Q7-B)") (class "Default")
      (node (ref "D11") (pin "A") (pinfunction "A_A") (pintype "passive"))
      (node (ref "Q7") (pin "1") (pinfunction "B_1") (pintype "passive"))
      (node (ref "R40") (pin "2") (pinfunction "2_2") (pintype "passive"))
      (node (ref "R45") (pin "1") (pinfunction "1_1") (pintype "passive"))
    )
    (net (code "163") (name "Net-(Q7-E)") (class "Default")
      (node (ref "D8") (pin "A") (pinfunction "A_A") (pintype "passive"))
      (node (ref "Q7") (pin "3") (pinfunction "E_3") (pintype "passive"))
    )
    (net (code "164") (name "Net-(Q8-G)") (class "Default")
      (node (ref "D10") (pin "A") (pinfunction "A_A") (pintype "passive"))
      (node (ref "Q6") (pin "C") (pinfunction "C_C") (pintype "passive"))
      (node (ref "Q8") (pin "1") (pinfunction "G_1") (pintype "passive"))
      (node (ref "R33") (pin "2") (pinfunction "2_2") (pintype "passive"))
    )
    (net (code "165") (name "Net-(Q8-S)") (class "Default")
      (node (ref "Q8") (pin "3") (pinfunction "S_3") (pintype "passive"))
      (node (ref "R29") (pin "1") (pinfunction "1_1") (pintype "passive"))
      (node (ref "R32") (pin "1") (pinfunction "1_1") (pintype "passive"))
      (node (ref "R33") (pin "1") (pinfunction "1_1") (pintype "passive"))
    )
    (net (code "166") (name "Net-(Q9-E)") (class "Default")
      (node (ref "Q9") (pin "3") (pinfunction "E_3") (pintype "passive"))
      (node (ref "R44") (pin "1") (pinfunction "1_1") (pintype "passive"))
    )
    (net (code "167") (name "Net-(Q10-PadB)") (class "Default")
      (node (ref "Q10") (pin "B") (pinfunction "B_B") (pintype "passive"))
      (node (ref "Q10") (pin "C") (pinfunction "C_C") (pintype "passive"))
      (node (ref "Q11") (pin "B") (pinfunction "B_B") (pintype "passive"))
      (node (ref "Q13") (pin "C") (pinfunction "C_C") (pintype "passive"))
    )
    (net (code "168") (name "Net-(Q10-PadE)") (class "Default")
      (node (ref "Q10") (pin "E") (pinfunction "E_E") (pintype "passive"))
      (node (ref "R38") (pin "1") (pinfunction "1_1") (pintype "passive"))
    )
    (net (code "169") (name "Net-(Q11-PadE)") (class "Default")
      (node (ref "Q11") (pin "E") (pinfunction "E_E") (pintype "passive"))
      (node (ref "R39") (pin "1") (pinfunction "1_1") (pintype "passive"))
    )
    (net (code "170") (name "Net-(Q12-PadB)") (class "Default")
      (node (ref "Q12") (pin "B") (pinfunction "B_B") (pintype "passive"))
      (node (ref "R37") (pin "1") (pinfunction "1_1") (pintype "passive"))
      (node (ref "R48") (pin "2") (pinfunction "2_2") (pintype "passive"))
      (node (ref "R49") (pin "2") (pinfunction "2_2") (pintype "passive"))
    )
    (net (code "171") (name "Net-(Q12-PadE)") (class "Default")
      (node (ref "Q12") (pin "E") (pinfunction "E_E") (pintype "passive"))
      (node (ref "R57") (pin "2") (pinfunction "2_2") (pintype "passive"))
    )
    (net (code "172") (name "Net-(Q13-PadE)") (class "Default")
      (node (ref "Q13") (pin "E") (pinfunction "E_E") (pintype "passive"))
      (node (ref "R58") (pin "2") (pinfunction "2_2") (pintype "passive"))
    )
    (net (code "173") (name "Net-(Q14-S-Pad1)") (class "Default")
      (node (ref "Q14") (pin "1") (pinfunction "S_1") (pintype "passive"))
      (node (ref "Q14") (pin "2") (pinfunction "S_2") (pintype "passive"))
      (node (ref "Q14") (pin "3") (pinfunction "S_3") (pintype "passive"))
      (node (ref "R66") (pin "1") (pinfunction "1_1") (pintype "passive"))
      (node (ref "R67") (pin "2") (pinfunction "2_2") (pintype "passive"))
    )
    (net (code "174") (name "Net-(Q15-S-Pad1)") (class "Default")
      (node (ref "Q15") (pin "1") (pinfunction "S_1") (pintype "passive"))
      (node (ref "Q15") (pin "2") (pinfunction "S_2") (pintype "passive"))
      (node (ref "Q15") (pin "3") (pinfunction "S_3") (pintype "passive"))
      (node (ref "R69") (pin "2") (pinfunction "2_2") (pintype "passive"))
    )
    (net (code "175") (name "Net-(Q18-PadC)") (class "Default")
      (node (ref "Q18") (pin "C") (pinfunction "C_C") (pintype "passive"))
      (node (ref "R81") (pin "1") (pinfunction "1_1") (pintype "passive"))
    )
    (net (code "176") (name "Net-(Q19-PadB)") (class "Default")
      (node (ref "Q19") (pin "B") (pinfunction "B_B") (pintype "passive"))
      (node (ref "R84") (pin "1") (pinfunction "1_1") (pintype "passive"))
      (node (ref "R87") (pin "2") (pinfunction "2_2") (pintype "passive"))
    )
    (net (code "177") (name "Net-(Q21-G)") (class "Default")
      (node (ref "Q21") (pin "3") (pinfunction "G_3") (pintype "passive"))
      (node (ref "Q22") (pin "C") (pinfunction "C_C") (pintype "passive"))
      (node (ref "R105") (pin "1") (pinfunction "1_1") (pintype "passive"))
      (node (ref "R106") (pin "1") (pinfunction "1_1") (pintype "passive"))
    )
    (net (code "178") (name "Net-(Q22-PadE)") (class "Default")
      (node (ref "Q22") (pin "E") (pinfunction "E_E") (pintype "passive"))
      (node (ref "R112") (pin "2") (pinfunction "2_2") (pintype "passive"))
    )
    (net (code "179") (name "Net-(Q23-G)") (class "Default")
      (node (ref "Q23") (pin "4") (pinfunction "G_4") (pintype "passive"))
      (node (ref "Q24") (pin "C") (pinfunction "C_C") (pintype "passive"))
      (node (ref "R116") (pin "1") (pinfunction "1_1") (pintype "passive"))
    )
    (net (code "180") (name "Net-(Q24-PadB)") (class "Default")
      (node (ref "Q24") (pin "B") (pinfunction "B_B") (pintype "passive"))
      (node (ref "R118") (pin "1") (pinfunction "1_1") (pintype "passive"))
      (node (ref "R119") (pin "2") (pinfunction "2_2") (pintype "passive"))
    )
    (net (code "181") (name "Net-(Q26-D)") (class "Default")
      (node (ref "Q26") (pin "3") (pinfunction "D_3") (pintype "passive"))
      (node (ref "R120") (pin "2") (pinfunction "2_2") (pintype "passive"))
    )
    (net (code "182") (name "Net-(Q27-D)") (class "Default")
      (node (ref "Q27") (pin "3") (pinfunction "D_3") (pintype "passive"))
      (node (ref "R121") (pin "1") (pinfunction "1_1") (pintype "passive"))
    )
    (net (code "183") (name "Net-(Q28-D)") (class "Default")
      (node (ref "Q28") (pin "3") (pinfunction "D_3") (pintype "passive"))
      (node (ref "R125") (pin "2") (pinfunction "2_2") (pintype "passive"))
    )
    (net (code "184") (name "Net-(R10-Pad2)") (class "Default")
      (node (ref "R10") (pin "2") (pinfunction "2_2") (pintype "passive"))
      (node (ref "R11") (pin "1") (pinfunction "1_1") (pintype "passive"))
    )
    (net (code "185") (name "Net-(R67-Pad1)") (class "Default")
      (node (ref "R67") (pin "1") (pinfunction "1_1") (pintype "passive"))
      (node (ref "R69") (pin "2S") (pinfunction "2S_2S") (pintype "passive"))
    )
    (net (code "186") (name "Net-(R69-Pad1S)") (class "Default")
      (node (ref "R69") (pin "1S") (pinfunction "1S_1S") (pintype "passive"))
      (node (ref "R74") (pin "1") (pinfunction "1_1") (pintype "passive"))
    )
    (net (code "187") (name "Net-(R81-Pad2)") (class "Default")
      (node (ref "R81") (pin "2") (pinfunction "2_2") (pintype "passive"))
      (node (ref "R82") (pin "1") (pinfunction "1_1") (pintype "passive"))
    )
    (net (code "188") (name "Net-(R118-Pad2)") (class "Default")
      (node (ref "R118") (pin "2") (pinfunction "2_2") (pintype "passive"))
      (node (ref "ZD6") (pin "A") (pinfunction "A_A") (pintype "passive"))
    )
    (net (code "189") (name "Net-(RN2A-2)") (class "Default")
      (node (ref "RN2") (pin "8") (pinfunction "2_8") (pintype "passive"))
      (node (ref "X7") (pin "6") (pinfunction "1_6") (pintype "passive"))
    )
    (net (code "190") (name "Net-(RN2C-2)") (class "Default")
      (node (ref "RN2") (pin "6") (pinfunction "2_6") (pintype "passive"))
      (node (ref "X7") (pin "5") (pinfunction "1_5") (pintype "passive"))
    )
    (net (code "191") (name "Net-(X5B-1)") (class "Default")
      (node (ref "F1") (pin "2") (pinfunction "2_2") (pintype "passive"))
      (node (ref "X5") (pin "10") (pinfunction "1_10") (pintype "passive"))
      (node (ref "X5") (pin "6") (pinfunction "1_6") (pintype "passive"))
      (node (ref "X5") (pin "7") (pinfunction "1_7") (pintype "passive"))
      (node (ref "X5") (pin "8") (pinfunction "1_8") (pintype "passive"))
      (node (ref "X5") (pin "9") (pinfunction "1_9") (pintype "passive"))
    )
    (net (code "192") (name "Net-(X6B-1)") (class "Default")
      (node (ref "JP3") (pin "1") (pinfunction "1_1") (pintype "passive"))
      (node (ref "X6") (pin "2") (pinfunction "1_2") (pintype "passive"))
    )
    (net (code "193") (name "OE_LED_GREEN") (class "Default")
      (node (ref "IC22") (pin "41") (pinfunction "PB5_41") (pintype "bidirectional"))
      (node (ref "Q29") (pin "1") (pinfunction "G_1") (pintype "passive"))
    )
    (net (code "194") (name "OE_LED_RED") (class "Default")
      (node (ref "IC22") (pin "42") (pinfunction "PB6_42") (pintype "bidirectional"))
      (node (ref "Q30") (pin "1") (pinfunction "G_1") (pintype "passive"))
    )
    (net (code "195") (name "OE_SYNC") (class "Default")
      (node (ref "IC22") (pin "36") (pinfunction "PF7_36") (pintype "bidirectional"))
      (node (ref "IC23") (pin "1") (pinfunction "CLK_1") (pintype "input"))
      (node (ref "RN1") (pin "8") (pinfunction "2_8") (pintype "passive"))
    )
    (net (code "196") (name "OE_TRIG") (class "Default")
      (node (ref "IC22") (pin "15") (pinfunction "PA5_15") (pintype "bidirectional"))
      (node (ref "OE") (pin "1") (pinfunction "1_1") (pintype "passive"))
    )
    (net (code "197") (name "OUTC+") (class "Default")
      (node (ref "C73") (pin "1") (pinfunction "1_1") (pintype "passive"))
      (node (ref "J2") (pin "1") (pinfunction "1_1") (pintype "passive"))
      (node (ref "X5") (pin "1") (pinfunction "1_1") (pintype "passive"))
      (node (ref "X5") (pin "2") (pinfunction "1_2") (pintype "passive"))
      (node (ref "X5") (pin "3") (pinfunction "1_3") (pintype "passive"))
      (node (ref "X5") (pin "4") (pinfunction "1_4") (pintype "passive"))
      (node (ref "X5") (pin "5") (pinfunction "1_5") (pintype "passive"))
    )
    (net (code "198") (name "OUTC-") (class "Default")
      (node (ref "C74") (pin "2") (pinfunction "2_2") (pintype "passive"))
      (node (ref "J3") (pin "1") (pinfunction "1_1") (pintype "passive"))
      (node (ref "X5") (pin "16") (pinfunction "1_16") (pintype "passive"))
      (node (ref "X5") (pin "17") (pinfunction "1_17") (pintype "passive"))
      (node (ref "X5") (pin "18") (pinfunction "1_18") (pintype "passive"))
      (node (ref "X5") (pin "19") (pinfunction "1_19") (pintype "passive"))
      (node (ref "X5") (pin "20") (pinfunction "1_20") (pintype "passive"))
    )
    (net (code "199") (name "OVP_EN") (class "Default")
      (node (ref "IC22") (pin "38") (pinfunction "PA15_38") (pintype "bidirectional"))
      (node (ref "JP4") (pin "1") (pinfunction "1_1") (pintype "passive"))
      (node (ref "R100") (pin "2") (pinfunction "2_2") (pintype "passive"))
    )
    (net (code "200") (name "OVP_SET") (class "Default")
      (node (ref "IC22") (pin "16") (pinfunction "PA6_16") (pintype "bidirectional"))
      (node (ref "R110") (pin "1") (pinfunction "1_1") (pintype "passive"))
    )
    (net (code "201") (name "PE") (class "Default")
      (node (ref "C2") (pin "2") (pinfunction "2_2") (pintype "passive"))
      (node (ref "C3") (pin "1") (pinfunction "1_1") (pintype "passive"))
      (node (ref "C73") (pin "2") (pinfunction "2_2") (pintype "passive"))
      (node (ref "C74") (pin "1") (pinfunction "1_1") (pintype "passive"))
      (node (ref "J1") (pin "1") (pinfunction "P$1_1") (pintype "bidirectional"))
      (node (ref "J1") (pin "2") (pinfunction "P$1_2") (pintype "bidirectional"))
      (node (ref "X6") (pin "3") (pinfunction "1_3") (pintype "passive"))
    )
    (net (code "202") (name "POST_OE") (class "Default")
      (node (ref "IC23") (pin "5") (pinfunction "Q_5") (pintype "output"))
      (node (ref "R58") (pin "1") (pinfunction "1_1") (pintype "passive"))
    )
    (net (code "203") (name "POST_OUT+") (class "Default")
      (node (ref "C48") (pin "2") (pinfunction "2_2") (pintype "passive"))
      (node (ref "C58") (pin "1") (pinfunction "1_1") (pintype "passive"))
      (node (ref "C68") (pin "1") (pinfunction "1_1") (pintype "passive"))
      (node (ref "C69") (pin "1") (pinfunction "1_1") (pintype "passive"))
      (node (ref "C71") (pin "1") (pinfunction "1_1") (pintype "passive"))
      (node (ref "C72") (pin "+") (pinfunction "+_+") (pintype "passive"))
      (node (ref "F1") (pin "1") (pinfunction "1_1") (pintype "passive"))
      (node (ref "K1") (pin "3") (pinfunction "NC_3") (pintype "passive"))
      (node (ref "Q17") (pin "E") (pinfunction "E_E") (pintype "passive"))
      (node (ref "Q21") (pin "1") (pinfunction "A1_1") (pintype "passive"))
      (node (ref "Q23") (pin "MB") (pinfunction "D_MB") (pintype "passive"))
      (node (ref "Q5") (pin "3") (pinfunction "S_3") (pintype "passive"))
      (node (ref "Q6") (pin "E") (pinfunction "E_E") (pintype "passive"))
      (node (ref "R105") (pin "2") (pinfunction "2_2") (pintype "passive"))
      (node (ref "R106") (pin "2") (pinfunction "2_2") (pintype "passive"))
      (node (ref "R11") (pin "2") (pinfunction "2_2") (pintype "passive"))
      (node (ref "R29") (pin "2") (pinfunction "2_2") (pintype "passive"))
      (node (ref "R31") (pin "2") (pinfunction "2_2") (pintype "passive"))
      (node (ref "R35") (pin "1") (pinfunction "1_1") (pintype "passive"))
      (node (ref "R37") (pin "2") (pinfunction "2_2") (pintype "passive"))
      (node (ref "R77") (pin "2") (pinfunction "2_2") (pintype "passive"))
      (node (ref "X3") (pin "6") (pinfunction "1_6") (pintype "passive"))
      (node (ref "ZD2") (pin "A") (pinfunction "A_A") (pintype "passive"))
      (node (ref "ZD4") (pin "C") (pinfunction "C_C") (pintype "passive"))
      (node (ref "ZD6") (pin "C") (pinfunction "C_C") (pintype "passive"))
    )
    (net (code "204") (name "POST_OUT-") (class "Default")
      (node (ref "C49") (pin "1") (pinfunction "1_1") (pintype "passive"))
      (node (ref "C50") (pin "2") (pinfunction "2_2") (pintype "passive"))
      (node (ref "C72") (pin "-") (pinfunction "-_-") (pintype "passive"))
      (node (ref "C75") (pin "2") (pinfunction "2_2") (pintype "passive"))
      (node (ref "D15") (pin "A") (pinfunction "A_A") (pintype "passive"))
      (node (ref "K1") (pin "10") (pinfunction "NC_10") (pintype "passive"))
      (node (ref "Q14") (pin "MB") (pinfunction "D_MB") (pintype "passive"))
      (node (ref "Q15") (pin "MB") (pinfunction "D_MB") (pintype "passive"))
      (node (ref "Q18") (pin "E") (pinfunction "E_E") (pintype "passive"))
      (node (ref "Q21") (pin "2") (pinfunction "A2_2") (pintype "passive"))
      (node (ref "Q23") (pin "1") (pinfunction "S_1") (pintype "passive"))
      (node (ref "Q23") (pin "2") (pinfunction "S_2") (pintype "passive"))
      (node (ref "Q23") (pin "3") (pinfunction "S_3") (pintype "passive"))
      (node (ref "R60") (pin "2") (pinfunction "2_2") (pintype "passive"))
      (node (ref "R83") (pin "1") (pinfunction "1_1") (pintype "passive"))
      (node (ref "R88") (pin "1") (pinfunction "1_1") (pintype "passive"))
      (node (ref "X5") (pin "11") (pinfunction "1_11") (pintype "passive"))
      (node (ref "X5") (pin "12") (pinfunction "1_12") (pintype "passive"))
      (node (ref "X5") (pin "13") (pinfunction "1_13") (pintype "passive"))
      (node (ref "X5") (pin "14") (pinfunction "1_14") (pintype "passive"))
      (node (ref "X5") (pin "15") (pinfunction "1_15") (pintype "passive"))
      (node (ref "ZD4") (pin "A") (pinfunction "A_A") (pintype "passive"))
    )
    (net (code "205") (name "PREG_OUT+") (class "Default")
      (node (ref "C16") (pin "+") (pinfunction "+_+") (pintype "passive"))
      (node (ref "C18") (pin "2") (pinfunction "2_2") (pintype "passive"))
      (node (ref "L3") (pin "2") (pinfunction "2_2") (pintype "passive"))
      (node (ref "Q5") (pin "2") (pinfunction "D_2") (pintype "passive"))
      (node (ref "R2") (pin "1") (pinfunction "1_1") (pintype "passive"))
      (node (ref "TP1") (pin "1") (pinfunction "P$1_1") (pintype "bidirectional"))
      (node (ref "X3") (pin "1") (pinfunction "1_1") (pintype "passive"))
      (node (ref "X3") (pin "2") (pinfunction "1_2") (pintype "passive"))
      (node (ref "X3") (pin "3") (pinfunction "1_3") (pintype "passive"))
      (node (ref "X3") (pin "4") (pinfunction "1_4") (pintype "passive"))
    )
    (net (code "206") (name "PREG_OUT-") (class "Default")
      (node (ref "C10") (pin "1") (pinfunction "1_1") (pintype "passive"))
      (node (ref "C12") (pin "2") (pinfunction "2_2") (pintype "passive"))
      (node (ref "C13") (pin "2") (pinfunction "2_2") (pintype "passive"))
      (node (ref "C14") (pin "2") (pinfunction "2_2") (pintype "passive"))
      (node (ref "C15") (pin "-") (pinfunction "-_-") (pintype "passive"))
      (node (ref "C16") (pin "-") (pinfunction "-_-") (pintype "passive"))
      (node (ref "C17") (pin "2") (pinfunction "2_2") (pintype "passive"))
      (node (ref "C18") (pin "1") (pinfunction "1_1") (pintype "passive"))
      (node (ref "C2") (pin "1") (pinfunction "1_1") (pintype "passive"))
      (node (ref "C4") (pin "-") (pinfunction "-_-") (pintype "passive"))
      (node (ref "C5") (pin "2") (pinfunction "2_2") (pintype "passive"))
      (node (ref "C6") (pin "2") (pinfunction "2_2") (pintype "passive"))
      (node (ref "C7") (pin "2") (pinfunction "2_2") (pintype "passive"))
      (node (ref "C7A") (pin "1") (pinfunction "1_1") (pintype "passive"))
      (node (ref "C9") (pin "1") (pinfunction "1_1") (pintype "passive"))
      (node (ref "D15") (pin "C") (pinfunction "C_C") (pintype "passive"))
      (node (ref "IC1") (pin "12") (pinfunction "PGND_12") (pintype "power_in"))
      (node (ref "IC1") (pin "15") (pinfunction "EP_15") (pintype "power_in"))
      (node (ref "IC1") (pin "21") (pinfunction "EP_21") (pintype "power_in"))
      (node (ref "L1") (pin "4") (pinfunction "2_4") (pintype "passive"))
      (node (ref "Q2") (pin "1") (pinfunction "S_1") (pintype "passive"))
      (node (ref "Q2") (pin "2") (pinfunction "S_2") (pintype "passive"))
      (node (ref "Q2") (pin "3") (pinfunction "S_3") (pintype "passive"))
      (node (ref "Q8") (pin "2") (pinfunction "D_2") (pintype "passive"))
      (node (ref "R5") (pin "1") (pinfunction "1_1") (pintype "passive"))
      (node (ref "R69") (pin "1") (pinfunction "1_1") (pintype "passive"))
      (node (ref "SH1") (pin "1") (pinfunction "GND_A_1") (pintype "bidirectional"))
      (node (ref "SH2") (pin "2") (pinfunction "GND_B_2") (pintype "bidirectional"))
      (node (ref "X2") (pin "3") (pinfunction "1_3") (pintype "passive"))
      (node (ref "X2") (pin "4") (pinfunction "1_4") (pintype "passive"))
      (node (ref "X2") (pin "5") (pinfunction "1_5") (pintype "passive"))
      (node (ref "X2") (pin "6") (pinfunction "1_6") (pintype "passive"))
      (node (ref "X3") (pin "10") (pinfunction "1_10") (pintype "passive"))
      (node (ref "X3") (pin "5") (pinfunction "1_5") (pintype "passive"))
      (node (ref "X3") (pin "7") (pinfunction "1_7") (pintype "passive"))
      (node (ref "X3") (pin "8") (pinfunction "1_8") (pintype "passive"))
      (node (ref "X3") (pin "9") (pinfunction "1_9") (pintype "passive"))
      (node (ref "ZD1") (pin "A") (pinfunction "A_A") (pintype "passive"))
    )
    (net (code "207") (name "PRE_OE") (class "Default")
      (node (ref "D1") (pin "A") (pinfunction "A_A") (pintype "passive"))
      (node (ref "IC23") (pin "2") (pinfunction "D_2") (pintype "input"))
      (node (ref "OE") (pin "2") (pinfunction "2_2") (pintype "passive"))
    )
    (net (code "208") (name "PWRGOOD") (class "Default")
      (node (ref "D23") (pin "C") (pinfunction "C_C") (pintype "passive"))
      (node (ref "IC2") (pin "6") (pinfunction "PWRGD_6") (pintype "output"))
      (node (ref "IC22") (pin "40") (pinfunction "PB4_40") (pintype "bidirectional"))
      (node (ref "Q4") (pin "1") (pinfunction "G_1") (pintype "passive"))
      (node (ref "R18") (pin "2") (pinfunction "2_2") (pintype "passive"))
    )
    (net (code "209") (name "RSENSE") (class "Default")
      (node (ref "IC22") (pin "6") (pinfunction "PF1-OSC_OUT_6") (pintype "bidirectional"))
      (node (ref "Q20") (pin "1") (pinfunction "G_1") (pintype "passive"))
      (node (ref "R97") (pin "2") (pinfunction "2_2") (pintype "passive"))
    )
    (net (code "210") (name "RSENSE_ERR") (class "Default")
      (node (ref "IC22") (pin "12") (pinfunction "PA2_12") (pintype "bidirectional"))
      (node (ref "Q19") (pin "C") (pinfunction "C_C") (pintype "passive"))
      (node (ref "R85") (pin "1") (pinfunction "1_1") (pintype "passive"))
    )
    (net (code "211") (name "SCLK") (class "Default")
      (node (ref "IC22") (pin "28") (pinfunction "PD8_28") (pintype "bidirectional"))
      (node (ref "RN1") (pin "7") (pinfunction "2_7") (pintype "passive"))
    )
    (net (code "212") (name "SENSE+") (class "Default")
      (node (ref "C46") (pin "1") (pinfunction "1_1") (pintype "passive"))
      (node (ref "K1") (pin "4") (pinfunction "COM_4") (pintype "passive"))
      (node (ref "R35") (pin "2") (pinfunction "2_2") (pintype "passive"))
      (node (ref "R47") (pin "2") (pinfunction "2_2") (pintype "passive"))
      (node (ref "R80") (pin "1") (pinfunction "1_1") (pintype "passive"))
    )
    (net (code "213") (name "SENSE-") (class "Default")
      (node (ref "C52") (pin "1") (pinfunction "1_1") (pintype "passive"))
      (node (ref "K1") (pin "9") (pinfunction "COM_9") (pintype "passive"))
      (node (ref "R56") (pin "2") (pinfunction "2_2") (pintype "passive"))
      (node (ref "R60") (pin "1") (pinfunction "1_1") (pintype "passive"))
      (node (ref "R86") (pin "2") (pinfunction "2_2") (pintype "passive"))
    )
    (net (code "214") (name "SENSE_PROT") (class "Default")
      (node (ref "Q11") (pin "C") (pinfunction "C_C") (pintype "passive"))
      (node (ref "Q12") (pin "C") (pinfunction "C_C") (pintype "passive"))
      (node (ref "Q16") (pin "C") (pinfunction "C_C") (pintype "passive"))
      (node (ref "R45") (pin "2") (pinfunction "2_2") (pintype "passive"))
      (node (ref "R51") (pin "2") (pinfunction "2_2") (pintype "passive"))
    )
    (net (code "215") (name "SW") (class "Default")
      (node (ref "C11") (pin "1") (pinfunction "1_1") (pintype "passive"))
      (node (ref "C8") (pin "2") (pinfunction "2_2") (pintype "passive"))
      (node (ref "IC1") (pin "19") (pinfunction "SW_19") (pintype "power_in"))
      (node (ref "L2") (pin "1") (pinfunction "1_1") (pintype "passive"))
      (node (ref "Q1") (pin "1") (pinfunction "S_1") (pintype "passive"))
      (node (ref "Q1") (pin "2") (pinfunction "S_2") (pintype "passive"))
      (node (ref "Q1") (pin "3") (pinfunction "S_3") (pintype "passive"))
      (node (ref "Q2") (pin "5") (pinfunction "D_5") (pintype "passive"))
      (node (ref "Q2") (pin "6") (pinfunction "D_6") (pintype "passive"))
      (node (ref "Q2") (pin "7") (pinfunction "D_7") (pintype "passive"))
      (node (ref "Q2") (pin "8") (pinfunction "D_8") (pintype "passive"))
      (node (ref "R4") (pin "2") (pinfunction "2_2") (pintype "passive"))
    )
    (net (code "216") (name "SWCLK") (class "Default")
      (node (ref "IC22") (pin "37") (pinfunction "PA14_37") (pintype "bidirectional"))
      (node (ref "RN2") (pin "2") (pinfunction "1_2") (pintype "passive"))
    )
    (net (code "217") (name "SWDIO") (class "Default")
      (node (ref "IC22") (pin "34") (pinfunction "PA13_34") (pintype "bidirectional"))
      (node (ref "RN2") (pin "4") (pinfunction "1_4") (pintype "passive"))
    )
    (net (code "218") (name "SWO") (class "Default")
      (node (ref "IC22") (pin "39") (pinfunction "PB3_39") (pintype "bidirectional"))
      (node (ref "RN2") (pin "1") (pinfunction "1_1") (pintype "passive"))
    )
    (net (code "219") (name "TCK") (class "Default")
      (node (ref "RN2") (pin "7") (pinfunction "2_7") (pintype "passive"))
      (node (ref "X7") (pin "2") (pinfunction "1_2") (pintype "passive"))
    )
    (net (code "220") (name "TEMP_SENSOR") (class "Default")
      (node (ref "C100") (pin "2") (pinfunction "2_2") (pintype "passive"))
      (node (ref "IC22") (pin "10") (pinfunction "PA0_10") (pintype "bidirectional"))
      (node (ref "NTC1") (pin "2") (pinfunction "P$2_2") (pintype "bidirectional"))
      (node (ref "R127") (pin "1") (pinfunction "1_1") (pintype "passive"))
    )
    (net (code "221") (name "TMS") (class "Default")
      (node (ref "RN2") (pin "5") (pinfunction "2_5") (pintype "passive"))
      (node (ref "X7") (pin "4") (pinfunction "1_4") (pintype "passive"))
    )
    (net (code "222") (name "UART_RX") (class "Default")
      (node (ref "IC22") (pin "31") (pinfunction "PA10_31") (pintype "bidirectional"))
      (node (ref "IC7") (pin "12") (pinfunction "B3_12") (pintype "output"))
    )
    (net (code "223") (name "UART_TX") (class "Default")
      (node (ref "IC22") (pin "30") (pinfunction "PA9_30") (pintype "bidirectional"))
      (node (ref "IC7") (pin "11") (pinfunction "B4_11") (pintype "input"))
      (node (ref "R23") (pin "1") (pinfunction "1_1") (pintype "passive"))
    )
    (net (code "224") (name "U_MON") (class "Default")
      (node (ref "IC9") (pin "7") (pinfunction "OUT_7") (pintype "output"))
      (node (ref "R104") (pin "1") (pinfunction "1_1") (pintype "passive"))
      (node (ref "R131") (pin "2") (pinfunction "2_2") (pintype "passive"))
      (node (ref "R54") (pin "1") (pinfunction "1_1") (pintype "passive"))
      (node (ref "R61") (pin "1") (pinfunction "1_1") (pintype "passive"))
    )
    (net (code "225") (name "U_MON_AIN") (class "Default")
      (node (ref "C104") (pin "2") (pinfunction "2_2") (pintype "passive"))
      (node (ref "IC22") (pin "21") (pinfunction "PE8_21") (pintype "bidirectional"))
      (node (ref "R131") (pin "1") (pinfunction "1_1") (pintype "passive"))
    )
    (net (code "226") (name "U_SERVO") (class "Default")
      (node (ref "C53") (pin "2") (pinfunction "2_2") (pintype "passive"))
      (node (ref "D12") (pin "C") (pinfunction "C_C") (pintype "passive"))
      (node (ref "D13") (pin "A") (pinfunction "A_A") (pintype "passive"))
      (node (ref "IC9") (pin "1") (pinfunction "OUT_1") (pintype "output"))
      (node (ref "R102") (pin "1") (pinfunction "1_1") (pintype "passive"))
    )
    (net (code "227") (name "U_SET") (class "Default")
      (node (ref "IC14") (pin "3") (pinfunction "NC_3") (pintype "bidirectional"))
      (node (ref "IC15") (pin "3") (pinfunction "+IN_3") (pintype "input"))
      (node (ref "R129") (pin "2") (pinfunction "2_2") (pintype "passive"))
      (node (ref "USET") (pin "2") (pinfunction "2_2") (pintype "passive"))
    )
    (net (code "228") (name "U_SET_AIN") (class "Default")
      (node (ref "C102") (pin "2") (pinfunction "2_2") (pintype "passive"))
      (node (ref "IC22") (pin "19") (pinfunction "PB1_19") (pintype "bidirectional"))
      (node (ref "R129") (pin "1") (pinfunction "1_1") (pintype "passive"))
    )
    (net (code "229") (name "U_SET_OUT") (class "Default")
      (node (ref "IC14") (pin "4") (pinfunction "COM_4") (pintype "bidirectional"))
      (node (ref "R53") (pin "1") (pinfunction "1_1") (pintype "passive"))
    )
    (net (code "230") (name "V+") (class "Default")
      (node (ref "C54") (pin "2") (pinfunction "2_2") (pintype "passive"))
      (node (ref "C55") (pin "1") (pinfunction "1_1") (pintype "passive"))
      (node (ref "C56") (pin "2") (pinfunction "2_2") (pintype "passive"))
      (node (ref "C57") (pin "2") (pinfunction "2_2") (pintype "passive"))
      (node (ref "C59") (pin "2") (pinfunction "2_2") (pintype "passive"))
      (node (ref "C76") (pin "1") (pinfunction "1_1") (pintype "passive"))
      (node (ref "C77") (pin "1") (pinfunction "1_1") (pintype "passive"))
      (node (ref "C82") (pin "2") (pinfunction "2_2") (pintype "passive"))
      (node (ref "C83") (pin "2") (pinfunction "2_2") (pintype "passive"))
      (node (ref "C90") (pin "1") (pinfunction "1_1") (pintype "passive"))
      (node (ref "FB1") (pin "P$2") (pinfunction "2_P$2") (pintype "passive"))
      (node (ref "IC10") (pin "8") (pinfunction "V+_8") (pintype "power_in"))
      (node (ref "IC11") (pin "7") (pinfunction "V+_7") (pintype "power_in"))
      (node (ref "IC15") (pin "8") (pinfunction "V+_8") (pintype "power_in"))
      (node (ref "IC16") (pin "5") (pinfunction "V+_5") (pintype "power_in"))
      (node (ref "IC18") (pin "8") (pinfunction "V+_8") (pintype "power_in"))
      (node (ref "IC19") (pin "1") (pinfunction "+VCC_1") (pintype "passive"))
      (node (ref "IC19") (pin "5") (pinfunction "~{LE}_5") (pintype "input"))
      (node (ref "IC21") (pin "2") (pinfunction "VIN_2") (pintype "passive"))
      (node (ref "IC9") (pin "8") (pinfunction "V+_8") (pintype "power_in"))
    )
    (net (code "231") (name "V-") (class "Default")
      (node (ref "C60") (pin "2") (pinfunction "2_2") (pintype "passive"))
      (node (ref "C62") (pin "2") (pinfunction "2_2") (pintype "passive"))
      (node (ref "C63") (pin "1") (pinfunction "1_1") (pintype "passive"))
      (node (ref "C64") (pin "2") (pinfunction "2_2") (pintype "passive"))
      (node (ref "C65") (pin "2") (pinfunction "2_2") (pintype "passive"))
      (node (ref "C79") (pin "1") (pinfunction "1_1") (pintype "passive"))
      (node (ref "C85") (pin "2") (pinfunction "2_2") (pintype "passive"))
      (node (ref "FB3") (pin "P$2") (pinfunction "2_P$2") (pintype "passive"))
      (node (ref "IC10") (pin "4") (pinfunction "V-_4") (pintype "power_in"))
      (node (ref "IC11") (pin "4") (pinfunction "V-_4") (pintype "power_in"))
      (node (ref "IC16") (pin "2") (pinfunction "V-_2") (pintype "power_in"))
      (node (ref "IC18") (pin "4") (pinfunction "V-_4") (pintype "power_in"))
      (node (ref "IC9") (pin "4") (pinfunction "V-_4") (pintype "power_in"))
    )
    (net (code "232") (name "VCC") (class "Default")
      (node (ref "C10") (pin "2") (pinfunction "2_2") (pintype "passive"))
      (node (ref "D2") (pin "C") (pinfunction "C_C") (pintype "passive"))
      (node (ref "IC1") (pin "14") (pinfunction "VCC_14") (pintype "power_in"))
      (node (ref "JP1") (pin "1") (pinfunction "1_1") (pintype "passive"))
    )
    (net (code "233") (name "VDDA") (class "Default")
      (node (ref "C97") (pin "2") (pinfunction "2_2") (pintype "passive"))
      (node (ref "C98") (pin "2") (pinfunction "2_2") (pintype "passive"))
      (node (ref "FB4") (pin "P$2") (pinfunction "2_P$2") (pintype "passive"))
      (node (ref "IC22") (pin "24") (pinfunction "VDDSD_24") (pintype "passive"))
    )
    (net (code "234") (name "unconnected-(IC1-PGOOD-Pad10)") (class "Default")
      (node (ref "IC1") (pin "10") (pinfunction "PGOOD_10") (pintype "open_collector"))
    )
    (net (code "235") (name "unconnected-(IC1-SYNCOUT-Pad7)") (class "Default")
      (node (ref "IC1") (pin "7") (pinfunction "SYNCOUT_7") (pintype "output"))
    )
    (net (code "236") (name "unconnected-(IC12-NC-Pad3)") (class "Default")
      (node (ref "IC12") (pin "3") (pinfunction "NC_3") (pintype "bidirectional"))
    )
    (net (code "237") (name "unconnected-(IC21-TEMP-Pad3)") (class "Default")
      (node (ref "IC21") (pin "3") (pinfunction "TEMP_3") (pintype "input"))
    )
    (net (code "238") (name "unconnected-(IC22-VBAT-Pad1)") (class "Default")
      (node (ref "IC22") (pin "1") (pinfunction "VBAT_1") (pintype "passive"))
    )
    (net (code "239") (name "unconnected-(IC23A-~{Q}-Pad3)") (class "Default")
      (node (ref "IC23") (pin "3") (pinfunction "~{Q}_3") (pintype "output"))
    )
    (net (code "240") (name "unconnected-(KK3-Pad1)") (class "Default")
      (node (ref "KK3") (pin "1") (pinfunction "1_1") (pintype "passive"))
    )
    (net (code "241") (name "unconnected-(KK3-Pad2)") (class "Default")
      (node (ref "KK3") (pin "2") (pinfunction "2_2") (pintype "passive"))
    )
    (net (code "242") (name "~{DP_DRIVE}") (class "Default")
      (node (ref "Q9") (pin "1") (pinfunction "B_1") (pintype "passive"))
      (node (ref "R125") (pin "1") (pinfunction "1_1") (pintype "passive"))
      (node (ref "R41") (pin "1") (pinfunction "1_1") (pintype "passive"))
    )
    (net (code "243") (name "~{OVP_FAULT}") (class "Default")
      (node (ref "C86") (pin "2") (pinfunction "2_2") (pintype "passive"))
      (node (ref "D24") (pin "C") (pinfunction "C_C") (pintype "passive"))
      (node (ref "IC22") (pin "43") (pinfunction "PB7_43") (pintype "bidirectional"))
      (node (ref "Q25") (pin "3") (pinfunction "D_3") (pintype "passive"))
      (node (ref "R117") (pin "2") (pinfunction "2_2") (pintype "passive"))
    )
    (net (code "244") (name "~{RESET}") (class "Default")
      (node (ref "IC3") (pin "15") (pinfunction "B1_15") (pintype "output"))
      (node (ref "JP5") (pin "1") (pinfunction "1_1") (pintype "passive"))
    )
    (net (code "245") (name "~{SET_DP}") (class "Default")
      (node (ref "IC22") (pin "18") (pinfunction "PB0_18") (pintype "bidirectional"))
      (node (ref "Q28") (pin "1") (pinfunction "G_1") (pintype "passive"))
      (node (ref "R123") (pin "2") (pinfunction "2_2") (pintype "passive"))
    )
  )
)
